# C64.net
KiCad netlist of a schematic drawn in EAGLE
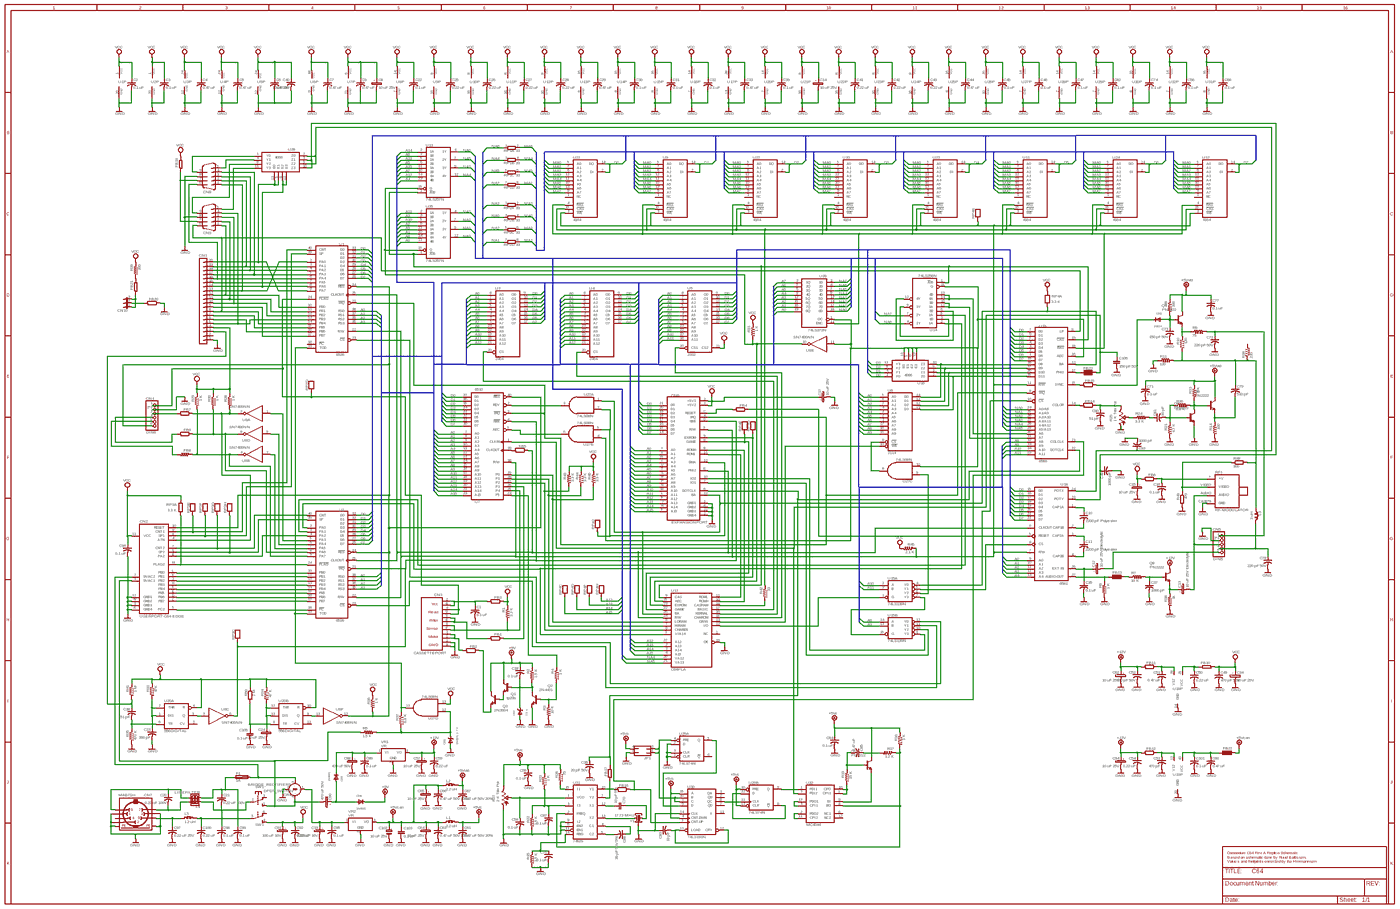
[diagram p0: schematic, sheet 1, overview]
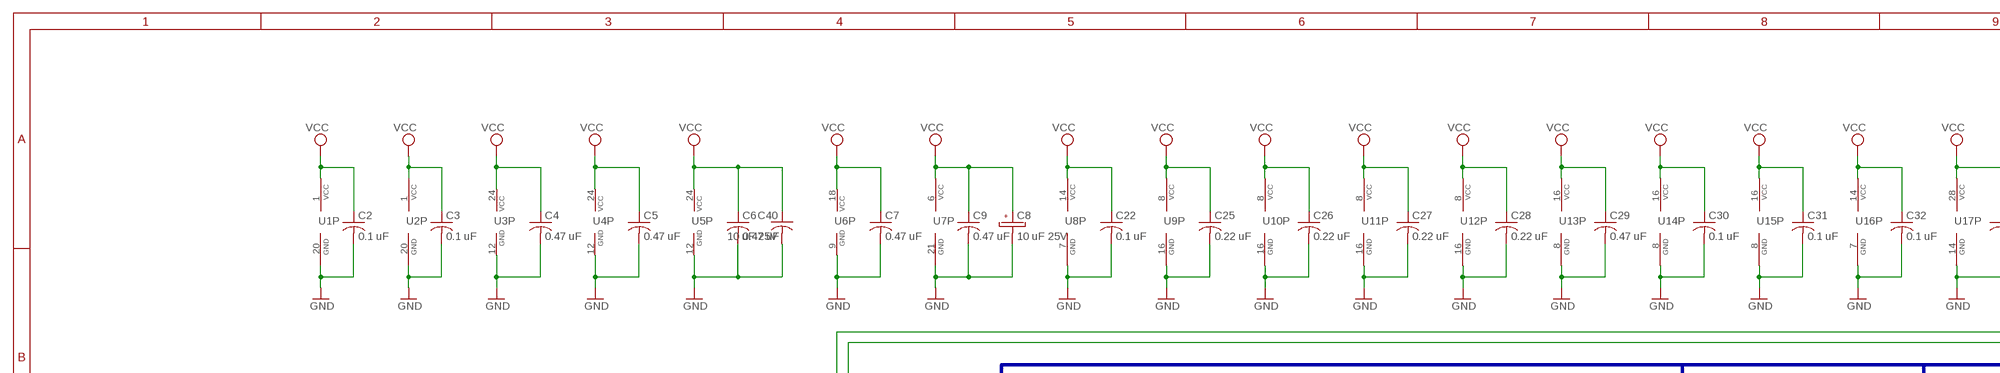
[diagram p1: schematic, sheet 1, part 1 of 4]
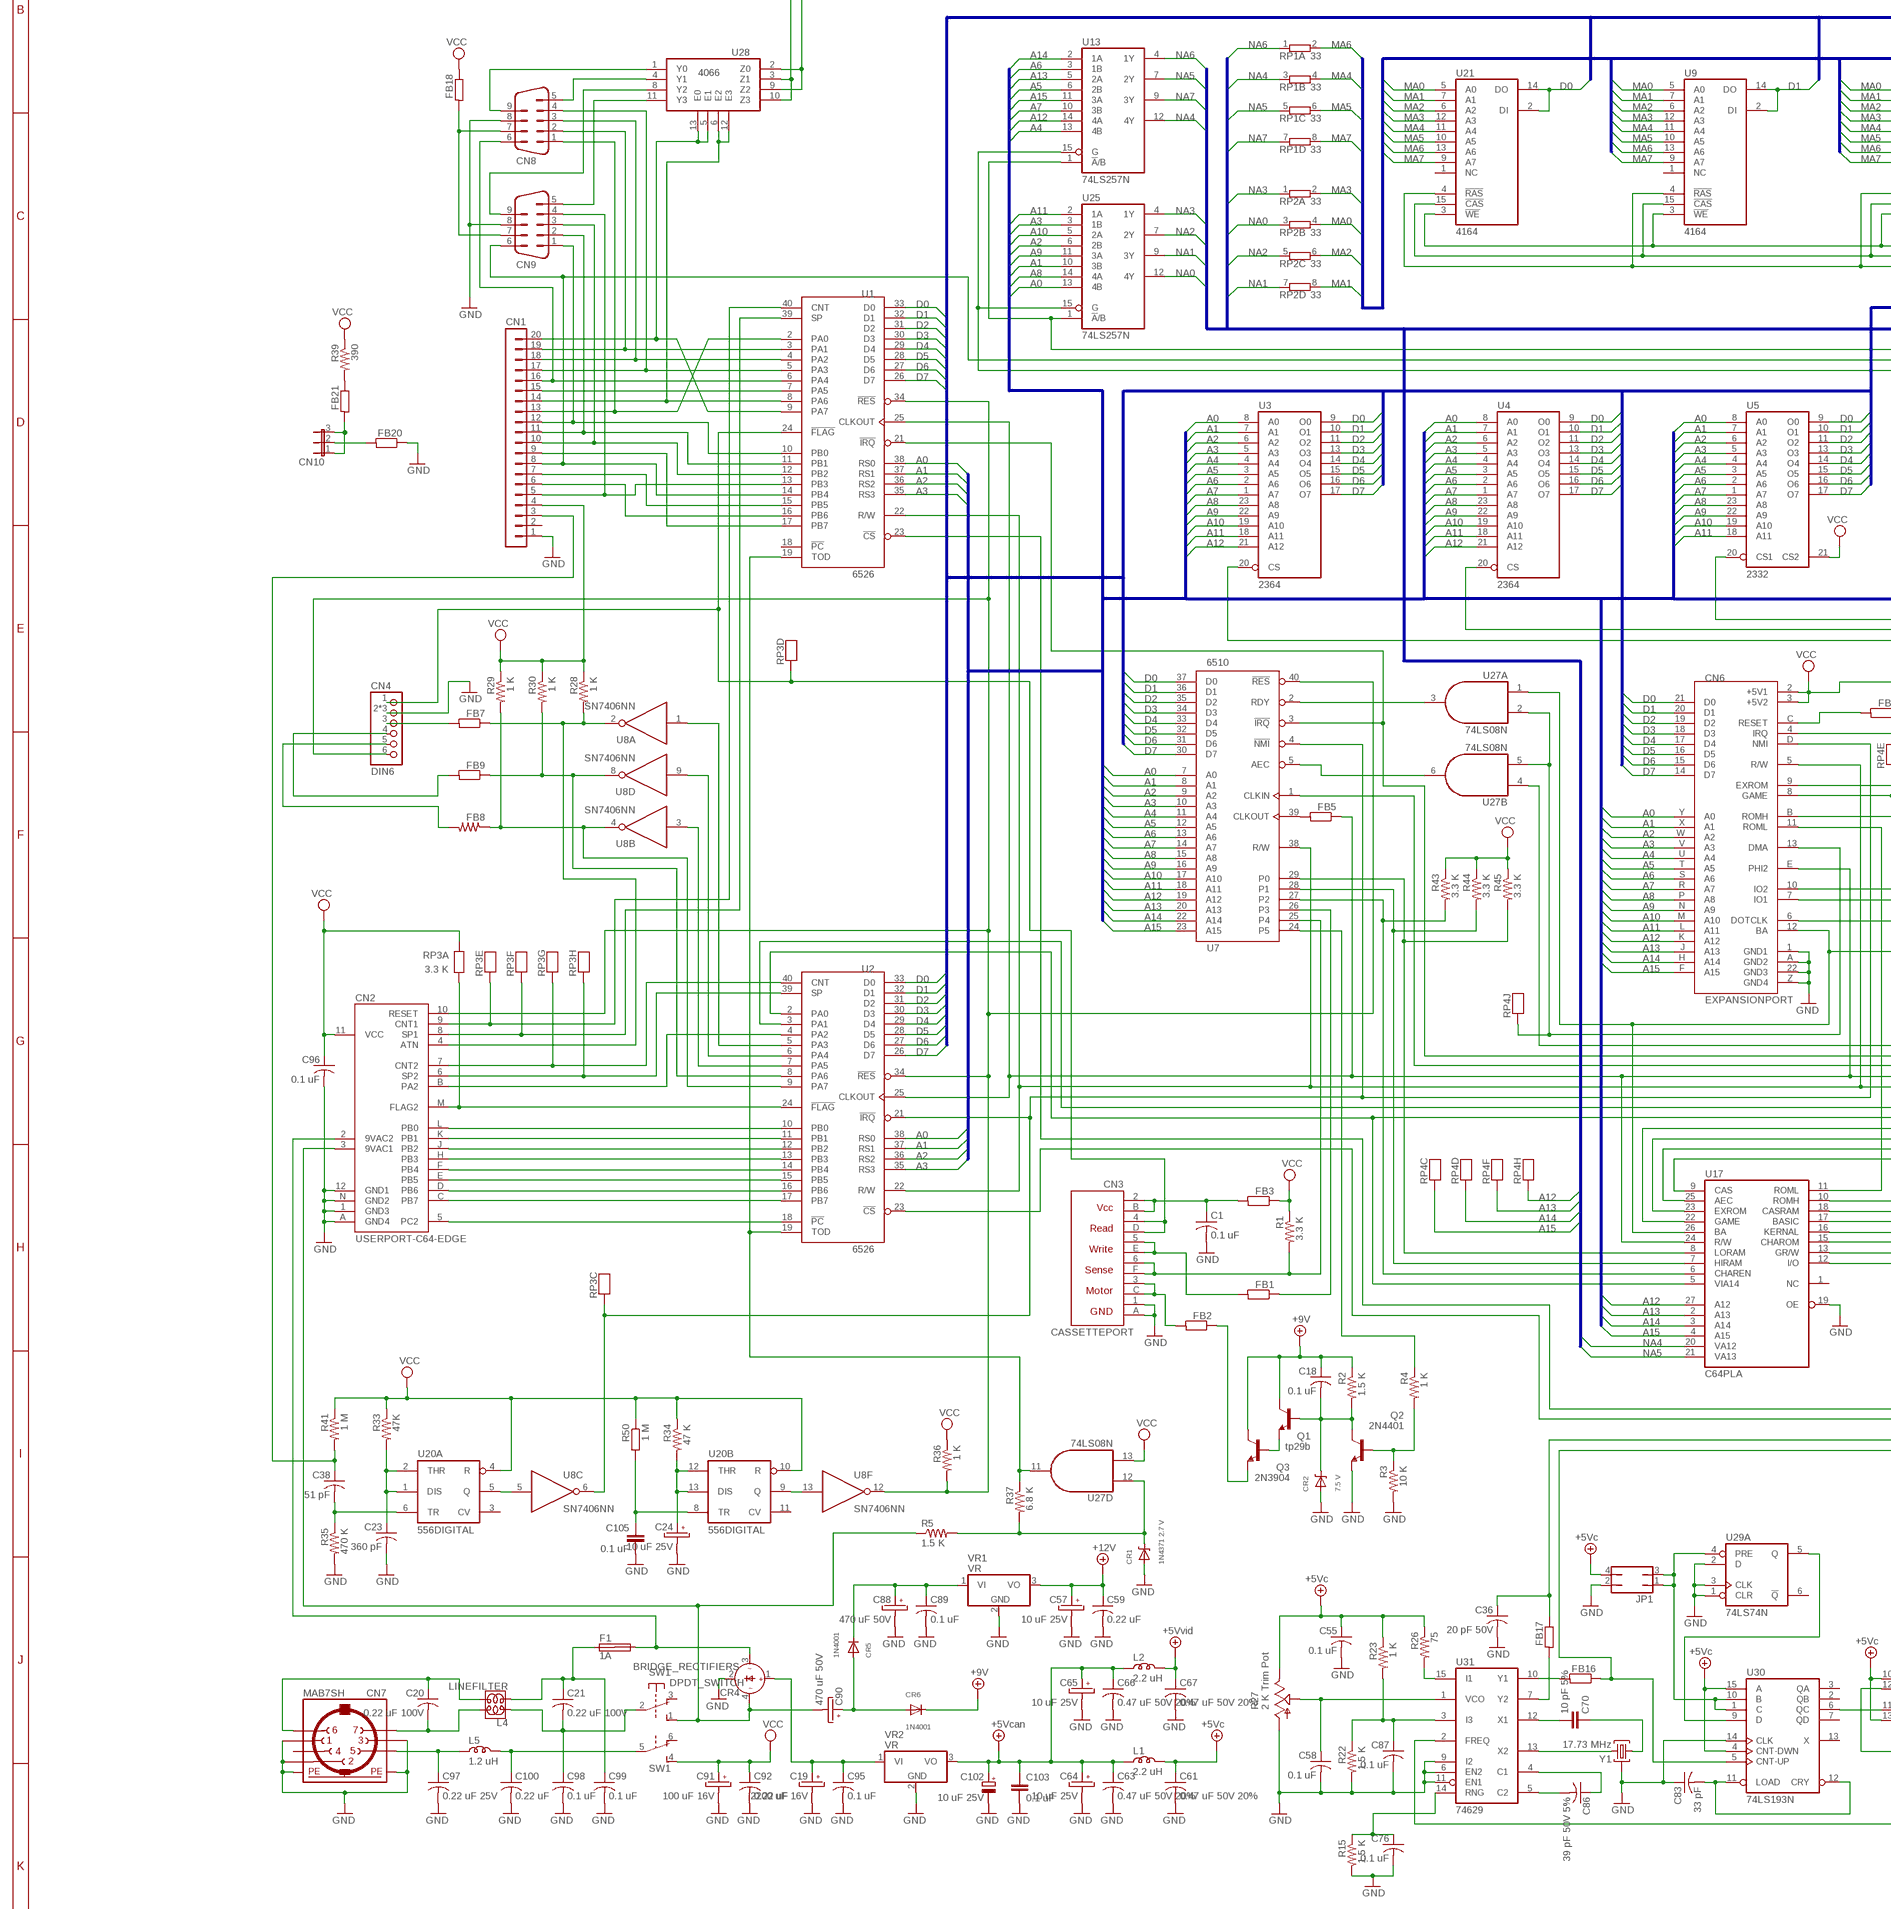
[diagram p2: schematic, sheet 1, part 2 of 4]
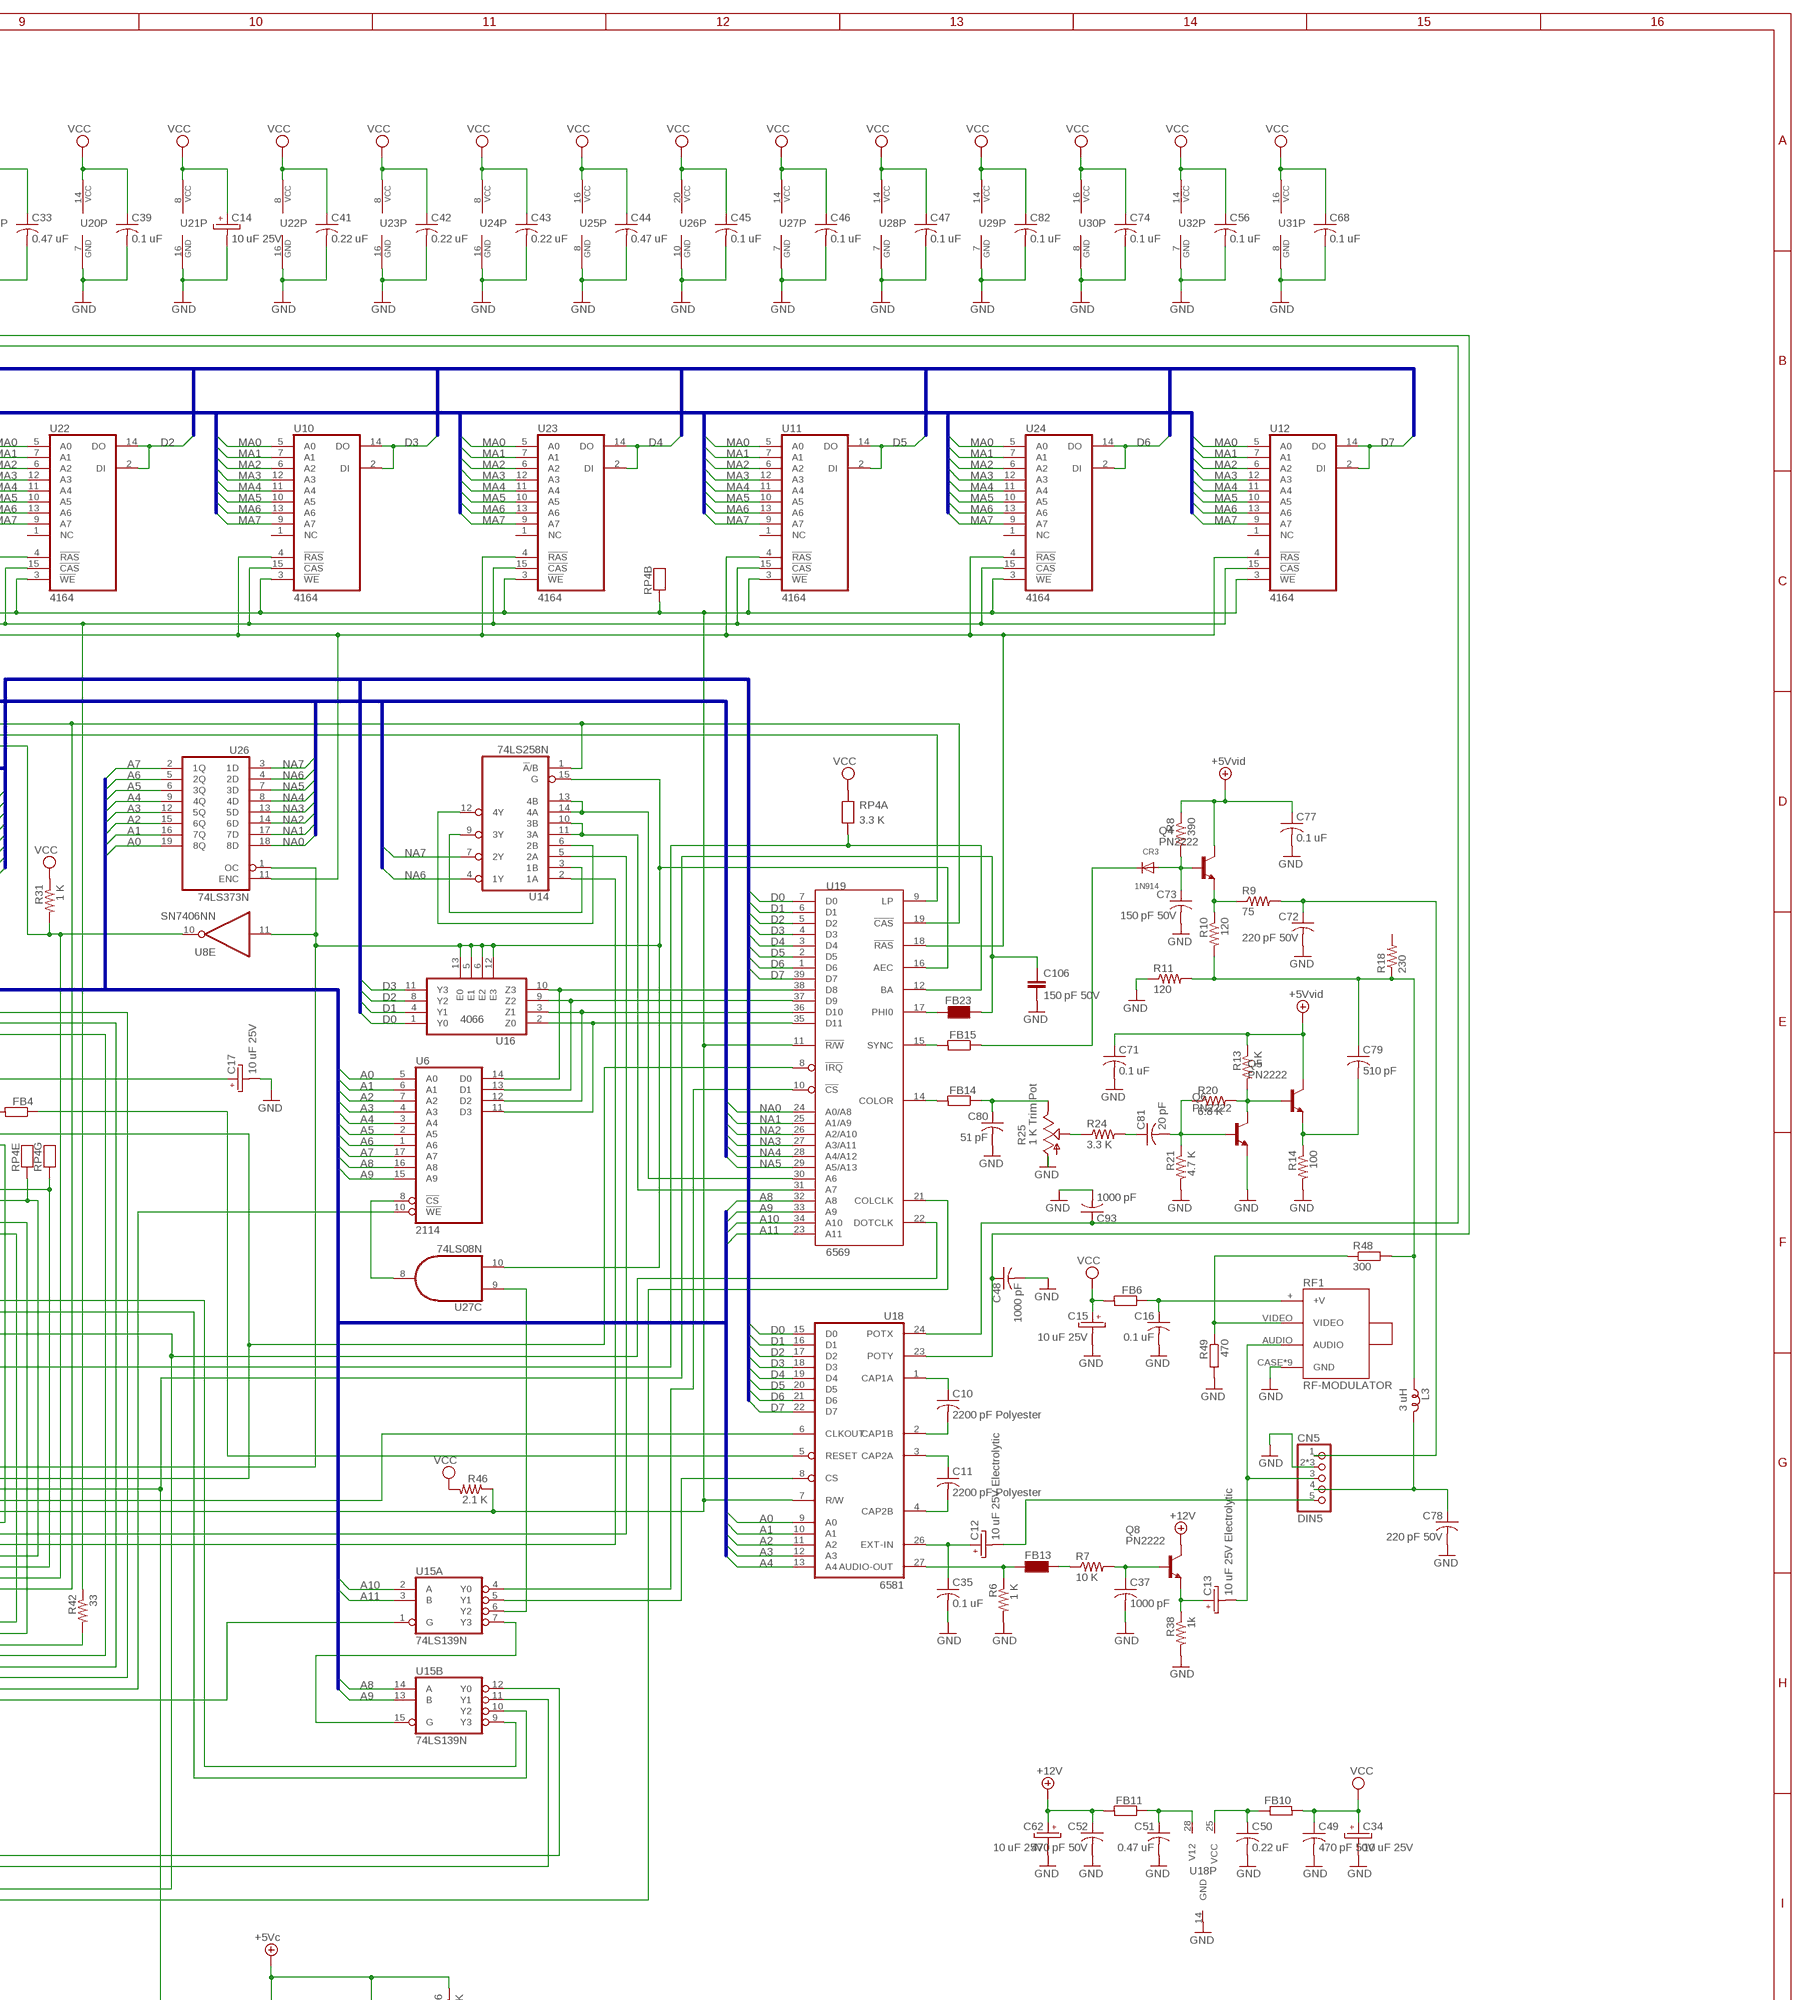
[diagram p3: schematic, sheet 1, part 3 of 4]
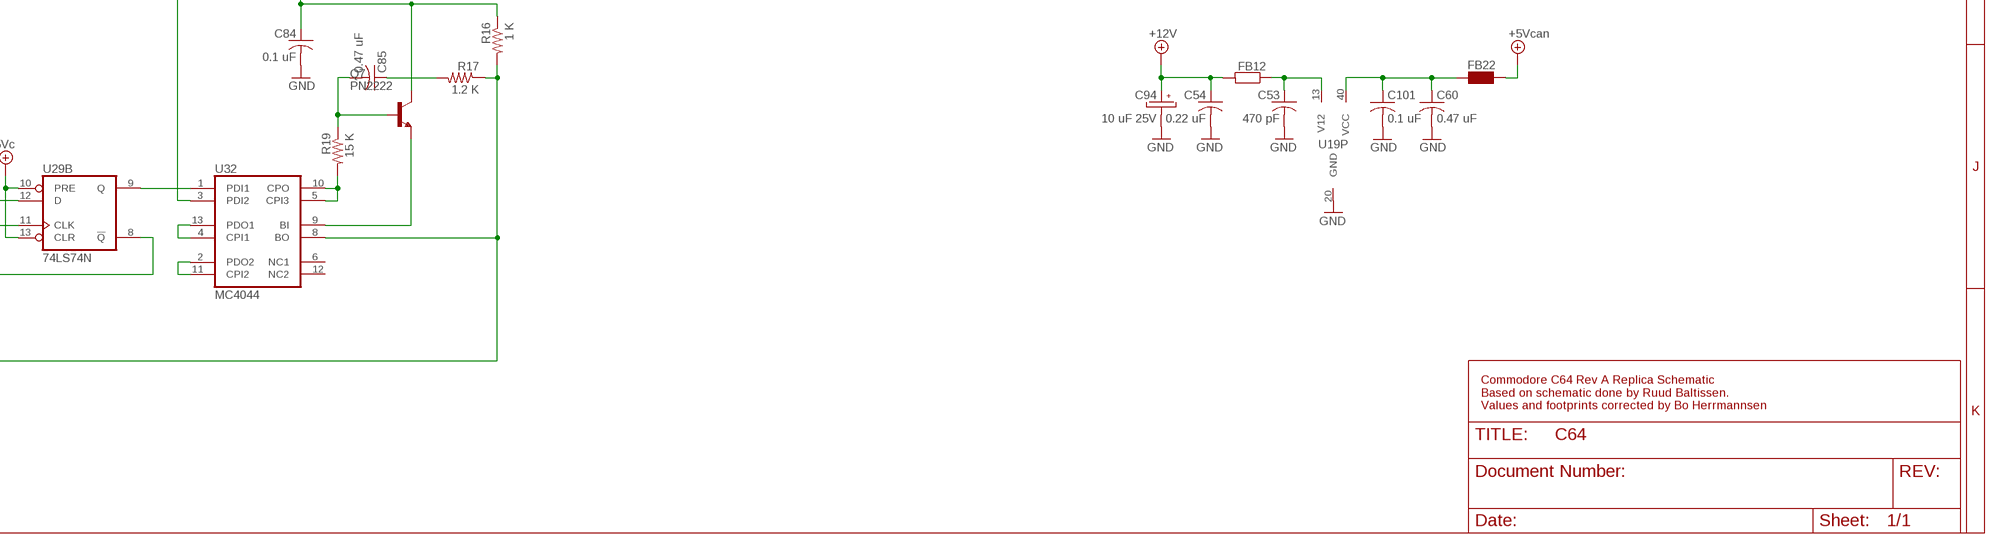
[diagram p4: schematic, sheet 1, part 4 of 4]

(export (version "E")
  (design (tool "Eeschema 10.0.6"))
  (components
    (comp (ref "C1")
      (value "0.1 uF")
      (footprint "eagle-import:0307_12")
      (libsource (lib "eagle-import") (part "C_0307/12C_0309/12"))
    )
    (comp (ref "C2")
      (value "0.1 uF")
      (footprint "eagle-import:0307_12")
      (libsource (lib "eagle-import") (part "C_0307/12C_0309/12"))
    )
    (comp (ref "C3")
      (value "0.1 uF")
      (footprint "eagle-import:0307_12")
      (libsource (lib "eagle-import") (part "C_0307/12C_0309/12"))
    )
    (comp (ref "C4")
      (value "0.47 uF")
      (footprint "eagle-import:0307_12")
      (libsource (lib "eagle-import") (part "C_0307/12C_0309/12"))
    )
    (comp (ref "C5")
      (value "0.47 uF")
      (footprint "eagle-import:0307_12")
      (libsource (lib "eagle-import") (part "C_0307/12C_0309/12"))
    )
    (comp (ref "C6")
      (value "0.47 uF")
      (footprint "eagle-import:0307_12")
      (libsource (lib "eagle-import") (part "C_0307/12C_0309/12"))
    )
    (comp (ref "C7")
      (value "0.47 uF")
      (footprint "eagle-import:0307_12")
      (libsource (lib "eagle-import") (part "C_0307/12C_0309/12"))
    )
    (comp (ref "C8")
      (value "10 uF 25V")
      (footprint "eagle-import:E2,5-6E")
      (libsource (lib "eagle-import") (part "C_E_2,5-6"))
    )
    (comp (ref "C9")
      (value "0.47 uF")
      (footprint "eagle-import:0307_12")
      (libsource (lib "eagle-import") (part "C_0307/12C_0309/12"))
    )
    (comp (ref "C10")
      (value "2200 pF Polyester")
      (footprint "eagle-import:0307_12")
      (libsource (lib "eagle-import") (part "C_0307/12C_0309/12"))
    )
    (comp (ref "C11")
      (value "2200 pF Polyester")
      (footprint "eagle-import:0307_12")
      (libsource (lib "eagle-import") (part "C_0307/12C_0309/12"))
    )
    (comp (ref "C12")
      (value "10 uF 25V Electrolytic")
      (footprint "eagle-import:E2,5-6E")
      (libsource (lib "eagle-import") (part "C_E_2,5-6"))
    )
    (comp (ref "C13")
      (value "10 uF 25V Electrolytic")
      (footprint "eagle-import:E2,5-6E")
      (libsource (lib "eagle-import") (part "C_E_2,5-6"))
    )
    (comp (ref "C14")
      (value "10 uF 25V")
      (footprint "eagle-import:CAPACITOR_ELECTROLYTIC_2.5_6")
      (libsource (lib "eagle-import") (part "CAPACITOR_ELECTROLYTIC_2.5_6"))
    )
    (comp (ref "C15")
      (value "10 uF 25V")
      (footprint "eagle-import:E2,5-6E")
      (libsource (lib "eagle-import") (part "C_E_2,5-6"))
    )
    (comp (ref "C16")
      (value "0.1 uF")
      (footprint "eagle-import:0307_12")
      (libsource (lib "eagle-import") (part "C_0307/12C_0309/12"))
    )
    (comp (ref "C17")
      (value "10 uF 25V")
      (footprint "eagle-import:E2,5-6E")
      (libsource (lib "eagle-import") (part "C_E_2,5-6"))
    )
    (comp (ref "C18")
      (value "0.1 uF")
      (footprint "eagle-import:0307_12")
      (libsource (lib "eagle-import") (part "C_0307/12C_0309/12"))
    )
    (comp (ref "C19")
      (value "2200 uF 16V")
      (footprint "eagle-import:E37-31.5-17.5-E")
      (libsource (lib "eagle-import") (part "E37-31.5-17.5-E"))
    )
    (comp (ref "C20")
      (value "0.22 uF 100V")
      (footprint "eagle-import:0203")
      (libsource (lib "eagle-import") (part "C_0203"))
    )
    (comp (ref "C21")
      (value "0.22 uF 100V")
      (footprint "eagle-import:0203")
      (libsource (lib "eagle-import") (part "C_0203"))
    )
    (comp (ref "C22")
      (value "0.1 uF")
      (footprint "eagle-import:12_3_7")
      (libsource (lib "eagle-import") (part "CAPACITOR_12_3_7C_0309/12"))
    )
    (comp (ref "C23")
      (value "360 pF")
      (footprint "eagle-import:12_3_7")
      (libsource (lib "eagle-import") (part "CAPACITOR_12_3_7C_0309/12"))
    )
    (comp (ref "C24")
      (value "10 uF 25V")
      (footprint "eagle-import:CAPACITOR_ELECTROLYTIC_2.5_6")
      (libsource (lib "eagle-import") (part "CAPACITOR_ELECTROLYTIC_2.5_6"))
    )
    (comp (ref "C25")
      (value "0.22 uF")
      (footprint "eagle-import:12_3_7")
      (libsource (lib "eagle-import") (part "CAPACITOR_12_3_7C_0309/12"))
    )
    (comp (ref "C26")
      (value "0.22 uF")
      (footprint "eagle-import:12_3_7")
      (libsource (lib "eagle-import") (part "CAPACITOR_12_3_7C_0309/12"))
    )
    (comp (ref "C27")
      (value "0.22 uF")
      (footprint "eagle-import:12_3_7")
      (libsource (lib "eagle-import") (part "CAPACITOR_12_3_7C_0309/12"))
    )
    (comp (ref "C28")
      (value "0.22 uF")
      (footprint "eagle-import:12_3_7")
      (libsource (lib "eagle-import") (part "CAPACITOR_12_3_7C_0309/12"))
    )
    (comp (ref "C29")
      (value "0.47 uF")
      (footprint "eagle-import:0307_12")
      (libsource (lib "eagle-import") (part "C_0307/12C_0309/12"))
    )
    (comp (ref "C30")
      (value "0.1 uF")
      (footprint "eagle-import:0307_12")
      (libsource (lib "eagle-import") (part "C_0307/12C_0309/12"))
    )
    (comp (ref "C31")
      (value "0.1 uF")
      (footprint "eagle-import:0307_12")
      (libsource (lib "eagle-import") (part "C_0307/12C_0309/12"))
    )
    (comp (ref "C32")
      (value "0.1 uF")
      (footprint "eagle-import:0307_12")
      (libsource (lib "eagle-import") (part "C_0307/12C_0309/12"))
    )
    (comp (ref "C33")
      (value "0.47 uF")
      (footprint "eagle-import:0307_12")
      (libsource (lib "eagle-import") (part "C_0307/12C_0309/12"))
    )
    (comp (ref "C34")
      (value "10 uF 25V")
      (footprint "eagle-import:E2,5-6E")
      (libsource (lib "eagle-import") (part "C_E_2,5-6"))
    )
    (comp (ref "C35")
      (value "0.1 uF")
      (footprint "eagle-import:0307_12")
      (libsource (lib "eagle-import") (part "C_0307/12C_0309/12"))
    )
    (comp (ref "C36")
      (value "20 pF 50V")
      (footprint "eagle-import:12_03_07")
      (libsource (lib "eagle-import") (part "CAPACITOR_12_03_07C_0309/12"))
    )
    (comp (ref "C37")
      (value "1000 pF")
      (footprint "eagle-import:0307_12")
      (libsource (lib "eagle-import") (part "C_0307/12C_0309/12"))
    )
    (comp (ref "C38")
      (value "51 pF")
      (footprint "eagle-import:12_3_7")
      (libsource (lib "eagle-import") (part "CAPACITOR_12_3_7C_0309/12"))
    )
    (comp (ref "C39")
      (value "0.1 uF")
      (footprint "eagle-import:12_3_7")
      (libsource (lib "eagle-import") (part "CAPACITOR_12_3_7C_0309/12"))
    )
    (comp (ref "C40")
      (value "10 uF 25V")
      (footprint "eagle-import:12_3_7")
      (libsource (lib "eagle-import") (part "CAPACITOR_12_3_7C_0309/12"))
    )
    (comp (ref "C41")
      (value "0.22 uF")
      (footprint "eagle-import:12_3_7")
      (libsource (lib "eagle-import") (part "CAPACITOR_12_3_7C_0309/12"))
    )
    (comp (ref "C42")
      (value "0.22 uF")
      (footprint "eagle-import:12_3_7")
      (libsource (lib "eagle-import") (part "CAPACITOR_12_3_7C_0309/12"))
    )
    (comp (ref "C43")
      (value "0.22 uF")
      (footprint "eagle-import:12_3_7")
      (libsource (lib "eagle-import") (part "CAPACITOR_12_3_7C_0309/12"))
    )
    (comp (ref "C44")
      (value "0.47 uF")
      (footprint "eagle-import:0307_12")
      (libsource (lib "eagle-import") (part "C_0307/12C_0309/12"))
    )
    (comp (ref "C45")
      (value "0.1 uF")
      (footprint "eagle-import:0307_12")
      (libsource (lib "eagle-import") (part "C_0307/12C_0309/12"))
    )
    (comp (ref "C46")
      (value "0.1 uF")
      (footprint "eagle-import:0307_12")
      (libsource (lib "eagle-import") (part "C_0307/12C_0309/12"))
    )
    (comp (ref "C47")
      (value "0.1 uF")
      (footprint "eagle-import:0307_12")
      (libsource (lib "eagle-import") (part "C_0307/12C_0309/12"))
    )
    (comp (ref "C48")
      (value "1000 pF")
      (footprint "eagle-import:0307_12")
      (libsource (lib "eagle-import") (part "C_0307/12C_0309/12"))
    )
    (comp (ref "C49")
      (value "470 pF 50V")
      (footprint "eagle-import:0307_12")
      (libsource (lib "eagle-import") (part "C_0307/12C_0309/12"))
    )
    (comp (ref "C50")
      (value "0.22 uF")
      (footprint "eagle-import:0307_12")
      (libsource (lib "eagle-import") (part "C_0307/12C_0309/12"))
    )
    (comp (ref "C51")
      (value "0.47 uF")
      (footprint "eagle-import:0307_12")
      (libsource (lib "eagle-import") (part "C_0307/12C_0309/12"))
    )
    (comp (ref "C52")
      (value "470 pF 50V")
      (footprint "eagle-import:0307_12")
      (libsource (lib "eagle-import") (part "C_0307/12C_0309/12"))
    )
    (comp (ref "C53")
      (value "470 pF")
      (footprint "eagle-import:0307_12")
      (libsource (lib "eagle-import") (part "C_0307/12C_0309/12"))
    )
    (comp (ref "C54")
      (value "0.22 uF")
      (footprint "eagle-import:0307_12")
      (libsource (lib "eagle-import") (part "C_0307/12C_0309/12"))
    )
    (comp (ref "C55")
      (value "0.1 uF")
      (footprint "eagle-import:12_03_07")
      (libsource (lib "eagle-import") (part "CAPACITOR_12_03_07C_0309/12"))
    )
    (comp (ref "C56")
      (value "0.1 uF")
      (footprint "eagle-import:12_03_07")
      (libsource (lib "eagle-import") (part "CAPACITOR_12_03_07C_0309/12"))
    )
    (comp (ref "C57")
      (value "10 uF 25V")
      (footprint "eagle-import:E2,5-6E")
      (libsource (lib "eagle-import") (part "C_E_2,5-6"))
    )
    (comp (ref "C58")
      (value "0.1 uF")
      (footprint "eagle-import:12_03_07")
      (libsource (lib "eagle-import") (part "CAPACITOR_12_03_07C_0309/12"))
    )
    (comp (ref "C59")
      (value "0.22 uF")
      (footprint "eagle-import:0307_12")
      (libsource (lib "eagle-import") (part "C_0307/12C_0309/12"))
    )
    (comp (ref "C60")
      (value "0.47 uF")
      (footprint "eagle-import:12_03_07")
      (libsource (lib "eagle-import") (part "CAPACITOR_12_03_07C_0309/12"))
    )
    (comp (ref "C61")
      (value "0.47 uF 50V 20%")
      (footprint "eagle-import:15_4_10")
      (libsource (lib "eagle-import") (part "CAPACITOR_15_04_10"))
    )
    (comp (ref "C62")
      (value "10 uF 25V")
      (footprint "eagle-import:E2,5-6E")
      (libsource (lib "eagle-import") (part "C_E_2,5-6"))
    )
    (comp (ref "C63")
      (value "0.47 uF 50V 20%")
      (footprint "eagle-import:15_4_10")
      (libsource (lib "eagle-import") (part "CAPACITOR_15_04_10"))
    )
    (comp (ref "C64")
      (value "10 uF 25V")
      (footprint "eagle-import:CAPACITOR_ELECTROLYTIC_2.5_6")
      (libsource (lib "eagle-import") (part "CAPACITOR_ELECTROLYTIC_2.5_6"))
    )
    (comp (ref "C65")
      (value "10 uF 25V")
      (footprint "eagle-import:CAPACITOR_ELECTROLYTIC_2.5_6")
      (libsource (lib "eagle-import") (part "CAPACITOR_ELECTROLYTIC_2.5_6"))
    )
    (comp (ref "C66")
      (value "0.47 uF 50V 20%")
      (footprint "eagle-import:15_4_10")
      (libsource (lib "eagle-import") (part "CAPACITOR_15_04_10"))
    )
    (comp (ref "C67")
      (value "0.47 uF 50V 20%")
      (footprint "eagle-import:15_4_10")
      (libsource (lib "eagle-import") (part "CAPACITOR_15_04_10"))
    )
    (comp (ref "C68")
      (value "0.1 uF")
      (footprint "eagle-import:12_03_07")
      (libsource (lib "eagle-import") (part "CAPACITOR_12_03_07C_0309/12"))
    )
    (comp (ref "C70")
      (value "10 pF 5%")
      (footprint "eagle-import:C075-032X103")
      (libsource (lib "eagle-import") (part "C-EU075-032X103"))
    )
    (comp (ref "C71")
      (value "0.1 uF")
      (footprint "eagle-import:12_03_07")
      (libsource (lib "eagle-import") (part "CAPACITOR_12_03_07C_0309/12"))
    )
    (comp (ref "C72")
      (value "220 pF 50V")
      (footprint "eagle-import:12_03_07")
      (libsource (lib "eagle-import") (part "CAPACITOR_12_03_07C_0309/12"))
    )
    (comp (ref "C73")
      (value "150 pF 50V")
      (footprint "eagle-import:12_03_07")
      (libsource (lib "eagle-import") (part "CAPACITOR_12_03_07C_0309/12"))
    )
    (comp (ref "C74")
      (value "0.1 uF")
      (footprint "eagle-import:12_03_07")
      (libsource (lib "eagle-import") (part "CAPACITOR_12_03_07C_0309/12"))
    )
    (comp (ref "C76")
      (value "0.1 uF")
      (footprint "eagle-import:12_03_07")
      (libsource (lib "eagle-import") (part "CAPACITOR_12_03_07C_0309/12"))
    )
    (comp (ref "C77")
      (value "0.1 uF")
      (footprint "eagle-import:12_03_07")
      (libsource (lib "eagle-import") (part "CAPACITOR_12_03_07C_0309/12"))
    )
    (comp (ref "C78")
      (value "220 pF 50V")
      (footprint "eagle-import:12_03_07")
      (libsource (lib "eagle-import") (part "CAPACITOR_12_03_07C_0309/12"))
    )
    (comp (ref "C79")
      (value "510 pF")
      (footprint "eagle-import:12_03_07")
      (libsource (lib "eagle-import") (part "CAPACITOR_12_03_07C_0309/12"))
    )
    (comp (ref "C80")
      (value "51 pF")
      (footprint "eagle-import:12_03_07")
      (libsource (lib "eagle-import") (part "CAPACITOR_12_03_07C_0309/12"))
    )
    (comp (ref "C81")
      (value "20 pF")
      (footprint "eagle-import:12_03_07")
      (libsource (lib "eagle-import") (part "CAPACITOR_12_03_07C_0309/12"))
    )
    (comp (ref "C82")
      (value "0.1 uF")
      (footprint "eagle-import:12_03_07")
      (libsource (lib "eagle-import") (part "CAPACITOR_12_03_07C_0309/12"))
    )
    (comp (ref "C83")
      (value "33 pF")
      (footprint "eagle-import:12_03_07")
      (libsource (lib "eagle-import") (part "CAPACITOR_12_03_07C_0309/12"))
    )
    (comp (ref "C84")
      (value "0.1 uF")
      (footprint "eagle-import:12_03_07")
      (libsource (lib "eagle-import") (part "CAPACITOR_12_03_07C_0309/12"))
    )
    (comp (ref "C85")
      (value "0.47 uF")
      (footprint "eagle-import:12_03_07")
      (libsource (lib "eagle-import") (part "CAPACITOR_12_03_07C_0309/12"))
    )
    (comp (ref "C86")
      (value "39 pF 50V 5%")
      (footprint "eagle-import:12_03_07")
      (libsource (lib "eagle-import") (part "CAPACITOR_12_03_07C_0309/12"))
    )
    (comp (ref "C87")
      (value "0.1 uF")
      (footprint "eagle-import:12_03_07")
      (libsource (lib "eagle-import") (part "CAPACITOR_12_03_07C_0309/12"))
    )
    (comp (ref "C88")
      (value "470 uF 50V")
      (footprint "eagle-import:E37-31.5-17.5-E")
      (libsource (lib "eagle-import") (part "E37-31.5-17.5-E"))
    )
    (comp (ref "C89")
      (value "0.1 uF")
      (footprint "eagle-import:0307_12")
      (libsource (lib "eagle-import") (part "C_0307/12C_0309/12"))
    )
    (comp (ref "C90")
      (value "470 uF 50V")
      (footprint "eagle-import:E37-31.5-17.5-E")
      (libsource (lib "eagle-import") (part "E37-31.5-17.5-E"))
    )
    (comp (ref "C91")
      (value "100 uF 16V")
      (footprint "eagle-import:C_E_5-9")
      (libsource (lib "eagle-import") (part "C_E_5-9"))
    )
    (comp (ref "C92")
      (value "0.22 uF")
      (footprint "eagle-import:0307_12")
      (libsource (lib "eagle-import") (part "C_0307/12C_0309/12"))
    )
    (comp (ref "C93")
      (value "1000 pF")
      (footprint "eagle-import:0307_12")
      (libsource (lib "eagle-import") (part "C_0307/12C_0309/12"))
    )
    (comp (ref "C94")
      (value "10 uF 25V")
      (footprint "eagle-import:E2,5-6E")
      (libsource (lib "eagle-import") (part "C_E_2,5-6"))
    )
    (comp (ref "C95")
      (value "0.1 uF")
      (footprint "eagle-import:0307_12")
      (libsource (lib "eagle-import") (part "C_0307/12C_0309/12"))
    )
    (comp (ref "C96")
      (value "0.1 uF")
      (footprint "eagle-import:0307_12")
      (libsource (lib "eagle-import") (part "C_0307/12C_0309/12"))
    )
    (comp (ref "C97")
      (value "0.22 uF 25V")
      (footprint "eagle-import:0203")
      (libsource (lib "eagle-import") (part "C_0203"))
    )
    (comp (ref "C98")
      (value "0.1 uF")
      (footprint "eagle-import:0203")
      (libsource (lib "eagle-import") (part "C_0203"))
    )
    (comp (ref "C99")
      (value "0.1 uF")
      (footprint "eagle-import:0203")
      (libsource (lib "eagle-import") (part "C_0203"))
    )
    (comp (ref "C100")
      (value "0.22 uF")
      (footprint "eagle-import:0203")
      (libsource (lib "eagle-import") (part "C_0203"))
    )
    (comp (ref "C101")
      (value "0.1 uF")
      (footprint "eagle-import:6_03_8.5")
      (libsource (lib "eagle-import") (part "CAPACITOR_6_03_8.5"))
    )
    (comp (ref "C102")
      (value "10 uF 25V")
      (footprint "eagle-import:E3,5-10")
      (libsource (lib "eagle-import") (part "CPOL-EUE3.5-10"))
    )
    (comp (ref "C103")
      (value "0.1 uF")
      (footprint "eagle-import:C075-032X103")
      (libsource (lib "eagle-import") (part "C-EU075-032X103"))
    )
    (comp (ref "C105")
      (value "0.1 uF")
      (footprint "eagle-import:C075-032X103")
      (libsource (lib "eagle-import") (part "C-EU075-032X103"))
    )
    (comp (ref "C106")
      (value "150 pF 50V")
      (footprint "eagle-import:C075-032X103")
      (libsource (lib "eagle-import") (part "C-EU075-032X103"))
    )
    (comp (ref "CN1")
      (value "MA20-1")
      (footprint "eagle-import:MA20-1")
      (libsource (lib "eagle-import") (part "MA20-1"))
    )
    (comp (ref "CN2")
      (value "USERPORT-C64-EDGE")
      (footprint "eagle-import:UPS24EDGE")
      (libsource (lib "eagle-import") (part "USERPORT-C64-EDGE"))
    )
    (comp (ref "CN3")
      (value "CASSETTEPORT")
      (footprint "eagle-import:CASSETTEPORT")
      (libsource (lib "eagle-import") (part "CASSETTEPORT"))
    )
    (comp (ref "CN4")
      (value "DIN6")
      (footprint "eagle-import:DIN6")
      (libsource (lib "eagle-import") (part "DIN6"))
    )
    (comp (ref "CN5")
      (value "DIN5")
      (footprint "eagle-import:DIN5")
      (libsource (lib "eagle-import") (part "DIN5"))
    )
    (comp (ref "CN6")
      (value "EXPANSIONPORT")
      (footprint "eagle-import:EXPANSIONPORT")
      (libsource (lib "eagle-import") (part "EXPANSIONPORT-C64"))
    )
    (comp (ref "CN7")
      (value "MAB7SH")
      (footprint "eagle-import:MAB7SH")
      (libsource (lib "eagle-import") (part "MAB7SH"))
    )
    (comp (ref "CN8")
      (value "CONTROL_PORT")
      (footprint "eagle-import:CONTROL_PORT")
      (libsource (lib "eagle-import") (part "CONTROL_PORT"))
    )
    (comp (ref "CN9")
      (value "CONTROL_PORT")
      (footprint "eagle-import:CONTROL_PORT")
      (libsource (lib "eagle-import") (part "CONTROL_PORT"))
    )
    (comp (ref "CN10")
      (value "JP2E")
      (footprint "eagle-import:JP2")
      (libsource (lib "eagle-import") (part "JP2E"))
    )
    (comp (ref "CR1")
      (value "1N4371 2.7 V")
      (footprint "eagle-import:D_0307_12")
      (libsource (lib "eagle-import") (part "ZD_0307/12"))
    )
    (comp (ref "CR2")
      (value "7.5 V")
      (footprint "eagle-import:D_0307_12")
      (libsource (lib "eagle-import") (part "ZD_0307/12"))
    )
    (comp (ref "CR3")
      (value "1N914")
      (footprint "eagle-import:D_0307_12")
      (libsource (lib "eagle-import") (part "D_0307/12"))
    )
    (comp (ref "CR4")
      (value "BRIDGE_RECTIFIERS")
      (footprint "eagle-import:DIL4")
      (libsource (lib "eagle-import") (part "BRIDGE_RECTIFIERS"))
    )
    (comp (ref "CR5")
      (value "1N4001")
      (footprint "eagle-import:D_0307_12")
      (libsource (lib "eagle-import") (part "D_0307/12"))
    )
    (comp (ref "CR6")
      (value "1N4001")
      (footprint "eagle-import:D_0307_12")
      (libsource (lib "eagle-import") (part "D_0307/12"))
    )
    (comp (ref "F1")
      (value "1A")
      (footprint "eagle-import:SH32")
      (fields (field (name "MPN") "10207101009"))
      (libsource (lib "eagle-import") (part "SH32"))
    )
    (comp (ref "FB1")
      (value "FB_0307/12R_0307/12")
      (footprint "eagle-import:12_03_07")
      (libsource (lib "eagle-import") (part "FB_0307/12R_0307/12"))
    )
    (comp (ref "FB2")
      (value "FB_0307/12R_0307/12")
      (footprint "eagle-import:12_03_07")
      (libsource (lib "eagle-import") (part "FB_0307/12R_0307/12"))
    )
    (comp (ref "FB3")
      (value "FB_0307/12R_0307/12")
      (footprint "eagle-import:12_03_07")
      (libsource (lib "eagle-import") (part "FB_0307/12R_0307/12"))
    )
    (comp (ref "FB4")
      (value "FB_0307/12R_0307/12")
      (footprint "eagle-import:12_03_07")
      (libsource (lib "eagle-import") (part "FB_0307/12R_0307/12"))
    )
    (comp (ref "FB5")
      (value "FB_0307/12R_0307/12")
      (footprint "eagle-import:12_03_07")
      (libsource (lib "eagle-import") (part "FB_0307/12R_0307/12"))
    )
    (comp (ref "FB6")
      (value "FB_0307/12R_0307/12")
      (footprint "eagle-import:12_03_07")
      (libsource (lib "eagle-import") (part "FB_0307/12R_0307/12"))
    )
    (comp (ref "FB7")
      (value "FERRITE_BEAD_12_3_7R_0307/12")
      (footprint "eagle-import:12_3_7")
      (libsource (lib "eagle-import") (part "FERRITE_BEAD_12_3_7R_0307/12"))
    )
    (comp (ref "FB8")
      (value "RESISTOR_12_3_7R_0307/12")
      (footprint "eagle-import:12_3_7")
      (libsource (lib "eagle-import") (part "RESISTOR_12_3_7R_0307/12"))
    )
    (comp (ref "FB9")
      (value "FERRITE_BEAD_12_3_7R_0307/12")
      (footprint "eagle-import:12_3_7")
      (libsource (lib "eagle-import") (part "FERRITE_BEAD_12_3_7R_0307/12"))
    )
    (comp (ref "FB10")
      (value "FB_0307/12R_0307/12")
      (footprint "eagle-import:12_03_07")
      (libsource (lib "eagle-import") (part "FB_0307/12R_0307/12"))
    )
    (comp (ref "FB11")
      (value "FB_0307/12R_0307/12")
      (footprint "eagle-import:12_03_07")
      (libsource (lib "eagle-import") (part "FB_0307/12R_0307/12"))
    )
    (comp (ref "FB12")
      (value "FB_0307/12R_0307/12")
      (footprint "eagle-import:12_03_07")
      (libsource (lib "eagle-import") (part "FB_0307/12R_0307/12"))
    )
    (comp (ref "FB13")
      (value "FERRIT")
      (footprint "eagle-import:R5")
      (libsource (lib "eagle-import") (part "FERRIT"))
    )
    (comp (ref "FB14")
      (value "FB_0307/12R_0307/12")
      (footprint "eagle-import:12_03_07")
      (libsource (lib "eagle-import") (part "FB_0307/12R_0307/12"))
    )
    (comp (ref "FB15")
      (value "FB_0307/12R_0307/12")
      (footprint "eagle-import:12_03_07")
      (libsource (lib "eagle-import") (part "FB_0307/12R_0307/12"))
    )
    (comp (ref "FB16")
      (value "FB_0307/12R_0307/12")
      (footprint "eagle-import:12_03_07")
      (libsource (lib "eagle-import") (part "FB_0307/12R_0307/12"))
    )
    (comp (ref "FB17")
      (value "FB_0307/12R_0307/12")
      (footprint "eagle-import:12_03_07")
      (libsource (lib "eagle-import") (part "FB_0307/12R_0307/12"))
    )
    (comp (ref "FB18")
      (value "FB_0307/12R_0307/12")
      (footprint "eagle-import:12_03_07")
      (libsource (lib "eagle-import") (part "FB_0307/12R_0307/12"))
    )
    (comp (ref "FB20")
      (value "FB_0307/12R_0307/12")
      (footprint "eagle-import:12_03_07")
      (libsource (lib "eagle-import") (part "FB_0307/12R_0307/12"))
    )
    (comp (ref "FB21")
      (value "FB_0307/12R_0307/12")
      (footprint "eagle-import:12_03_07")
      (libsource (lib "eagle-import") (part "FB_0307/12R_0307/12"))
    )
    (comp (ref "FB22")
      (value "FERRIT")
      (footprint "eagle-import:R5")
      (libsource (lib "eagle-import") (part "FERRIT"))
    )
    (comp (ref "FB23")
      (value "FERRIT")
      (footprint "eagle-import:R5")
      (libsource (lib "eagle-import") (part "FERRIT"))
    )
    (comp (ref "JP1")
      (value "JP2Q")
      (footprint "eagle-import:JP2Q")
      (libsource (lib "eagle-import") (part "JP2Q"))
    )
    (comp (ref "L1")
      (value "2.2 uH")
      (footprint "eagle-import:12_3_7")
      (libsource (lib "eagle-import") (part "INDUCTOR_12_3_7"))
    )
    (comp (ref "L2")
      (value "2.2 uH")
      (footprint "eagle-import:12_3_7")
      (libsource (lib "eagle-import") (part "INDUCTOR_12_3_7"))
    )
    (comp (ref "L3")
      (value "3 uH")
      (footprint "eagle-import:12_3_7")
      (libsource (lib "eagle-import") (part "INDUCTOR_12_3_7"))
    )
    (comp (ref "L4")
      (value "LINEFILTER")
      (footprint "eagle-import:LINEFILTER")
      (libsource (lib "eagle-import") (part "LINEFILTER"))
    )
    (comp (ref "L5")
      (value "1.2 uH")
      (footprint "eagle-import:R5")
      (libsource (lib "eagle-import") (part "COIL"))
    )
    (comp (ref "Q1")
      (value "tp29b")
      (footprint "eagle-import:TO220V")
      (libsource (lib "eagle-import") (part "TIP29B"))
    )
    (comp (ref "Q2")
      (value "2N4401")
      (footprint "eagle-import:TO92")
      (libsource (lib "eagle-import") (part "2N4401"))
    )
    (comp (ref "Q3")
      (value "2N3904")
      (footprint "eagle-import:TO92")
      (libsource (lib "eagle-import") (part "2N3904"))
    )
    (comp (ref "Q4")
      (value "PN2222")
      (footprint "eagle-import:TO92")
      (libsource (lib "eagle-import") (part "PN2222"))
    )
    (comp (ref "Q5")
      (value "PN2222")
      (footprint "eagle-import:TO92")
      (libsource (lib "eagle-import") (part "PN2222"))
    )
    (comp (ref "Q6")
      (value "PN2222")
      (footprint "eagle-import:TO92")
      (libsource (lib "eagle-import") (part "PN2222"))
    )
    (comp (ref "Q7")
      (value "PN2222")
      (footprint "eagle-import:TO92")
      (libsource (lib "eagle-import") (part "PN2222"))
    )
    (comp (ref "Q8")
      (value "PN2222")
      (footprint "eagle-import:TO92")
      (libsource (lib "eagle-import") (part "PN2222"))
    )
    (comp (ref "R1")
      (value "3.3 K")
      (footprint "eagle-import:0307_12")
      (libsource (lib "eagle-import") (part "R_0307/12R_0307/12"))
    )
    (comp (ref "R2")
      (value "1.5 K")
      (footprint "eagle-import:0307_12")
      (libsource (lib "eagle-import") (part "R_0307/12R_0307/12"))
    )
    (comp (ref "R3")
      (value "10 K")
      (footprint "eagle-import:0307_12")
      (libsource (lib "eagle-import") (part "R_0307/12R_0307/12"))
    )
    (comp (ref "R4")
      (value "1 K")
      (footprint "eagle-import:0307_12")
      (libsource (lib "eagle-import") (part "R_0307/12R_0307/12"))
    )
    (comp (ref "R5")
      (value "1.5 K")
      (footprint "eagle-import:0307_12")
      (libsource (lib "eagle-import") (part "R_0307/12R_0307/12"))
    )
    (comp (ref "R6")
      (value "1 K")
      (footprint "eagle-import:0307_12")
      (libsource (lib "eagle-import") (part "R_0307/12R_0307/12"))
    )
    (comp (ref "R7")
      (value "10 K")
      (footprint "eagle-import:0307_12")
      (libsource (lib "eagle-import") (part "R_0307/12R_0307/12"))
    )
    (comp (ref "R8")
      (value "390")
      (footprint "eagle-import:12_03_07")
      (libsource (lib "eagle-import") (part "RESISTOR_12_03_07R_0307/12"))
    )
    (comp (ref "R9")
      (value "75")
      (footprint "eagle-import:12_03_07")
      (libsource (lib "eagle-import") (part "RESISTOR_12_03_07R_0307/12"))
    )
    (comp (ref "R10")
      (value "120")
      (footprint "eagle-import:12_03_07")
      (libsource (lib "eagle-import") (part "RESISTOR_12_03_07R_0307/12"))
    )
    (comp (ref "R11")
      (value "120")
      (footprint "eagle-import:12_03_07")
      (libsource (lib "eagle-import") (part "RESISTOR_12_03_07R_0307/12"))
    )
    (comp (ref "R13")
      (value "1 K")
      (footprint "eagle-import:12_03_07")
      (libsource (lib "eagle-import") (part "RESISTOR_12_03_07R_0307/12"))
    )
    (comp (ref "R14")
      (value "100")
      (footprint "eagle-import:12_03_07")
      (libsource (lib "eagle-import") (part "RESISTOR_12_03_07R_0307/12"))
    )
    (comp (ref "R15")
      (value "1.5 K")
      (footprint "eagle-import:12_03_07")
      (libsource (lib "eagle-import") (part "RESISTOR_12_03_07R_0307/12"))
    )
    (comp (ref "R16")
      (value "1 K")
      (footprint "eagle-import:12_03_07")
      (libsource (lib "eagle-import") (part "RESISTOR_12_03_07R_0307/12"))
    )
    (comp (ref "R17")
      (value "1.2 K")
      (footprint "eagle-import:12_03_07")
      (libsource (lib "eagle-import") (part "RESISTOR_12_03_07R_0307/12"))
    )
    (comp (ref "R18")
      (value "230")
      (footprint "eagle-import:12_03_07")
      (libsource (lib "eagle-import") (part "RESISTOR_12_03_07R_0307/12"))
    )
    (comp (ref "R19")
      (value "15 K")
      (footprint "eagle-import:12_03_07")
      (libsource (lib "eagle-import") (part "RESISTOR_12_03_07R_0307/12"))
    )
    (comp (ref "R20")
      (value "6.8 K")
      (footprint "eagle-import:12_03_07")
      (libsource (lib "eagle-import") (part "RESISTOR_12_03_07R_0307/12"))
    )
    (comp (ref "R21")
      (value "4.7 K")
      (footprint "eagle-import:12_03_07")
      (libsource (lib "eagle-import") (part "RESISTOR_12_03_07R_0307/12"))
    )
    (comp (ref "R22")
      (value "1.5 K")
      (footprint "eagle-import:12_03_07")
      (libsource (lib "eagle-import") (part "RESISTOR_12_03_07R_0307/12"))
    )
    (comp (ref "R23")
      (value "1 K")
      (footprint "eagle-import:12_03_07")
      (libsource (lib "eagle-import") (part "RESISTOR_12_03_07R_0307/12"))
    )
    (comp (ref "R24")
      (value "3.3 K")
      (footprint "eagle-import:12_03_07")
      (libsource (lib "eagle-import") (part "RESISTOR_12_03_07R_0307/12"))
    )
    (comp (ref "R25")
      (value "1 K Trim Pot")
      (footprint "eagle-import:POT_METER")
      (libsource (lib "eagle-import") (part "POT_METER"))
    )
    (comp (ref "R26")
      (value "75")
      (footprint "eagle-import:12_03_07")
      (libsource (lib "eagle-import") (part "RESISTOR_12_03_07R_0307/12"))
    )
    (comp (ref "R27")
      (value "2 K Trim Pot")
      (footprint "eagle-import:POT_METER")
      (libsource (lib "eagle-import") (part "POT_METER"))
    )
    (comp (ref "R28")
      (value "1 K")
      (footprint "eagle-import:12_3_7")
      (libsource (lib "eagle-import") (part "RESISTOR_12_3_7R_0307/12"))
    )
    (comp (ref "R29")
      (value "1 K")
      (footprint "eagle-import:12_3_7")
      (libsource (lib "eagle-import") (part "RESISTOR_12_3_7R_0307/12"))
    )
    (comp (ref "R30")
      (value "1 K")
      (footprint "eagle-import:12_3_7")
      (libsource (lib "eagle-import") (part "RESISTOR_12_3_7R_0307/12"))
    )
    (comp (ref "R31")
      (value "1 K")
      (footprint "eagle-import:12_3_7")
      (libsource (lib "eagle-import") (part "RESISTOR_12_3_7R_0307/12"))
    )
    (comp (ref "R33")
      (value "47K")
      (footprint "eagle-import:12_3_7")
      (libsource (lib "eagle-import") (part "RESISTOR_12_3_7R_0307/12"))
    )
    (comp (ref "R34")
      (value "47 K")
      (footprint "eagle-import:12_3_7")
      (libsource (lib "eagle-import") (part "RESISTOR_12_3_7R_0307/12"))
    )
    (comp (ref "R35")
      (value "470 K")
      (footprint "eagle-import:12_3_7")
      (libsource (lib "eagle-import") (part "RESISTOR_12_3_7R_0307/12"))
    )
    (comp (ref "R36")
      (value "1 K")
      (footprint "eagle-import:12_3_7")
      (libsource (lib "eagle-import") (part "RESISTOR_12_3_7R_0307/12"))
    )
    (comp (ref "R37")
      (value "6.8 K")
      (footprint "eagle-import:0307_12")
      (libsource (lib "eagle-import") (part "R_0307/12R_0307/12"))
    )
    (comp (ref "R38")
      (value "1k")
      (footprint "eagle-import:12_3_7")
      (libsource (lib "eagle-import") (part "RESISTOR_12_3_7R_0307/12"))
    )
    (comp (ref "R39")
      (value "390")
      (footprint "eagle-import:0307_12")
      (libsource (lib "eagle-import") (part "R_0307/12R_0307/12"))
    )
    (comp (ref "R41")
      (value "1 M")
      (footprint "eagle-import:0307_12")
      (libsource (lib "eagle-import") (part "R_0307/12R_0307/12"))
    )
    (comp (ref "R42")
      (value "33")
      (footprint "eagle-import:12_3_7")
      (libsource (lib "eagle-import") (part "RESISTOR_12_3_7R_0307/12"))
    )
    (comp (ref "R43")
      (value "3.3 K")
      (footprint "eagle-import:0307_12")
      (libsource (lib "eagle-import") (part "R_0307/12R_0307/12"))
    )
    (comp (ref "R44")
      (value "3.3 K")
      (footprint "eagle-import:0307_12")
      (libsource (lib "eagle-import") (part "R_0307/12R_0307/12"))
    )
    (comp (ref "R45")
      (value "3.3 K")
      (footprint "eagle-import:0307_12")
      (libsource (lib "eagle-import") (part "R_0307/12R_0307/12"))
    )
    (comp (ref "R46")
      (value "2.1 K")
      (footprint "eagle-import:0307_12")
      (libsource (lib "eagle-import") (part "R_0307/12R_0307/12"))
    )
    (comp (ref "R48")
      (value "300")
      (footprint "eagle-import:0204V")
      (libsource (lib "eagle-import") (part "R-EU_0204/2V"))
    )
    (comp (ref "R49")
      (value "470")
      (footprint "eagle-import:0204V")
      (libsource (lib "eagle-import") (part "R-EU_0204/2V"))
    )
    (comp (ref "R50")
      (value "1 M")
      (footprint "eagle-import:0204V")
      (libsource (lib "eagle-import") (part "R-EU_0204/2V"))
    )
    (comp (ref "RF1")
      (value "RF-MODULATOR")
      (footprint "eagle-import:RF-MODULATOR")
      (libsource (lib "eagle-import") (part "RF-MODULATOR"))
    )
    (comp (ref "RP1")
      (value "33")
      (footprint "eagle-import:RESISTOR_PACK_4")
      (libsource (lib "eagle-import") (part "RESISTOR_PACK_4"))
    )
    (comp (ref "RP2")
      (value "33")
      (footprint "eagle-import:RESISTOR_PACK_4")
      (libsource (lib "eagle-import") (part "RESISTOR_PACK_4"))
    )
    (comp (ref "RP3")
      (value "3.3 K")
      (footprint "eagle-import:RP8")
      (libsource (lib "eagle-import") (part "RP8"))
    )
    (comp (ref "RP4")
      (value "3.3 K")
      (footprint "eagle-import:RP9")
      (libsource (lib "eagle-import") (part "RP9"))
    )
    (comp (ref "SW1")
      (value "DPDT_SWITCH")
      (footprint "eagle-import:DPDT_SWITCH")
      (libsource (lib "eagle-import") (part "DPDT_SWITCH"))
    )
    (comp (ref "U1")
      (value "6526")
      (footprint "eagle-import:DIP40")
      (libsource (lib "eagle-import") (part "6526"))
    )
    (comp (ref "U2")
      (value "6526")
      (footprint "eagle-import:DIP40")
      (libsource (lib "eagle-import") (part "6526"))
    )
    (comp (ref "U3")
      (value "2364")
      (footprint "eagle-import:DIL24")
      (libsource (lib "eagle-import") (part "2364"))
    )
    (comp (ref "U4")
      (value "2364")
      (footprint "eagle-import:DIL24")
      (libsource (lib "eagle-import") (part "2364"))
    )
    (comp (ref "U5")
      (value "2332")
      (footprint "eagle-import:DIL24")
      (libsource (lib "eagle-import") (part "2332"))
    )
    (comp (ref "U6")
      (value "2114")
      (footprint "eagle-import:DIL18")
      (libsource (lib "eagle-import") (part "2114"))
    )
    (comp (ref "U7")
      (value "6510")
      (footprint "eagle-import:DIP40")
      (libsource (lib "eagle-import") (part "6510"))
    )
    (comp (ref "U8")
      (value "SN7406NN")
      (footprint "eagle-import:DIL14")
      (libsource (lib "eagle-import") (part "SN7406NN"))
    )
    (comp (ref "U9")
      (value "4164")
      (footprint "eagle-import:DIL16")
      (libsource (lib "eagle-import") (part "4164"))
    )
    (comp (ref "U10")
      (value "4164")
      (footprint "eagle-import:DIL16")
      (libsource (lib "eagle-import") (part "4164"))
    )
    (comp (ref "U11")
      (value "4164")
      (footprint "eagle-import:DIL16")
      (libsource (lib "eagle-import") (part "4164"))
    )
    (comp (ref "U12")
      (value "4164")
      (footprint "eagle-import:DIL16")
      (libsource (lib "eagle-import") (part "4164"))
    )
    (comp (ref "U13")
      (value "74LS257N")
      (footprint "eagle-import:DIL16@1")
      (libsource (lib "eagle-import") (part "74257NLS"))
    )
    (comp (ref "U14")
      (value "74LS258N")
      (footprint "eagle-import:DIL16@1")
      (libsource (lib "eagle-import") (part "74258NLS"))
    )
    (comp (ref "U15")
      (value "74LS139N")
      (footprint "eagle-import:DIL16@1")
      (libsource (lib "eagle-import") (part "74139NLS"))
    )
    (comp (ref "U16")
      (value "4066")
      (footprint "eagle-import:DIL14@1")
      (libsource (lib "eagle-import") (part "4066"))
    )
    (comp (ref "U17")
      (value "C64PLA")
      (footprint "eagle-import:DIL28")
      (libsource (lib "eagle-import") (part "C64PLA"))
    )
    (comp (ref "U18")
      (value "6581")
      (footprint "eagle-import:DIL28")
      (libsource (lib "eagle-import") (part "6581"))
    )
    (comp (ref "U19")
      (value "6569")
      (footprint "eagle-import:DIP40")
      (libsource (lib "eagle-import") (part "6569"))
    )
    (comp (ref "U20")
      (value "556DIGITAL")
      (footprint "eagle-import:DIL14")
      (libsource (lib "eagle-import") (part "556DIGITAL"))
    )
    (comp (ref "U21")
      (value "4164")
      (footprint "eagle-import:DIL16")
      (libsource (lib "eagle-import") (part "4164"))
    )
    (comp (ref "U22")
      (value "4164")
      (footprint "eagle-import:DIL16")
      (libsource (lib "eagle-import") (part "4164"))
    )
    (comp (ref "U23")
      (value "4164")
      (footprint "eagle-import:DIL16")
      (libsource (lib "eagle-import") (part "4164"))
    )
    (comp (ref "U24")
      (value "4164")
      (footprint "eagle-import:DIL16")
      (libsource (lib "eagle-import") (part "4164"))
    )
    (comp (ref "U25")
      (value "74LS257N")
      (footprint "eagle-import:DIL16@1")
      (libsource (lib "eagle-import") (part "74257NLS"))
    )
    (comp (ref "U26")
      (value "74LS373N")
      (footprint "eagle-import:DIL20")
      (libsource (lib "eagle-import") (part "74373NLS"))
    )
    (comp (ref "U27")
      (value "74LS08N")
      (footprint "eagle-import:DIL14@1")
      (libsource (lib "eagle-import") (part "7408NLS"))
    )
    (comp (ref "U28")
      (value "4066")
      (footprint "eagle-import:DIL14@1")
      (libsource (lib "eagle-import") (part "4066"))
    )
    (comp (ref "U29")
      (value "74LS74N")
      (footprint "eagle-import:DIL14@1")
      (libsource (lib "eagle-import") (part "7474NLS"))
    )
    (comp (ref "U30")
      (value "74LS193N")
      (footprint "eagle-import:DIL16@1")
      (libsource (lib "eagle-import") (part "74193NLS"))
    )
    (comp (ref "U31")
      (value "74629")
      (footprint "eagle-import:DIL16@1")
      (libsource (lib "eagle-import") (part "74629"))
    )
    (comp (ref "U32")
      (value "MC4044")
      (footprint "eagle-import:DIL14@1")
      (libsource (lib "eagle-import") (part "MC4044"))
    )
    (comp (ref "VR1")
      (value "VR")
      (footprint "eagle-import:TO220V")
      (libsource (lib "eagle-import") (part "VR"))
    )
    (comp (ref "VR2")
      (value "VR")
      (footprint "eagle-import:TO220V")
      (libsource (lib "eagle-import") (part "VR"))
    )
    (comp (ref "Y1")
      (value "17.73 MHz")
      (footprint "eagle-import:HC49TL-H")
      (libsource (lib "eagle-import") (part "HC49TL-H"))
    )
  )
  (nets
    (net (code "1") (name "+5Vc") (class "Default")
      (node (ref "C55") (pin "1") (pinfunction "1_1") (pintype "passive"))
      (node (ref "C61") (pin "1") (pinfunction "1_1") (pintype "passive"))
      (node (ref "C84") (pin "1") (pinfunction "1_1") (pintype "passive"))
      (node (ref "JP1") (pin "4") (pinfunction "4_4") (pintype "passive"))
      (node (ref "L1") (pin "2") (pinfunction "2_2") (pintype "passive"))
      (node (ref "Q7") (pin "1") (pinfunction "C_1") (pintype "passive"))
      (node (ref "R16") (pin "1") (pinfunction "1_1") (pintype "passive"))
      (node (ref "R23") (pin "1") (pinfunction "1_1") (pintype "passive"))
      (node (ref "R26") (pin "1") (pinfunction "1_1") (pintype "passive"))
      (node (ref "R27") (pin "E") (pinfunction "E_E") (pintype "passive"))
      (node (ref "U29") (pin "10") (pinfunction "PRE_10") (pintype "input"))
      (node (ref "U29") (pin "13") (pinfunction "CLR_13") (pintype "input"))
      (node (ref "U30") (pin "15") (pinfunction "A_15") (pintype "input"))
      (node (ref "U30") (pin "4") (pinfunction "CNT-DWN_4") (pintype "input"))
    )
    (net (code "2") (name "+5Vcan") (class "Default")
      (node (ref "C102") (pin "+") (pinfunction "+_+") (pintype "passive"))
      (node (ref "C103") (pin "1") (pinfunction "1_1") (pintype "passive"))
      (node (ref "C63") (pin "1") (pinfunction "1_1") (pintype "passive"))
      (node (ref "C64") (pin "+") (pinfunction "1_+") (pintype "passive"))
      (node (ref "C65") (pin "+") (pinfunction "1_+") (pintype "passive"))
      (node (ref "C66") (pin "1") (pinfunction "1_1") (pintype "passive"))
      (node (ref "FB22") (pin "2") (pinfunction "2_2") (pintype "passive"))
      (node (ref "L1") (pin "1") (pinfunction "1_1") (pintype "passive"))
      (node (ref "L2") (pin "1") (pinfunction "1_1") (pintype "passive"))
      (node (ref "VR2") (pin "3") (pinfunction "VO_3") (pintype "passive"))
    )
    (net (code "3") (name "+5Vvid") (class "Default")
      (node (ref "C67") (pin "1") (pinfunction "1_1") (pintype "passive"))
      (node (ref "C71") (pin "1") (pinfunction "1_1") (pintype "passive"))
      (node (ref "C77") (pin "1") (pinfunction "1_1") (pintype "passive"))
      (node (ref "L2") (pin "2") (pinfunction "2_2") (pintype "passive"))
      (node (ref "Q4") (pin "1") (pinfunction "C_1") (pintype "passive"))
      (node (ref "Q5") (pin "1") (pinfunction "C_1") (pintype "passive"))
      (node (ref "R13") (pin "1") (pinfunction "1_1") (pintype "passive"))
      (node (ref "R8") (pin "1") (pinfunction "1_1") (pintype "passive"))
    )
    (net (code "4") (name "+9V") (class "Default")
      (node (ref "C18") (pin "1") (pinfunction "1_1") (pintype "passive"))
      (node (ref "CR6") (pin "2") (pinfunction "C_2") (pintype "passive"))
      (node (ref "Q1") (pin "2") (pinfunction "C_2") (pintype "passive"))
      (node (ref "Q3") (pin "3") (pinfunction "C_3") (pintype "passive"))
      (node (ref "R2") (pin "1") (pinfunction "1_1") (pintype "passive"))
    )
    (net (code "5") (name "+12V") (class "Default")
      (node (ref "C52") (pin "1") (pinfunction "1_1") (pintype "passive"))
      (node (ref "C54") (pin "1") (pinfunction "1_1") (pintype "passive"))
      (node (ref "C57") (pin "+") (pinfunction "1_+") (pintype "passive"))
      (node (ref "C59") (pin "1") (pinfunction "1_1") (pintype "passive"))
      (node (ref "C62") (pin "+") (pinfunction "1_+") (pintype "passive"))
      (node (ref "C94") (pin "+") (pinfunction "1_+") (pintype "passive"))
      (node (ref "FB11") (pin "2") (pinfunction "2_2") (pintype "passive"))
      (node (ref "FB12") (pin "2") (pinfunction "2_2") (pintype "passive"))
      (node (ref "Q8") (pin "1") (pinfunction "C_1") (pintype "passive"))
      (node (ref "VR1") (pin "3") (pinfunction "VO_3") (pintype "passive"))
    )
    (net (code "6") (name "/A0") (class "Default")
      (node (ref "CN6") (pin "Y") (pinfunction "A0_Y") (pintype "output"))
      (node (ref "U1") (pin "38") (pinfunction "RS0_38") (pintype "input"))
      (node (ref "U18") (pin "9") (pinfunction "A0_9") (pintype "input"))
      (node (ref "U2") (pin "38") (pinfunction "RS0_38") (pintype "input"))
      (node (ref "U25") (pin "13") (pinfunction "4B_13") (pintype "input"))
      (node (ref "U26") (pin "19") (pinfunction "8Q_19") (pintype "tri_state"))
      (node (ref "U3") (pin "8") (pinfunction "A0_8") (pintype "input"))
      (node (ref "U4") (pin "8") (pinfunction "A0_8") (pintype "input"))
      (node (ref "U5") (pin "8") (pinfunction "A0_8") (pintype "input"))
      (node (ref "U6") (pin "5") (pinfunction "A0_5") (pintype "input"))
      (node (ref "U7") (pin "7") (pinfunction "A0_7") (pintype "tri_state"))
    )
    (net (code "7") (name "/A1") (class "Default")
      (node (ref "CN6") (pin "X") (pinfunction "A1_X") (pintype "output"))
      (node (ref "U1") (pin "37") (pinfunction "RS1_37") (pintype "input"))
      (node (ref "U18") (pin "10") (pinfunction "A1_10") (pintype "input"))
      (node (ref "U2") (pin "37") (pinfunction "RS1_37") (pintype "input"))
      (node (ref "U25") (pin "10") (pinfunction "3B_10") (pintype "input"))
      (node (ref "U26") (pin "16") (pinfunction "7Q_16") (pintype "tri_state"))
      (node (ref "U3") (pin "7") (pinfunction "A1_7") (pintype "input"))
      (node (ref "U4") (pin "7") (pinfunction "A1_7") (pintype "input"))
      (node (ref "U5") (pin "7") (pinfunction "A1_7") (pintype "input"))
      (node (ref "U6") (pin "6") (pinfunction "A1_6") (pintype "input"))
      (node (ref "U7") (pin "8") (pinfunction "A1_8") (pintype "tri_state"))
    )
    (net (code "8") (name "/A2") (class "Default")
      (node (ref "CN6") (pin "W") (pinfunction "A2_W") (pintype "output"))
      (node (ref "U1") (pin "36") (pinfunction "RS2_36") (pintype "input"))
      (node (ref "U18") (pin "11") (pinfunction "A2_11") (pintype "input"))
      (node (ref "U2") (pin "36") (pinfunction "RS2_36") (pintype "input"))
      (node (ref "U25") (pin "6") (pinfunction "2B_6") (pintype "input"))
      (node (ref "U26") (pin "15") (pinfunction "6Q_15") (pintype "tri_state"))
      (node (ref "U3") (pin "6") (pinfunction "A2_6") (pintype "input"))
      (node (ref "U4") (pin "6") (pinfunction "A2_6") (pintype "input"))
      (node (ref "U5") (pin "6") (pinfunction "A2_6") (pintype "input"))
      (node (ref "U6") (pin "7") (pinfunction "A2_7") (pintype "input"))
      (node (ref "U7") (pin "9") (pinfunction "A2_9") (pintype "tri_state"))
    )
    (net (code "9") (name "/A3") (class "Default")
      (node (ref "CN6") (pin "V") (pinfunction "A3_V") (pintype "output"))
      (node (ref "U1") (pin "35") (pinfunction "RS3_35") (pintype "input"))
      (node (ref "U18") (pin "12") (pinfunction "A3_12") (pintype "input"))
      (node (ref "U2") (pin "35") (pinfunction "RS3_35") (pintype "input"))
      (node (ref "U25") (pin "3") (pinfunction "1B_3") (pintype "input"))
      (node (ref "U26") (pin "12") (pinfunction "5Q_12") (pintype "tri_state"))
      (node (ref "U3") (pin "5") (pinfunction "A3_5") (pintype "input"))
      (node (ref "U4") (pin "5") (pinfunction "A3_5") (pintype "input"))
      (node (ref "U5") (pin "5") (pinfunction "A3_5") (pintype "input"))
      (node (ref "U6") (pin "4") (pinfunction "A3_4") (pintype "input"))
      (node (ref "U7") (pin "10") (pinfunction "A3_10") (pintype "tri_state"))
    )
    (net (code "10") (name "/A4") (class "Default")
      (node (ref "CN6") (pin "U") (pinfunction "A4_U") (pintype "output"))
      (node (ref "U13") (pin "13") (pinfunction "4B_13") (pintype "input"))
      (node (ref "U18") (pin "13") (pinfunction "A4_13") (pintype "input"))
      (node (ref "U26") (pin "9") (pinfunction "4Q_9") (pintype "tri_state"))
      (node (ref "U3") (pin "4") (pinfunction "A4_4") (pintype "input"))
      (node (ref "U4") (pin "4") (pinfunction "A4_4") (pintype "input"))
      (node (ref "U5") (pin "4") (pinfunction "A4_4") (pintype "input"))
      (node (ref "U6") (pin "3") (pinfunction "A4_3") (pintype "input"))
      (node (ref "U7") (pin "11") (pinfunction "A4_11") (pintype "tri_state"))
    )
    (net (code "11") (name "/A5") (class "Default")
      (node (ref "CN6") (pin "T") (pinfunction "A5_T") (pintype "output"))
      (node (ref "U13") (pin "6") (pinfunction "2B_6") (pintype "input"))
      (node (ref "U26") (pin "6") (pinfunction "3Q_6") (pintype "tri_state"))
      (node (ref "U3") (pin "3") (pinfunction "A5_3") (pintype "input"))
      (node (ref "U4") (pin "3") (pinfunction "A5_3") (pintype "input"))
      (node (ref "U5") (pin "3") (pinfunction "A5_3") (pintype "input"))
      (node (ref "U6") (pin "2") (pinfunction "A5_2") (pintype "input"))
      (node (ref "U7") (pin "12") (pinfunction "A5_12") (pintype "tri_state"))
    )
    (net (code "12") (name "/A6") (class "Default")
      (node (ref "CN6") (pin "S") (pinfunction "A6_S") (pintype "output"))
      (node (ref "U13") (pin "3") (pinfunction "1B_3") (pintype "input"))
      (node (ref "U26") (pin "5") (pinfunction "2Q_5") (pintype "tri_state"))
      (node (ref "U3") (pin "2") (pinfunction "A6_2") (pintype "input"))
      (node (ref "U4") (pin "2") (pinfunction "A6_2") (pintype "input"))
      (node (ref "U5") (pin "2") (pinfunction "A6_2") (pintype "input"))
      (node (ref "U6") (pin "1") (pinfunction "A6_1") (pintype "input"))
      (node (ref "U7") (pin "13") (pinfunction "A6_13") (pintype "tri_state"))
    )
    (net (code "13") (name "/A7") (class "Default")
      (node (ref "CN6") (pin "R") (pinfunction "A7_R") (pintype "output"))
      (node (ref "U13") (pin "10") (pinfunction "3B_10") (pintype "input"))
      (node (ref "U26") (pin "2") (pinfunction "1Q_2") (pintype "tri_state"))
      (node (ref "U3") (pin "1") (pinfunction "A7_1") (pintype "input"))
      (node (ref "U4") (pin "1") (pinfunction "A7_1") (pintype "input"))
      (node (ref "U5") (pin "1") (pinfunction "A7_1") (pintype "input"))
      (node (ref "U6") (pin "17") (pinfunction "A7_17") (pintype "input"))
      (node (ref "U7") (pin "14") (pinfunction "A7_14") (pintype "tri_state"))
    )
    (net (code "14") (name "/A8") (class "Default")
      (node (ref "CN6") (pin "P") (pinfunction "A8_P") (pintype "output"))
      (node (ref "U15") (pin "14") (pinfunction "A_14") (pintype "input"))
      (node (ref "U19") (pin "32") (pinfunction "A8_32") (pintype "input"))
      (node (ref "U25") (pin "14") (pinfunction "4A_14") (pintype "input"))
      (node (ref "U3") (pin "23") (pinfunction "A8_23") (pintype "input"))
      (node (ref "U4") (pin "23") (pinfunction "A8_23") (pintype "input"))
      (node (ref "U5") (pin "23") (pinfunction "A8_23") (pintype "input"))
      (node (ref "U6") (pin "16") (pinfunction "A8_16") (pintype "input"))
      (node (ref "U7") (pin "15") (pinfunction "A8_15") (pintype "tri_state"))
    )
    (net (code "15") (name "/A9") (class "Default")
      (node (ref "CN6") (pin "N") (pinfunction "A9_N") (pintype "output"))
      (node (ref "U15") (pin "13") (pinfunction "B_13") (pintype "input"))
      (node (ref "U19") (pin "33") (pinfunction "A9_33") (pintype "input"))
      (node (ref "U25") (pin "11") (pinfunction "3A_11") (pintype "input"))
      (node (ref "U3") (pin "22") (pinfunction "A9_22") (pintype "input"))
      (node (ref "U4") (pin "22") (pinfunction "A9_22") (pintype "input"))
      (node (ref "U5") (pin "22") (pinfunction "A9_22") (pintype "input"))
      (node (ref "U6") (pin "15") (pinfunction "A9_15") (pintype "input"))
      (node (ref "U7") (pin "16") (pinfunction "A9_16") (pintype "tri_state"))
    )
    (net (code "16") (name "/A10") (class "Default")
      (node (ref "CN6") (pin "M") (pinfunction "A10_M") (pintype "output"))
      (node (ref "U15") (pin "2") (pinfunction "A_2") (pintype "input"))
      (node (ref "U19") (pin "34") (pinfunction "A10_34") (pintype "input"))
      (node (ref "U25") (pin "5") (pinfunction "2A_5") (pintype "input"))
      (node (ref "U3") (pin "19") (pinfunction "A10_19") (pintype "input"))
      (node (ref "U4") (pin "19") (pinfunction "A10_19") (pintype "input"))
      (node (ref "U5") (pin "19") (pinfunction "A10_19") (pintype "input"))
      (node (ref "U7") (pin "17") (pinfunction "A10_17") (pintype "tri_state"))
    )
    (net (code "17") (name "/A11") (class "Default")
      (node (ref "CN6") (pin "L") (pinfunction "A11_L") (pintype "output"))
      (node (ref "U15") (pin "3") (pinfunction "B_3") (pintype "input"))
      (node (ref "U19") (pin "23") (pinfunction "A11_23") (pintype "input"))
      (node (ref "U25") (pin "2") (pinfunction "1A_2") (pintype "input"))
      (node (ref "U3") (pin "18") (pinfunction "A11_18") (pintype "input"))
      (node (ref "U4") (pin "18") (pinfunction "A11_18") (pintype "input"))
      (node (ref "U5") (pin "18") (pinfunction "A11_18") (pintype "input"))
      (node (ref "U7") (pin "18") (pinfunction "A11_18") (pintype "tri_state"))
    )
    (net (code "18") (name "/A12") (class "Default")
      (node (ref "CN6") (pin "K") (pinfunction "A12_K") (pintype "output"))
      (node (ref "RP4") (pin "9") (pinfunction "X_9") (pintype "passive"))
      (node (ref "U13") (pin "14") (pinfunction "4A_14") (pintype "input"))
      (node (ref "U17") (pin "27") (pinfunction "A12_27") (pintype "input"))
      (node (ref "U3") (pin "21") (pinfunction "A12_21") (pintype "input"))
      (node (ref "U4") (pin "21") (pinfunction "A12_21") (pintype "input"))
      (node (ref "U7") (pin "19") (pinfunction "A12_19") (pintype "tri_state"))
    )
    (net (code "19") (name "/A13") (class "Default")
      (node (ref "CN6") (pin "J") (pinfunction "A13_J") (pintype "output"))
      (node (ref "RP4") (pin "7") (pinfunction "X_7") (pintype "passive"))
      (node (ref "U13") (pin "5") (pinfunction "2A_5") (pintype "input"))
      (node (ref "U17") (pin "2") (pinfunction "A13_2") (pintype "input"))
      (node (ref "U7") (pin "20") (pinfunction "A13_20") (pintype "tri_state"))
    )
    (net (code "20") (name "/A14") (class "Default")
      (node (ref "CN6") (pin "H") (pinfunction "A14_H") (pintype "output"))
      (node (ref "RP4") (pin "5") (pinfunction "X_5") (pintype "passive"))
      (node (ref "U13") (pin "2") (pinfunction "1A_2") (pintype "input"))
      (node (ref "U17") (pin "3") (pinfunction "A14_3") (pintype "input"))
      (node (ref "U7") (pin "22") (pinfunction "A14_22") (pintype "tri_state"))
    )
    (net (code "21") (name "/A15") (class "Default")
      (node (ref "CN6") (pin "F") (pinfunction "A15_F") (pintype "output"))
      (node (ref "RP4") (pin "4") (pinfunction "X_4") (pintype "passive"))
      (node (ref "U13") (pin "11") (pinfunction "3A_11") (pintype "input"))
      (node (ref "U17") (pin "4") (pinfunction "A15_4") (pintype "input"))
      (node (ref "U7") (pin "23") (pinfunction "A15_23") (pintype "tri_state"))
    )
    (net (code "22") (name "/D0") (class "Default")
      (node (ref "CN6") (pin "21") (pinfunction "D0_21") (pintype "bidirectional"))
      (node (ref "U1") (pin "33") (pinfunction "D0_33") (pintype "bidirectional"))
      (node (ref "U16") (pin "1") (pinfunction "Y0_1") (pintype "passive"))
      (node (ref "U18") (pin "15") (pinfunction "D0_15") (pintype "tri_state"))
      (node (ref "U19") (pin "7") (pinfunction "D0_7") (pintype "tri_state"))
      (node (ref "U2") (pin "33") (pinfunction "D0_33") (pintype "bidirectional"))
      (node (ref "U21") (pin "14") (pinfunction "DO_14") (pintype "tri_state"))
      (node (ref "U21") (pin "2") (pinfunction "DI_2") (pintype "input"))
      (node (ref "U3") (pin "9") (pinfunction "O0_9") (pintype "tri_state"))
      (node (ref "U4") (pin "9") (pinfunction "O0_9") (pintype "tri_state"))
      (node (ref "U5") (pin "9") (pinfunction "O0_9") (pintype "tri_state"))
      (node (ref "U7") (pin "37") (pinfunction "D0_37") (pintype "bidirectional"))
    )
    (net (code "23") (name "/D1") (class "Default")
      (node (ref "CN6") (pin "20") (pinfunction "D1_20") (pintype "bidirectional"))
      (node (ref "U1") (pin "32") (pinfunction "D1_32") (pintype "bidirectional"))
      (node (ref "U16") (pin "4") (pinfunction "Y1_4") (pintype "passive"))
      (node (ref "U18") (pin "16") (pinfunction "D1_16") (pintype "tri_state"))
      (node (ref "U19") (pin "6") (pinfunction "D1_6") (pintype "tri_state"))
      (node (ref "U2") (pin "32") (pinfunction "D1_32") (pintype "bidirectional"))
      (node (ref "U3") (pin "10") (pinfunction "O1_10") (pintype "tri_state"))
      (node (ref "U4") (pin "10") (pinfunction "O1_10") (pintype "tri_state"))
      (node (ref "U5") (pin "10") (pinfunction "O1_10") (pintype "tri_state"))
      (node (ref "U7") (pin "36") (pinfunction "D1_36") (pintype "bidirectional"))
      (node (ref "U9") (pin "14") (pinfunction "DO_14") (pintype "tri_state"))
      (node (ref "U9") (pin "2") (pinfunction "DI_2") (pintype "input"))
    )
    (net (code "24") (name "/D2") (class "Default")
      (node (ref "CN6") (pin "19") (pinfunction "D2_19") (pintype "bidirectional"))
      (node (ref "U1") (pin "31") (pinfunction "D2_31") (pintype "bidirectional"))
      (node (ref "U16") (pin "8") (pinfunction "Y2_8") (pintype "passive"))
      (node (ref "U18") (pin "17") (pinfunction "D2_17") (pintype "tri_state"))
      (node (ref "U19") (pin "5") (pinfunction "D2_5") (pintype "tri_state"))
      (node (ref "U2") (pin "31") (pinfunction "D2_31") (pintype "bidirectional"))
      (node (ref "U22") (pin "14") (pinfunction "DO_14") (pintype "tri_state"))
      (node (ref "U22") (pin "2") (pinfunction "DI_2") (pintype "input"))
      (node (ref "U3") (pin "11") (pinfunction "O2_11") (pintype "tri_state"))
      (node (ref "U4") (pin "11") (pinfunction "O2_11") (pintype "tri_state"))
      (node (ref "U5") (pin "11") (pinfunction "O2_11") (pintype "tri_state"))
      (node (ref "U7") (pin "35") (pinfunction "D2_35") (pintype "bidirectional"))
    )
    (net (code "25") (name "/D3") (class "Default")
      (node (ref "CN6") (pin "18") (pinfunction "D3_18") (pintype "bidirectional"))
      (node (ref "U1") (pin "30") (pinfunction "D3_30") (pintype "bidirectional"))
      (node (ref "U10") (pin "14") (pinfunction "DO_14") (pintype "tri_state"))
      (node (ref "U10") (pin "2") (pinfunction "DI_2") (pintype "input"))
      (node (ref "U16") (pin "11") (pinfunction "Y3_11") (pintype "passive"))
      (node (ref "U18") (pin "18") (pinfunction "D3_18") (pintype "tri_state"))
      (node (ref "U19") (pin "4") (pinfunction "D3_4") (pintype "tri_state"))
      (node (ref "U2") (pin "30") (pinfunction "D3_30") (pintype "bidirectional"))
      (node (ref "U3") (pin "13") (pinfunction "O3_13") (pintype "tri_state"))
      (node (ref "U4") (pin "13") (pinfunction "O3_13") (pintype "tri_state"))
      (node (ref "U5") (pin "13") (pinfunction "O3_13") (pintype "tri_state"))
      (node (ref "U7") (pin "34") (pinfunction "D3_34") (pintype "bidirectional"))
    )
    (net (code "26") (name "/D4") (class "Default")
      (node (ref "CN6") (pin "17") (pinfunction "D4_17") (pintype "bidirectional"))
      (node (ref "U1") (pin "29") (pinfunction "D4_29") (pintype "bidirectional"))
      (node (ref "U18") (pin "19") (pinfunction "D4_19") (pintype "tri_state"))
      (node (ref "U19") (pin "3") (pinfunction "D4_3") (pintype "tri_state"))
      (node (ref "U2") (pin "29") (pinfunction "D4_29") (pintype "bidirectional"))
      (node (ref "U23") (pin "14") (pinfunction "DO_14") (pintype "tri_state"))
      (node (ref "U23") (pin "2") (pinfunction "DI_2") (pintype "input"))
      (node (ref "U3") (pin "14") (pinfunction "O4_14") (pintype "tri_state"))
      (node (ref "U4") (pin "14") (pinfunction "O4_14") (pintype "tri_state"))
      (node (ref "U5") (pin "14") (pinfunction "O4_14") (pintype "tri_state"))
      (node (ref "U7") (pin "33") (pinfunction "D4_33") (pintype "bidirectional"))
    )
    (net (code "27") (name "/D5") (class "Default")
      (node (ref "CN6") (pin "16") (pinfunction "D5_16") (pintype "bidirectional"))
      (node (ref "U1") (pin "28") (pinfunction "D5_28") (pintype "bidirectional"))
      (node (ref "U11") (pin "14") (pinfunction "DO_14") (pintype "tri_state"))
      (node (ref "U11") (pin "2") (pinfunction "DI_2") (pintype "input"))
      (node (ref "U18") (pin "20") (pinfunction "D5_20") (pintype "tri_state"))
      (node (ref "U19") (pin "2") (pinfunction "D5_2") (pintype "tri_state"))
      (node (ref "U2") (pin "28") (pinfunction "D5_28") (pintype "bidirectional"))
      (node (ref "U3") (pin "15") (pinfunction "O5_15") (pintype "tri_state"))
      (node (ref "U4") (pin "15") (pinfunction "O5_15") (pintype "tri_state"))
      (node (ref "U5") (pin "15") (pinfunction "O5_15") (pintype "tri_state"))
      (node (ref "U7") (pin "32") (pinfunction "D5_32") (pintype "bidirectional"))
    )
    (net (code "28") (name "/D6") (class "Default")
      (node (ref "CN6") (pin "15") (pinfunction "D6_15") (pintype "bidirectional"))
      (node (ref "U1") (pin "27") (pinfunction "D6_27") (pintype "bidirectional"))
      (node (ref "U18") (pin "21") (pinfunction "D6_21") (pintype "tri_state"))
      (node (ref "U19") (pin "1") (pinfunction "D6_1") (pintype "tri_state"))
      (node (ref "U2") (pin "27") (pinfunction "D6_27") (pintype "bidirectional"))
      (node (ref "U24") (pin "14") (pinfunction "DO_14") (pintype "tri_state"))
      (node (ref "U24") (pin "2") (pinfunction "DI_2") (pintype "input"))
      (node (ref "U3") (pin "16") (pinfunction "O6_16") (pintype "tri_state"))
      (node (ref "U4") (pin "16") (pinfunction "O6_16") (pintype "tri_state"))
      (node (ref "U5") (pin "16") (pinfunction "O6_16") (pintype "tri_state"))
      (node (ref "U7") (pin "31") (pinfunction "D6_31") (pintype "bidirectional"))
    )
    (net (code "29") (name "/D7") (class "Default")
      (node (ref "CN6") (pin "14") (pinfunction "D7_14") (pintype "bidirectional"))
      (node (ref "U1") (pin "26") (pinfunction "D7_26") (pintype "bidirectional"))
      (node (ref "U12") (pin "14") (pinfunction "DO_14") (pintype "tri_state"))
      (node (ref "U12") (pin "2") (pinfunction "DI_2") (pintype "input"))
      (node (ref "U18") (pin "22") (pinfunction "D7_22") (pintype "tri_state"))
      (node (ref "U19") (pin "39") (pinfunction "D7_39") (pintype "tri_state"))
      (node (ref "U2") (pin "26") (pinfunction "D7_26") (pintype "bidirectional"))
      (node (ref "U3") (pin "17") (pinfunction "O7_17") (pintype "tri_state"))
      (node (ref "U4") (pin "17") (pinfunction "O7_17") (pintype "tri_state"))
      (node (ref "U5") (pin "17") (pinfunction "O7_17") (pintype "tri_state"))
      (node (ref "U7") (pin "30") (pinfunction "D7_30") (pintype "bidirectional"))
    )
    (net (code "30") (name "/MA0") (class "Default")
      (node (ref "RP2") (pin "4") (pinfunction "2_4") (pintype "passive"))
      (node (ref "U10") (pin "5") (pinfunction "A0_5") (pintype "input"))
      (node (ref "U11") (pin "5") (pinfunction "A0_5") (pintype "input"))
      (node (ref "U12") (pin "5") (pinfunction "A0_5") (pintype "input"))
      (node (ref "U21") (pin "5") (pinfunction "A0_5") (pintype "input"))
      (node (ref "U22") (pin "5") (pinfunction "A0_5") (pintype "input"))
      (node (ref "U23") (pin "5") (pinfunction "A0_5") (pintype "input"))
      (node (ref "U24") (pin "5") (pinfunction "A0_5") (pintype "input"))
      (node (ref "U9") (pin "5") (pinfunction "A0_5") (pintype "input"))
    )
    (net (code "31") (name "/MA1") (class "Default")
      (node (ref "RP2") (pin "8") (pinfunction "2_8") (pintype "passive"))
      (node (ref "U10") (pin "7") (pinfunction "A1_7") (pintype "input"))
      (node (ref "U11") (pin "7") (pinfunction "A1_7") (pintype "input"))
      (node (ref "U12") (pin "7") (pinfunction "A1_7") (pintype "input"))
      (node (ref "U21") (pin "7") (pinfunction "A1_7") (pintype "input"))
      (node (ref "U22") (pin "7") (pinfunction "A1_7") (pintype "input"))
      (node (ref "U23") (pin "7") (pinfunction "A1_7") (pintype "input"))
      (node (ref "U24") (pin "7") (pinfunction "A1_7") (pintype "input"))
      (node (ref "U9") (pin "7") (pinfunction "A1_7") (pintype "input"))
    )
    (net (code "32") (name "/MA2") (class "Default")
      (node (ref "RP2") (pin "6") (pinfunction "2_6") (pintype "passive"))
      (node (ref "U10") (pin "6") (pinfunction "A2_6") (pintype "input"))
      (node (ref "U11") (pin "6") (pinfunction "A2_6") (pintype "input"))
      (node (ref "U12") (pin "6") (pinfunction "A2_6") (pintype "input"))
      (node (ref "U21") (pin "6") (pinfunction "A2_6") (pintype "input"))
      (node (ref "U22") (pin "6") (pinfunction "A2_6") (pintype "input"))
      (node (ref "U23") (pin "6") (pinfunction "A2_6") (pintype "input"))
      (node (ref "U24") (pin "6") (pinfunction "A2_6") (pintype "input"))
      (node (ref "U9") (pin "6") (pinfunction "A2_6") (pintype "input"))
    )
    (net (code "33") (name "/MA3") (class "Default")
      (node (ref "RP2") (pin "2") (pinfunction "2_2") (pintype "passive"))
      (node (ref "U10") (pin "12") (pinfunction "A3_12") (pintype "input"))
      (node (ref "U11") (pin "12") (pinfunction "A3_12") (pintype "input"))
      (node (ref "U12") (pin "12") (pinfunction "A3_12") (pintype "input"))
      (node (ref "U21") (pin "12") (pinfunction "A3_12") (pintype "input"))
      (node (ref "U22") (pin "12") (pinfunction "A3_12") (pintype "input"))
      (node (ref "U23") (pin "12") (pinfunction "A3_12") (pintype "input"))
      (node (ref "U24") (pin "12") (pinfunction "A3_12") (pintype "input"))
      (node (ref "U9") (pin "12") (pinfunction "A3_12") (pintype "input"))
    )
    (net (code "34") (name "/MA4") (class "Default")
      (node (ref "RP1") (pin "4") (pinfunction "2_4") (pintype "passive"))
      (node (ref "U10") (pin "11") (pinfunction "A4_11") (pintype "input"))
      (node (ref "U11") (pin "11") (pinfunction "A4_11") (pintype "input"))
      (node (ref "U12") (pin "11") (pinfunction "A4_11") (pintype "input"))
      (node (ref "U21") (pin "11") (pinfunction "A4_11") (pintype "input"))
      (node (ref "U22") (pin "11") (pinfunction "A4_11") (pintype "input"))
      (node (ref "U23") (pin "11") (pinfunction "A4_11") (pintype "input"))
      (node (ref "U24") (pin "11") (pinfunction "A4_11") (pintype "input"))
      (node (ref "U9") (pin "11") (pinfunction "A4_11") (pintype "input"))
    )
    (net (code "35") (name "/MA5") (class "Default")
      (node (ref "RP1") (pin "6") (pinfunction "2_6") (pintype "passive"))
      (node (ref "U10") (pin "10") (pinfunction "A5_10") (pintype "input"))
      (node (ref "U11") (pin "10") (pinfunction "A5_10") (pintype "input"))
      (node (ref "U12") (pin "10") (pinfunction "A5_10") (pintype "input"))
      (node (ref "U21") (pin "10") (pinfunction "A5_10") (pintype "input"))
      (node (ref "U22") (pin "10") (pinfunction "A5_10") (pintype "input"))
      (node (ref "U23") (pin "10") (pinfunction "A5_10") (pintype "input"))
      (node (ref "U24") (pin "10") (pinfunction "A5_10") (pintype "input"))
      (node (ref "U9") (pin "10") (pinfunction "A5_10") (pintype "input"))
    )
    (net (code "36") (name "/MA6") (class "Default")
      (node (ref "RP1") (pin "2") (pinfunction "2_2") (pintype "passive"))
      (node (ref "U10") (pin "13") (pinfunction "A6_13") (pintype "input"))
      (node (ref "U11") (pin "13") (pinfunction "A6_13") (pintype "input"))
      (node (ref "U12") (pin "13") (pinfunction "A6_13") (pintype "input"))
      (node (ref "U21") (pin "13") (pinfunction "A6_13") (pintype "input"))
      (node (ref "U22") (pin "13") (pinfunction "A6_13") (pintype "input"))
      (node (ref "U23") (pin "13") (pinfunction "A6_13") (pintype "input"))
      (node (ref "U24") (pin "13") (pinfunction "A6_13") (pintype "input"))
      (node (ref "U9") (pin "13") (pinfunction "A6_13") (pintype "input"))
    )
    (net (code "37") (name "/MA7") (class "Default")
      (node (ref "RP1") (pin "8") (pinfunction "2_8") (pintype "passive"))
      (node (ref "U10") (pin "9") (pinfunction "A7_9") (pintype "input"))
      (node (ref "U11") (pin "9") (pinfunction "A7_9") (pintype "input"))
      (node (ref "U12") (pin "9") (pinfunction "A7_9") (pintype "input"))
      (node (ref "U21") (pin "9") (pinfunction "A7_9") (pintype "input"))
      (node (ref "U22") (pin "9") (pinfunction "A7_9") (pintype "input"))
      (node (ref "U23") (pin "9") (pinfunction "A7_9") (pintype "input"))
      (node (ref "U24") (pin "9") (pinfunction "A7_9") (pintype "input"))
      (node (ref "U9") (pin "9") (pinfunction "A7_9") (pintype "input"))
    )
    (net (code "38") (name "/NA0") (class "Default")
      (node (ref "RP2") (pin "3") (pinfunction "1_3") (pintype "passive"))
      (node (ref "U19") (pin "24") (pinfunction "A0/A8_24") (pintype "bidirectional"))
      (node (ref "U25") (pin "12") (pinfunction "4Y_12") (pintype "tri_state"))
      (node (ref "U26") (pin "18") (pinfunction "8D_18") (pintype "input"))
    )
    (net (code "39") (name "/NA1") (class "Default")
      (node (ref "RP2") (pin "7") (pinfunction "1_7") (pintype "passive"))
      (node (ref "U19") (pin "25") (pinfunction "A1/A9_25") (pintype "bidirectional"))
      (node (ref "U25") (pin "9") (pinfunction "3Y_9") (pintype "tri_state"))
      (node (ref "U26") (pin "17") (pinfunction "7D_17") (pintype "input"))
    )
    (net (code "40") (name "/NA2") (class "Default")
      (node (ref "RP2") (pin "5") (pinfunction "1_5") (pintype "passive"))
      (node (ref "U19") (pin "26") (pinfunction "A2/A10_26") (pintype "bidirectional"))
      (node (ref "U25") (pin "7") (pinfunction "2Y_7") (pintype "tri_state"))
      (node (ref "U26") (pin "14") (pinfunction "6D_14") (pintype "input"))
    )
    (net (code "41") (name "/NA3") (class "Default")
      (node (ref "RP2") (pin "1") (pinfunction "1_1") (pintype "passive"))
      (node (ref "U19") (pin "27") (pinfunction "A3/A11_27") (pintype "bidirectional"))
      (node (ref "U25") (pin "4") (pinfunction "1Y_4") (pintype "tri_state"))
      (node (ref "U26") (pin "13") (pinfunction "5D_13") (pintype "input"))
    )
    (net (code "42") (name "/NA4") (class "Default")
      (node (ref "RP1") (pin "3") (pinfunction "1_3") (pintype "passive"))
      (node (ref "U13") (pin "12") (pinfunction "4Y_12") (pintype "tri_state"))
      (node (ref "U17") (pin "20") (pinfunction "VA12_20") (pintype "input"))
      (node (ref "U19") (pin "28") (pinfunction "A4/A12_28") (pintype "bidirectional"))
      (node (ref "U26") (pin "8") (pinfunction "4D_8") (pintype "input"))
    )
    (net (code "43") (name "/NA5") (class "Default")
      (node (ref "RP1") (pin "5") (pinfunction "1_5") (pintype "passive"))
      (node (ref "U13") (pin "7") (pinfunction "2Y_7") (pintype "tri_state"))
      (node (ref "U17") (pin "21") (pinfunction "VA13_21") (pintype "input"))
      (node (ref "U19") (pin "29") (pinfunction "A5/A13_29") (pintype "bidirectional"))
      (node (ref "U26") (pin "7") (pinfunction "3D_7") (pintype "input"))
    )
    (net (code "44") (name "/NA6") (class "Default")
      (node (ref "RP1") (pin "1") (pinfunction "1_1") (pintype "passive"))
      (node (ref "U13") (pin "4") (pinfunction "1Y_4") (pintype "tri_state"))
      (node (ref "U14") (pin "4") (pinfunction "1Y_4") (pintype "tri_state"))
      (node (ref "U26") (pin "4") (pinfunction "2D_4") (pintype "input"))
    )
    (net (code "45") (name "/NA7") (class "Default")
      (node (ref "RP1") (pin "7") (pinfunction "1_7") (pintype "passive"))
      (node (ref "U13") (pin "9") (pinfunction "3Y_9") (pintype "tri_state"))
      (node (ref "U14") (pin "7") (pinfunction "2Y_7") (pintype "tri_state"))
      (node (ref "U26") (pin "3") (pinfunction "1D_3") (pintype "input"))
    )
    (net (code "46") (name "GND") (class "Default")
      (node (ref "C1") (pin "2") (pinfunction "2_2") (pintype "passive"))
      (node (ref "C100") (pin "2") (pinfunction "2_2") (pintype "passive"))
      (node (ref "C101") (pin "2") (pinfunction "2_2") (pintype "passive"))
      (node (ref "C102") (pin "-") (pinfunction "-_-") (pintype "passive"))
      (node (ref "C103") (pin "2") (pinfunction "2_2") (pintype "passive"))
      (node (ref "C105") (pin "2") (pinfunction "2_2") (pintype "passive"))
      (node (ref "C106") (pin "2") (pinfunction "2_2") (pintype "passive"))
      (node (ref "C14") (pin "-") (pinfunction "2_-") (pintype "passive"))
      (node (ref "C15") (pin "-") (pinfunction "2_-") (pintype "passive"))
      (node (ref "C16") (pin "2") (pinfunction "2_2") (pintype "passive"))
      (node (ref "C17") (pin "-") (pinfunction "2_-") (pintype "passive"))
      (node (ref "C19") (pin "-") (pinfunction "2_-") (pintype "passive"))
      (node (ref "C2") (pin "2") (pinfunction "2_2") (pintype "passive"))
      (node (ref "C22") (pin "2") (pinfunction "2_2") (pintype "passive"))
      (node (ref "C23") (pin "2") (pinfunction "2_2") (pintype "passive"))
      (node (ref "C24") (pin "-") (pinfunction "2_-") (pintype "passive"))
      (node (ref "C25") (pin "2") (pinfunction "2_2") (pintype "passive"))
      (node (ref "C26") (pin "2") (pinfunction "2_2") (pintype "passive"))
      (node (ref "C27") (pin "2") (pinfunction "2_2") (pintype "passive"))
      (node (ref "C28") (pin "2") (pinfunction "2_2") (pintype "passive"))
      (node (ref "C29") (pin "2") (pinfunction "2_2") (pintype "passive"))
      (node (ref "C3") (pin "2") (pinfunction "2_2") (pintype "passive"))
      (node (ref "C30") (pin "2") (pinfunction "2_2") (pintype "passive"))
      (node (ref "C31") (pin "2") (pinfunction "2_2") (pintype "passive"))
      (node (ref "C32") (pin "2") (pinfunction "2_2") (pintype "passive"))
      (node (ref "C33") (pin "2") (pinfunction "2_2") (pintype "passive"))
      (node (ref "C34") (pin "-") (pinfunction "2_-") (pintype "passive"))
      (node (ref "C35") (pin "2") (pinfunction "2_2") (pintype "passive"))
      (node (ref "C36") (pin "2") (pinfunction "2_2") (pintype "passive"))
      (node (ref "C37") (pin "2") (pinfunction "2_2") (pintype "passive"))
      (node (ref "C39") (pin "2") (pinfunction "2_2") (pintype "passive"))
      (node (ref "C4") (pin "2") (pinfunction "2_2") (pintype "passive"))
      (node (ref "C40") (pin "2") (pinfunction "2_2") (pintype "passive"))
      (node (ref "C41") (pin "2") (pinfunction "2_2") (pintype "passive"))
      (node (ref "C42") (pin "2") (pinfunction "2_2") (pintype "passive"))
      (node (ref "C43") (pin "2") (pinfunction "2_2") (pintype "passive"))
      (node (ref "C44") (pin "2") (pinfunction "2_2") (pintype "passive"))
      (node (ref "C45") (pin "2") (pinfunction "2_2") (pintype "passive"))
      (node (ref "C46") (pin "2") (pinfunction "2_2") (pintype "passive"))
      (node (ref "C47") (pin "2") (pinfunction "2_2") (pintype "passive"))
      (node (ref "C48") (pin "2") (pinfunction "2_2") (pintype "passive"))
      (node (ref "C49") (pin "2") (pinfunction "2_2") (pintype "passive"))
      (node (ref "C5") (pin "2") (pinfunction "2_2") (pintype "passive"))
      (node (ref "C50") (pin "2") (pinfunction "2_2") (pintype "passive"))
      (node (ref "C51") (pin "2") (pinfunction "2_2") (pintype "passive"))
      (node (ref "C52") (pin "2") (pinfunction "2_2") (pintype "passive"))
      (node (ref "C53") (pin "2") (pinfunction "2_2") (pintype "passive"))
      (node (ref "C54") (pin "2") (pinfunction "2_2") (pintype "passive"))
      (node (ref "C55") (pin "2") (pinfunction "2_2") (pintype "passive"))
      (node (ref "C56") (pin "2") (pinfunction "2_2") (pintype "passive"))
      (node (ref "C57") (pin "-") (pinfunction "2_-") (pintype "passive"))
      (node (ref "C58") (pin "2") (pinfunction "2_2") (pintype "passive"))
      (node (ref "C59") (pin "2") (pinfunction "2_2") (pintype "passive"))
      (node (ref "C6") (pin "2") (pinfunction "2_2") (pintype "passive"))
      (node (ref "C60") (pin "2") (pinfunction "2_2") (pintype "passive"))
      (node (ref "C61") (pin "2") (pinfunction "2_2") (pintype "passive"))
      (node (ref "C62") (pin "-") (pinfunction "2_-") (pintype "passive"))
      (node (ref "C63") (pin "2") (pinfunction "2_2") (pintype "passive"))
      (node (ref "C64") (pin "-") (pinfunction "2_-") (pintype "passive"))
      (node (ref "C65") (pin "-") (pinfunction "2_-") (pintype "passive"))
      (node (ref "C66") (pin "2") (pinfunction "2_2") (pintype "passive"))
      (node (ref "C67") (pin "2") (pinfunction "2_2") (pintype "passive"))
      (node (ref "C68") (pin "2") (pinfunction "2_2") (pintype "passive"))
      (node (ref "C7") (pin "2") (pinfunction "2_2") (pintype "passive"))
      (node (ref "C71") (pin "2") (pinfunction "2_2") (pintype "passive"))
      (node (ref "C72") (pin "2") (pinfunction "2_2") (pintype "passive"))
      (node (ref "C73") (pin "2") (pinfunction "2_2") (pintype "passive"))
      (node (ref "C74") (pin "2") (pinfunction "2_2") (pintype "passive"))
      (node (ref "C76") (pin "2") (pinfunction "2_2") (pintype "passive"))
      (node (ref "C77") (pin "2") (pinfunction "2_2") (pintype "passive"))
      (node (ref "C78") (pin "2") (pinfunction "2_2") (pintype "passive"))
      (node (ref "C8") (pin "-") (pinfunction "2_-") (pintype "passive"))
      (node (ref "C80") (pin "2") (pinfunction "2_2") (pintype "passive"))
      (node (ref "C82") (pin "2") (pinfunction "2_2") (pintype "passive"))
      (node (ref "C83") (pin "1") (pinfunction "1_1") (pintype "passive"))
      (node (ref "C84") (pin "2") (pinfunction "2_2") (pintype "passive"))
      (node (ref "C87") (pin "2") (pinfunction "2_2") (pintype "passive"))
      (node (ref "C88") (pin "-") (pinfunction "2_-") (pintype "passive"))
      (node (ref "C89") (pin "2") (pinfunction "2_2") (pintype "passive"))
      (node (ref "C9") (pin "2") (pinfunction "2_2") (pintype "passive"))
      (node (ref "C91") (pin "-") (pinfunction "2_-") (pintype "passive"))
      (node (ref "C92") (pin "2") (pinfunction "2_2") (pintype "passive"))
      (node (ref "C93") (pin "2") (pinfunction "2_2") (pintype "passive"))
      (node (ref "C94") (pin "-") (pinfunction "2_-") (pintype "passive"))
      (node (ref "C95") (pin "2") (pinfunction "2_2") (pintype "passive"))
      (node (ref "C96") (pin "2") (pinfunction "2_2") (pintype "passive"))
      (node (ref "C97") (pin "2") (pinfunction "2_2") (pintype "passive"))
      (node (ref "C98") (pin "2") (pinfunction "2_2") (pintype "passive"))
      (node (ref "C99") (pin "2") (pinfunction "2_2") (pintype "passive"))
      (node (ref "CN1") (pin "1") (pinfunction "1_1") (pintype "passive"))
      (node (ref "CN2") (pin "1") (pinfunction "GND3_1") (pintype "passive"))
      (node (ref "CN2") (pin "12") (pinfunction "GND1_12") (pintype "passive"))
      (node (ref "CN2") (pin "A") (pinfunction "GND4_A") (pintype "passive"))
      (node (ref "CN2") (pin "N") (pinfunction "GND2_N") (pintype "passive"))
      (node (ref "CN3") (pin "1") (pinfunction "GND1_1") (pintype "passive"))
      (node (ref "CN3") (pin "A") (pinfunction "GND2_A") (pintype "passive"))
      (node (ref "CN4") (pin "2") (pinfunction "2_2") (pintype "passive"))
      (node (ref "CN4") (pin "PE") (pinfunction "2_PE") (pintype "passive"))
      (node (ref "CN4") (pin "PE@") (pinfunction "2_PE@") (pintype "passive"))
      (node (ref "CN5") (pin "2") (pinfunction "2_2") (pintype "passive"))
      (node (ref "CN5") (pin "PE") (pinfunction "2_PE") (pintype "passive"))
      (node (ref "CN5") (pin "PE@") (pinfunction "2_PE@") (pintype "passive"))
      (node (ref "CN6") (pin "1") (pinfunction "GND1_1") (pintype "passive"))
      (node (ref "CN6") (pin "22") (pinfunction "GND3_22") (pintype "passive"))
      (node (ref "CN6") (pin "A") (pinfunction "GND2_A") (pintype "passive"))
      (node (ref "CN6") (pin "Z") (pinfunction "GND4_Z") (pintype "passive"))
      (node (ref "CN7") (pin "1") (pinfunction "1_1") (pintype "passive"))
      (node (ref "CN7") (pin "2") (pinfunction "2_2") (pintype "passive"))
      (node (ref "CN7") (pin "3") (pinfunction "3_3") (pintype "passive"))
      (node (ref "CN7") (pin "PE") (pinfunction "PE_PE") (pintype "power_in"))
      (node (ref "CN7") (pin "PE@") (pinfunction "PE_PE@") (pintype "power_in"))
      (node (ref "CN8") (pin "8") (pinfunction "8_8") (pintype "passive"))
      (node (ref "CN9") (pin "8") (pinfunction "8_8") (pintype "passive"))
      (node (ref "CR1") (pin "1") (pinfunction "A_1") (pintype "passive"))
      (node (ref "CR2") (pin "1") (pinfunction "A_1") (pintype "passive"))
      (node (ref "CR4") (pin "2") (pinfunction "-_2") (pintype "passive"))
      (node (ref "FB20") (pin "1") (pinfunction "1_1") (pintype "passive"))
      (node (ref "JP1") (pin "2") (pinfunction "2_2") (pintype "passive"))
      (node (ref "Q2") (pin "1") (pinfunction "E_1") (pintype "passive"))
      (node (ref "Q6") (pin "3") (pinfunction "E_3") (pintype "passive"))
      (node (ref "R11") (pin "1") (pinfunction "1_1") (pintype "passive"))
      (node (ref "R14") (pin "2") (pinfunction "2_2") (pintype "passive"))
      (node (ref "R15") (pin "2") (pinfunction "2_2") (pintype "passive"))
      (node (ref "R21") (pin "2") (pinfunction "2_2") (pintype "passive"))
      (node (ref "R22") (pin "2") (pinfunction "2_2") (pintype "passive"))
      (node (ref "R25") (pin "A") (pinfunction "A_A") (pintype "passive"))
      (node (ref "R27") (pin "A") (pinfunction "A_A") (pintype "passive"))
      (node (ref "R3") (pin "2") (pinfunction "2_2") (pintype "passive"))
      (node (ref "R35") (pin "2") (pinfunction "2_2") (pintype "passive"))
      (node (ref "R38") (pin "2") (pinfunction "2_2") (pintype "passive"))
      (node (ref "R49") (pin "2") (pinfunction "2_2") (pintype "passive"))
      (node (ref "R6") (pin "2") (pinfunction "2_2") (pintype "passive"))
      (node (ref "RF1") (pin "CASE") (pinfunction "GND_CASE") (pintype "power_in"))
      (node (ref "RF1") (pin "P$1") (pinfunction "GND_P$1") (pintype "power_in"))
      (node (ref "RF1") (pin "P$2") (pinfunction "GND_P$2") (pintype "power_in"))
      (node (ref "RF1") (pin "P$3") (pinfunction "GND_P$3") (pintype "power_in"))
      (node (ref "RF1") (pin "P$4") (pinfunction "GND_P$4") (pintype "power_in"))
      (node (ref "RF1") (pin "P$5") (pinfunction "GND_P$5") (pintype "power_in"))
      (node (ref "RF1") (pin "P$6") (pinfunction "GND_P$6") (pintype "power_in"))
      (node (ref "RF1") (pin "P$7") (pinfunction "GND_P$7") (pintype "power_in"))
      (node (ref "RF1") (pin "P$8") (pinfunction "GND_P$8") (pintype "power_in"))
      (node (ref "U1") (pin "20") (pinfunction "GND_20") (pintype "power_in"))
      (node (ref "U10") (pin "16") (pinfunction "GND_16") (pintype "power_in"))
      (node (ref "U11") (pin "16") (pinfunction "GND_16") (pintype "power_in"))
      (node (ref "U12") (pin "16") (pinfunction "GND_16") (pintype "power_in"))
      (node (ref "U13") (pin "8") (pinfunction "GND_8") (pintype "power_in"))
      (node (ref "U14") (pin "8") (pinfunction "GND_8") (pintype "power_in"))
      (node (ref "U15") (pin "8") (pinfunction "GND_8") (pintype "power_in"))
      (node (ref "U16") (pin "7") (pinfunction "GND_7") (pintype "power_in"))
      (node (ref "U17") (pin "14") (pinfunction "GND_14") (pintype "power_in"))
      (node (ref "U17") (pin "19") (pinfunction "OE_19") (pintype "input"))
      (node (ref "U18") (pin "14") (pinfunction "GND_14") (pintype "power_in"))
      (node (ref "U19") (pin "20") (pinfunction "GND_20") (pintype "power_in"))
      (node (ref "U2") (pin "20") (pinfunction "GND_20") (pintype "power_in"))
      (node (ref "U20") (pin "7") (pinfunction "GND_7") (pintype "power_in"))
      (node (ref "U21") (pin "16") (pinfunction "GND_16") (pintype "power_in"))
      (node (ref "U22") (pin "16") (pinfunction "GND_16") (pintype "power_in"))
      (node (ref "U23") (pin "16") (pinfunction "GND_16") (pintype "power_in"))
      (node (ref "U24") (pin "16") (pinfunction "GND_16") (pintype "power_in"))
      (node (ref "U25") (pin "8") (pinfunction "GND_8") (pintype "power_in"))
      (node (ref "U26") (pin "10") (pinfunction "GND_10") (pintype "power_in"))
      (node (ref "U27") (pin "7") (pinfunction "GND_7") (pintype "power_in"))
      (node (ref "U28") (pin "7") (pinfunction "GND_7") (pintype "power_in"))
      (node (ref "U29") (pin "1") (pinfunction "CLR_1") (pintype "input"))
      (node (ref "U29") (pin "2") (pinfunction "D_2") (pintype "input"))
      (node (ref "U29") (pin "3") (pinfunction "CLK_3") (pintype "input"))
      (node (ref "U29") (pin "7") (pinfunction "GND_7") (pintype "power_in"))
      (node (ref "U3") (pin "12") (pinfunction "GND_12") (pintype "power_in"))
      (node (ref "U30") (pin "14") (pinfunction "CLK_14") (pintype "input"))
      (node (ref "U30") (pin "8") (pinfunction "GND_8") (pintype "power_in"))
      (node (ref "U31") (pin "11") (pinfunction "EN1_11") (pintype "input"))
      (node (ref "U31") (pin "6") (pinfunction "EN2_6") (pintype "input"))
      (node (ref "U31") (pin "8") (pinfunction "GND_8") (pintype "power_in"))
      (node (ref "U31") (pin "9") (pinfunction "I2_9") (pintype "input"))
      (node (ref "U32") (pin "7") (pinfunction "GND_7") (pintype "power_in"))
      (node (ref "U4") (pin "12") (pinfunction "GND_12") (pintype "power_in"))
      (node (ref "U5") (pin "12") (pinfunction "GND_12") (pintype "power_in"))
      (node (ref "U6") (pin "9") (pinfunction "GND_9") (pintype "power_in"))
      (node (ref "U7") (pin "21") (pinfunction "GND_21") (pintype "power_in"))
      (node (ref "U8") (pin "7") (pinfunction "GND_7") (pintype "power_in"))
      (node (ref "U9") (pin "16") (pinfunction "GND_16") (pintype "power_in"))
      (node (ref "VR1") (pin "2") (pinfunction "GND_2") (pintype "passive"))
      (node (ref "VR2") (pin "2") (pinfunction "GND_2") (pintype "passive"))
      (node (ref "Y1") (pin "3") (pinfunction "3_3") (pintype "passive"))
    )
    (net (code "47") (name "Net-(C12-1)") (class "Default")
      (node (ref "C12") (pin "+") (pinfunction "1_+") (pintype "passive"))
      (node (ref "C35") (pin "1") (pinfunction "1_1") (pintype "passive"))
      (node (ref "U18") (pin "26") (pinfunction "EXT-IN_26") (pintype "input"))
    )
    (net (code "48") (name "Net-(C12-2)") (class "Default")
      (node (ref "C12") (pin "-") (pinfunction "2_-") (pintype "passive"))
      (node (ref "CN5") (pin "5") (pinfunction "5_5") (pintype "passive"))
    )
    (net (code "49") (name "Net-(C13-1)") (class "Default")
      (node (ref "C13") (pin "+") (pinfunction "1_+") (pintype "passive"))
      (node (ref "Q8") (pin "3") (pinfunction "E_3") (pintype "passive"))
      (node (ref "R38") (pin "1") (pinfunction "1_1") (pintype "passive"))
    )
    (net (code "50") (name "Net-(C13-2)") (class "Default")
      (node (ref "C13") (pin "-") (pinfunction "2_-") (pintype "passive"))
      (node (ref "CN5") (pin "3") (pinfunction "3_3") (pintype "passive"))
      (node (ref "RF1") (pin "AUDIO") (pinfunction "AUDIO_AUDIO") (pintype "input"))
    )
    (net (code "51") (name "Net-(C19-1)") (class "Default")
      (node (ref "C19") (pin "+") (pinfunction "1_+") (pintype "passive"))
      (node (ref "C95") (pin "1") (pinfunction "1_1") (pintype "passive"))
      (node (ref "CR4") (pin "1") (pinfunction "+_1") (pintype "passive"))
      (node (ref "VR2") (pin "1") (pinfunction "VI_1") (pintype "input"))
    )
    (net (code "52") (name "Net-(C20-Pad1)") (class "Default")
      (node (ref "C20") (pin "1") (pinfunction "1_1") (pintype "passive"))
      (node (ref "CN7") (pin "6") (pinfunction "6_6") (pintype "passive"))
      (node (ref "L4") (pin "3") (pinfunction "3_3") (pintype "passive"))
    )
    (net (code "53") (name "Net-(C20-Pad2)") (class "Default")
      (node (ref "C20") (pin "2") (pinfunction "2_2") (pintype "passive"))
      (node (ref "CN7") (pin "7") (pinfunction "7_7") (pintype "passive"))
      (node (ref "L4") (pin "4") (pinfunction "4_4") (pintype "passive"))
    )
    (net (code "54") (name "Net-(C21-Pad1)") (class "Default")
      (node (ref "C21") (pin "1") (pinfunction "1_1") (pintype "passive"))
      (node (ref "C99") (pin "1") (pinfunction "1_1") (pintype "passive"))
      (node (ref "F1") (pin "1A") (pinfunction "1A_1A") (pintype "passive"))
      (node (ref "L4") (pin "2") (pinfunction "2_2") (pintype "passive"))
    )
    (net (code "55") (name "Net-(C24-1)") (class "Default")
      (node (ref "C24") (pin "+") (pinfunction "1_+") (pintype "passive"))
      (node (ref "R34") (pin "2") (pinfunction "2_2") (pintype "passive"))
      (node (ref "U20") (pin "12") (pinfunction "THR_12") (pintype "input"))
      (node (ref "U20") (pin "13") (pinfunction "DIS_13") (pintype "input"))
    )
    (net (code "56") (name "Net-(C38-Pad1)") (class "Default")
      (node (ref "C38") (pin "1") (pinfunction "1_1") (pintype "passive"))
      (node (ref "CN1") (pin "3") (pinfunction "3_3") (pintype "passive"))
      (node (ref "R41") (pin "2") (pinfunction "2_2") (pintype "passive"))
    )
    (net (code "57") (name "Net-(C70-Pad1)") (class "Default")
      (node (ref "C70") (pin "1") (pinfunction "1_1") (pintype "passive"))
      (node (ref "Y1") (pin "1") (pinfunction "1_1") (pintype "passive"))
    )
    (net (code "58") (name "Net-(C72-Pad1)") (class "Default")
      (node (ref "C72") (pin "1") (pinfunction "1_1") (pintype "passive"))
      (node (ref "CN5") (pin "1") (pinfunction "1_1") (pintype "passive"))
      (node (ref "R9") (pin "2") (pinfunction "2_2") (pintype "passive"))
    )
    (net (code "59") (name "Net-(C78-Pad1)") (class "Default")
      (node (ref "C78") (pin "1") (pinfunction "1_1") (pintype "passive"))
      (node (ref "CN5") (pin "4") (pinfunction "4_4") (pintype "passive"))
      (node (ref "L3") (pin "2") (pinfunction "2_2") (pintype "passive"))
    )
    (net (code "60") (name "Net-(C79-Pad1)") (class "Default")
      (node (ref "C79") (pin "1") (pinfunction "1_1") (pintype "passive"))
      (node (ref "L3") (pin "1") (pinfunction "1_1") (pintype "passive"))
      (node (ref "R10") (pin "2") (pinfunction "2_2") (pintype "passive"))
      (node (ref "R11") (pin "2") (pinfunction "2_2") (pintype "passive"))
      (node (ref "R18") (pin "1") (pinfunction "1_1") (pintype "passive"))
      (node (ref "R48") (pin "2") (pinfunction "2_2") (pintype "passive"))
    )
    (net (code "61") (name "Net-(C80-Pad1)") (class "Default")
      (node (ref "C80") (pin "1") (pinfunction "1_1") (pintype "passive"))
      (node (ref "FB14") (pin "1") (pinfunction "1_1") (pintype "passive"))
      (node (ref "R25") (pin "E") (pinfunction "E_E") (pintype "passive"))
    )
    (net (code "62") (name "Net-(C81-Pad1)") (class "Default")
      (node (ref "C81") (pin "1") (pinfunction "1_1") (pintype "passive"))
      (node (ref "R24") (pin "2") (pinfunction "2_2") (pintype "passive"))
    )
    (net (code "63") (name "Net-(C85-Pad1)") (class "Default")
      (node (ref "C85") (pin "1") (pinfunction "1_1") (pintype "passive"))
      (node (ref "R17") (pin "2") (pinfunction "2_2") (pintype "passive"))
    )
    (net (code "64") (name "Net-(C88-1)") (class "Default")
      (node (ref "C88") (pin "+") (pinfunction "1_+") (pintype "passive"))
      (node (ref "C89") (pin "1") (pinfunction "1_1") (pintype "passive"))
      (node (ref "CR5") (pin "2") (pinfunction "C_2") (pintype "passive"))
      (node (ref "VR1") (pin "1") (pinfunction "VI_1") (pintype "input"))
    )
    (net (code "65") (name "Net-(C90-1)") (class "Default")
      (node (ref "C90") (pin "+") (pinfunction "1_+") (pintype "passive"))
      (node (ref "CR5") (pin "1") (pinfunction "A_1") (pintype "passive"))
      (node (ref "CR6") (pin "1") (pinfunction "A_1") (pintype "passive"))
    )
    (net (code "66") (name "Net-(C90-2)") (class "Default")
      (node (ref "C90") (pin "-") (pinfunction "2_-") (pintype "passive"))
      (node (ref "CN2") (pin "3") (pinfunction "9VAC1_3") (pintype "input"))
      (node (ref "CR4") (pin "4") (pinfunction "AC2_4") (pintype "passive"))
      (node (ref "R5") (pin "1") (pinfunction "1_1") (pintype "passive"))
      (node (ref "SW1") (pin "1") (pinfunction "S_1") (pintype "passive"))
    )
    (net (code "67") (name "Net-(C97-Pad1)") (class "Default")
      (node (ref "C97") (pin "1") (pinfunction "1_1") (pintype "passive"))
      (node (ref "CN7") (pin "5") (pinfunction "5_5") (pintype "passive"))
      (node (ref "L5") (pin "1") (pinfunction "1_1") (pintype "passive"))
    )
    (net (code "68") (name "Net-(CN2-9VAC2)") (class "Default")
      (node (ref "CN2") (pin "2") (pinfunction "9VAC2_2") (pintype "input"))
      (node (ref "CR4") (pin "3") (pinfunction "AC1_3") (pintype "passive"))
      (node (ref "F1") (pin "2A") (pinfunction "2A_2A") (pintype "passive"))
    )
    (net (code "69") (name "Net-(CN2-ATN)") (class "Default")
      (node (ref "CN2") (pin "4") (pinfunction "ATN_4") (pintype "bidirectional"))
      (node (ref "FB7") (pin "1") (pinfunction "1_1") (pintype "passive"))
      (node (ref "R28") (pin "2") (pinfunction "2_2") (pintype "passive"))
      (node (ref "U8") (pin "2") (pinfunction "O_2") (pintype "open_collector"))
    )
    (net (code "70") (name "Net-(CN2-CNT1)") (class "Default")
      (node (ref "CN2") (pin "9") (pinfunction "CNT1_9") (pintype "bidirectional"))
      (node (ref "RP3") (pin "5") (pinfunction "X_5") (pintype "passive"))
      (node (ref "U1") (pin "40") (pinfunction "CNT_40") (pintype "input"))
    )
    (net (code "71") (name "Net-(CN2-CNT2)") (class "Default")
      (node (ref "CN2") (pin "7") (pinfunction "CNT2_7") (pintype "bidirectional"))
      (node (ref "RP3") (pin "7") (pinfunction "X_7") (pintype "passive"))
      (node (ref "U2") (pin "40") (pinfunction "CNT_40") (pintype "input"))
    )
    (net (code "72") (name "Net-(CN2-FLAG2)") (class "Default")
      (node (ref "CN2") (pin "M") (pinfunction "FLAG2_M") (pintype "input"))
      (node (ref "RP3") (pin "2") (pinfunction "2_2") (pintype "passive"))
      (node (ref "U2") (pin "24") (pinfunction "~{FLAG}_24") (pintype "input"))
    )
    (net (code "73") (name "Net-(CN2-PA2)") (class "Default")
      (node (ref "CN2") (pin "B") (pinfunction "PA2_B") (pintype "bidirectional"))
      (node (ref "U2") (pin "4") (pinfunction "PA2_4") (pintype "bidirectional"))
    )
    (net (code "74") (name "Net-(CN2-PB0)") (class "Default")
      (node (ref "CN2") (pin "L") (pinfunction "PB0_L") (pintype "bidirectional"))
      (node (ref "U2") (pin "10") (pinfunction "PB0_10") (pintype "bidirectional"))
    )
    (net (code "75") (name "Net-(CN2-PB1)") (class "Default")
      (node (ref "CN2") (pin "K") (pinfunction "PB1_K") (pintype "bidirectional"))
      (node (ref "U2") (pin "11") (pinfunction "PB1_11") (pintype "bidirectional"))
    )
    (net (code "76") (name "Net-(CN2-PB2)") (class "Default")
      (node (ref "CN2") (pin "J") (pinfunction "PB2_J") (pintype "bidirectional"))
      (node (ref "U2") (pin "12") (pinfunction "PB2_12") (pintype "bidirectional"))
    )
    (net (code "77") (name "Net-(CN2-PB3)") (class "Default")
      (node (ref "CN2") (pin "H") (pinfunction "PB3_H") (pintype "bidirectional"))
      (node (ref "U2") (pin "13") (pinfunction "PB3_13") (pintype "bidirectional"))
    )
    (net (code "78") (name "Net-(CN2-PB4)") (class "Default")
      (node (ref "CN2") (pin "F") (pinfunction "PB4_F") (pintype "bidirectional"))
      (node (ref "U2") (pin "14") (pinfunction "PB4_14") (pintype "bidirectional"))
    )
    (net (code "79") (name "Net-(CN2-PB5)") (class "Default")
      (node (ref "CN2") (pin "E") (pinfunction "PB5_E") (pintype "bidirectional"))
      (node (ref "U2") (pin "15") (pinfunction "PB5_15") (pintype "bidirectional"))
    )
    (net (code "80") (name "Net-(CN2-PB6)") (class "Default")
      (node (ref "CN2") (pin "D") (pinfunction "PB6_D") (pintype "bidirectional"))
      (node (ref "U2") (pin "16") (pinfunction "PB6_16") (pintype "bidirectional"))
    )
    (net (code "81") (name "Net-(CN2-PB7)") (class "Default")
      (node (ref "CN2") (pin "C") (pinfunction "PB7_C") (pintype "bidirectional"))
      (node (ref "U2") (pin "17") (pinfunction "PB7_17") (pintype "bidirectional"))
    )
    (net (code "82") (name "Net-(CN2-PC2)") (class "Default")
      (node (ref "CN2") (pin "5") (pinfunction "PC2_5") (pintype "bidirectional"))
      (node (ref "U2") (pin "18") (pinfunction "~{PC}_18") (pintype "bidirectional"))
    )
    (net (code "83") (name "Net-(CN2-RESET)") (class "Default")
      (node (ref "CN2") (pin "10") (pinfunction "RESET_10") (pintype "bidirectional"))
      (node (ref "CN4") (pin "6") (pinfunction "6_6") (pintype "passive"))
      (node (ref "R36") (pin "2") (pinfunction "2_2") (pintype "passive"))
      (node (ref "U1") (pin "34") (pinfunction "~{RES}_34") (pintype "input"))
      (node (ref "U2") (pin "34") (pinfunction "~{RES}_34") (pintype "input"))
      (node (ref "U7") (pin "40") (pinfunction "~{RES}_40") (pintype "input"))
      (node (ref "U8") (pin "12") (pinfunction "O_12") (pintype "open_collector"))
    )
    (net (code "84") (name "Net-(CN2-SP1)") (class "Default")
      (node (ref "CN2") (pin "8") (pinfunction "SP1_8") (pintype "bidirectional"))
      (node (ref "RP3") (pin "6") (pinfunction "X_6") (pintype "passive"))
      (node (ref "U1") (pin "39") (pinfunction "SP_39") (pintype "bidirectional"))
    )
    (net (code "85") (name "Net-(CN2-SP2)") (class "Default")
      (node (ref "CN2") (pin "6") (pinfunction "SP2_6") (pintype "bidirectional"))
      (node (ref "RP3") (pin "8") (pinfunction "X_8") (pintype "passive"))
      (node (ref "U2") (pin "39") (pinfunction "SP_39") (pintype "bidirectional"))
    )
    (net (code "86") (name "Net-(CN3-MOTOR1)") (class "Default")
      (node (ref "CN3") (pin "3") (pinfunction "MOTOR1_3") (pintype "input"))
      (node (ref "CN3") (pin "C") (pinfunction "MOTOR2_C") (pintype "input"))
      (node (ref "FB2") (pin "2") (pinfunction "2_2") (pintype "passive"))
    )
    (net (code "87") (name "Net-(CN3-READ1)") (class "Default")
      (node (ref "CN3") (pin "4") (pinfunction "READ1_4") (pintype "output"))
      (node (ref "CN3") (pin "D") (pinfunction "READ2_D") (pintype "passive"))
      (node (ref "CN4") (pin "1") (pinfunction "1_1") (pintype "passive"))
      (node (ref "RP3") (pin "4") (pinfunction "X_4") (pintype "passive"))
      (node (ref "U1") (pin "24") (pinfunction "~{FLAG}_24") (pintype "input"))
    )
    (net (code "88") (name "Net-(CN3-SENSE1)") (class "Default")
      (node (ref "CN3") (pin "6") (pinfunction "SENSE1_6") (pintype "output"))
      (node (ref "CN3") (pin "F") (pinfunction "SENSE2_F") (pintype "passive"))
      (node (ref "R1") (pin "2") (pinfunction "2_2") (pintype "passive"))
      (node (ref "U7") (pin "25") (pinfunction "P4_25") (pintype "bidirectional"))
    )
    (net (code "89") (name "Net-(CN3-VCC1)") (class "Default")
      (node (ref "C1") (pin "1") (pinfunction "1_1") (pintype "passive"))
      (node (ref "CN3") (pin "2") (pinfunction "VCC1_2") (pintype "passive"))
      (node (ref "CN3") (pin "B") (pinfunction "VCC2_B") (pintype "passive"))
      (node (ref "FB3") (pin "2") (pinfunction "2_2") (pintype "passive"))
    )
    (net (code "90") (name "Net-(CN3-WRITE1)") (class "Default")
      (node (ref "CN3") (pin "5") (pinfunction "WRITE1_5") (pintype "input"))
      (node (ref "CN3") (pin "E") (pinfunction "WRITE2_E") (pintype "input"))
      (node (ref "FB1") (pin "2") (pinfunction "2_2") (pintype "passive"))
    )
    (net (code "91") (name "Net-(CN4-Pad3)") (class "Default")
      (node (ref "CN4") (pin "3") (pinfunction "3_3") (pintype "passive"))
      (node (ref "FB7") (pin "2") (pinfunction "2_2") (pintype "passive"))
    )
    (net (code "92") (name "Net-(CN4-Pad4)") (class "Default")
      (node (ref "CN4") (pin "4") (pinfunction "4_4") (pintype "passive"))
      (node (ref "FB9") (pin "2") (pinfunction "2_2") (pintype "passive"))
    )
    (net (code "93") (name "Net-(CN4-Pad5)") (class "Default")
      (node (ref "CN4") (pin "5") (pinfunction "5_5") (pintype "passive"))
      (node (ref "FB8") (pin "2") (pinfunction "2_2") (pintype "passive"))
    )
    (net (code "94") (name "Net-(CN6-BA)") (class "Default")
      (node (ref "CN6") (pin "12") (pinfunction "BA_12") (pintype "input"))
      (node (ref "RP4") (pin "2") (pinfunction "2_2") (pintype "passive"))
      (node (ref "U17") (pin "26") (pinfunction "BA_26") (pintype "input"))
      (node (ref "U19") (pin "12") (pinfunction "BA_12") (pintype "output"))
      (node (ref "U27") (pin "1") (pinfunction "I0_1") (pintype "input"))
    )
    (net (code "95") (name "Net-(CN6-DMA)") (class "Default")
      (node (ref "CN6") (pin "13") (pinfunction "DMA_13") (pintype "output"))
      (node (ref "RP4") (pin "10") (pinfunction "X_10") (pintype "passive"))
      (node (ref "U27") (pin "2") (pinfunction "I1_2") (pintype "input"))
      (node (ref "U27") (pin "5") (pinfunction "I1_5") (pintype "input"))
    )
    (net (code "96") (name "Net-(CN6-DOTCLK)") (class "Default")
      (node (ref "C36") (pin "1") (pinfunction "1_1") (pintype "passive"))
      (node (ref "CN6") (pin "6") (pinfunction "DOTCLK_6") (pintype "input"))
      (node (ref "FB17") (pin "1") (pinfunction "1_1") (pintype "passive"))
      (node (ref "U19") (pin "22") (pinfunction "DOTCLK_22") (pintype "input"))
    )
    (net (code "97") (name "Net-(CN6-EXROM)") (class "Default")
      (node (ref "CN6") (pin "9") (pinfunction "EXROM_9") (pintype "input"))
      (node (ref "RP4") (pin "8") (pinfunction "X_8") (pintype "passive"))
      (node (ref "U17") (pin "23") (pinfunction "EXROM_23") (pintype "input"))
    )
    (net (code "98") (name "Net-(CN6-GAME)") (class "Default")
      (node (ref "CN6") (pin "8") (pinfunction "GAME_8") (pintype "output"))
      (node (ref "RP4") (pin "6") (pinfunction "X_6") (pintype "passive"))
      (node (ref "U17") (pin "22") (pinfunction "GAME_22") (pintype "input"))
    )
    (net (code "99") (name "Net-(CN6-IO1)") (class "Default")
      (node (ref "CN6") (pin "7") (pinfunction "IO1_7") (pintype "passive"))
      (node (ref "U15") (pin "10") (pinfunction "Y2_10") (pintype "output"))
    )
    (net (code "100") (name "Net-(CN6-IO2)") (class "Default")
      (node (ref "CN6") (pin "10") (pinfunction "IO2_10") (pintype "bidirectional"))
      (node (ref "U15") (pin "9") (pinfunction "Y3_9") (pintype "output"))
    )
    (net (code "101") (name "Net-(CN6-IRQ)") (class "Default")
      (node (ref "CN6") (pin "4") (pinfunction "IRQ_4") (pintype "input"))
      (node (ref "U1") (pin "21") (pinfunction "~{IRQ}_21") (pintype "open_collector"))
      (node (ref "U19") (pin "8") (pinfunction "~{IRQ}_8") (pintype "open_collector"))
      (node (ref "U7") (pin "3") (pinfunction "~{IRQ}_3") (pintype "input"))
    )
    (net (code "102") (name "Net-(CN6-NMI)") (class "Default")
      (node (ref "CN6") (pin "D") (pinfunction "NMI_D") (pintype "input"))
      (node (ref "RP3") (pin "3") (pinfunction "X_3") (pintype "passive"))
      (node (ref "U2") (pin "21") (pinfunction "~{IRQ}_21") (pintype "open_collector"))
      (node (ref "U7") (pin "4") (pinfunction "~{NMI}_4") (pintype "input"))
      (node (ref "U8") (pin "6") (pinfunction "O_6") (pintype "open_collector"))
    )
    (net (code "103") (name "Net-(CN6-PHI2)") (class "Default")
      (node (ref "CN6") (pin "E") (pinfunction "PHI2_E") (pintype "output"))
      (node (ref "FB5") (pin "1") (pinfunction "1_1") (pintype "passive"))
      (node (ref "U1") (pin "25") (pinfunction "CLKOUT_25") (pintype "input"))
      (node (ref "U17") (pin "24") (pinfunction "R/W_24") (pintype "input"))
      (node (ref "U18") (pin "6") (pinfunction "CLKOUT_6") (pintype "input"))
      (node (ref "U2") (pin "25") (pinfunction "CLKOUT_25") (pintype "input"))
    )
    (net (code "104") (name "Net-(CN6-RESET)") (class "Default")
      (node (ref "CN6") (pin "C") (pinfunction "RESET_C") (pintype "input"))
      (node (ref "FB4") (pin "2") (pinfunction "2_2") (pintype "passive"))
    )
    (net (code "105") (name "Net-(CN6-ROMH)") (class "Default")
      (node (ref "CN6") (pin "B") (pinfunction "ROMH_B") (pintype "passive"))
      (node (ref "U17") (pin "10") (pinfunction "ROMH_10") (pintype "tri_state"))
    )
    (net (code "106") (name "Net-(CN6-ROML)") (class "Default")
      (node (ref "CN6") (pin "11") (pinfunction "ROML_11") (pintype "passive"))
      (node (ref "U17") (pin "11") (pinfunction "ROML_11") (pintype "tri_state"))
    )
    (net (code "107") (name "Net-(CN6-R{slash}W)") (class "Default")
      (node (ref "CN6") (pin "5") (pinfunction "R/W_5") (pintype "output"))
      (node (ref "R46") (pin "1") (pinfunction "1_1") (pintype "passive"))
      (node (ref "RP4") (pin "3") (pinfunction "X_3") (pintype "passive"))
      (node (ref "U1") (pin "22") (pinfunction "R/W_22") (pintype "input"))
      (node (ref "U10") (pin "3") (pinfunction "~{WE}_3") (pintype "input"))
      (node (ref "U11") (pin "3") (pinfunction "~{WE}_3") (pintype "input"))
      (node (ref "U12") (pin "3") (pinfunction "~{WE}_3") (pintype "input"))
      (node (ref "U18") (pin "7") (pinfunction "R/W_7") (pintype "input"))
      (node (ref "U19") (pin "11") (pinfunction "~{R/W}_11") (pintype "input"))
      (node (ref "U2") (pin "22") (pinfunction "R/W_22") (pintype "input"))
      (node (ref "U21") (pin "3") (pinfunction "~{WE}_3") (pintype "input"))
      (node (ref "U22") (pin "3") (pinfunction "~{WE}_3") (pintype "input"))
      (node (ref "U23") (pin "3") (pinfunction "~{WE}_3") (pintype "input"))
      (node (ref "U24") (pin "3") (pinfunction "~{WE}_3") (pintype "input"))
      (node (ref "U7") (pin "38") (pinfunction "R/W_38") (pintype "tri_state"))
      (node (ref "U9") (pin "3") (pinfunction "~{WE}_3") (pintype "input"))
    )
    (net (code "108") (name "Net-(CN8-Pad7)") (class "Default")
      (node (ref "CN8") (pin "7") (pinfunction "7_7") (pintype "passive"))
      (node (ref "CN9") (pin "7") (pinfunction "7_7") (pintype "passive"))
      (node (ref "FB18") (pin "2") (pinfunction "2_2") (pintype "passive"))
    )
    (net (code "109") (name "Net-(CN10-Pad1)") (class "Default")
      (node (ref "CN10") (pin "1") (pinfunction "1_1") (pintype "passive"))
      (node (ref "CN10") (pin "3") (pinfunction "3_3") (pintype "passive"))
      (node (ref "FB21") (pin "2") (pinfunction "2_2") (pintype "passive"))
    )
    (net (code "110") (name "Net-(CN10-Pad2)") (class "Default")
      (node (ref "CN10") (pin "2") (pinfunction "2_2") (pintype "passive"))
      (node (ref "FB20") (pin "2") (pinfunction "2_2") (pintype "passive"))
    )
    (net (code "111") (name "Net-(CR1-C)") (class "Default")
      (node (ref "CR1") (pin "2") (pinfunction "C_2") (pintype "passive"))
      (node (ref "R37") (pin "2") (pinfunction "2_2") (pintype "passive"))
      (node (ref "R5") (pin "2") (pinfunction "2_2") (pintype "passive"))
      (node (ref "U27") (pin "12") (pinfunction "I0_12") (pintype "input"))
    )
    (net (code "112") (name "Net-(CR2-C)") (class "Default")
      (node (ref "C18") (pin "2") (pinfunction "2_2") (pintype "passive"))
      (node (ref "CR2") (pin "2") (pinfunction "C_2") (pintype "passive"))
      (node (ref "Q1") (pin "1") (pinfunction "B_1") (pintype "passive"))
      (node (ref "Q2") (pin "3") (pinfunction "C_3") (pintype "passive"))
      (node (ref "R2") (pin "2") (pinfunction "2_2") (pintype "passive"))
    )
    (net (code "113") (name "Net-(CR3-A)") (class "Default")
      (node (ref "C73") (pin "1") (pinfunction "1_1") (pintype "passive"))
      (node (ref "CR3") (pin "1") (pinfunction "A_1") (pintype "passive"))
      (node (ref "Q4") (pin "2") (pinfunction "B_2") (pintype "passive"))
      (node (ref "R8") (pin "2") (pinfunction "2_2") (pintype "passive"))
    )
    (net (code "114") (name "Net-(CR3-C)") (class "Default")
      (node (ref "CR3") (pin "2") (pinfunction "C_2") (pintype "passive"))
      (node (ref "FB15") (pin "1") (pinfunction "1_1") (pintype "passive"))
    )
    (net (code "115") (name "Net-(FB13-Pad2)") (class "Default")
      (node (ref "FB13") (pin "2") (pinfunction "2_2") (pintype "passive"))
      (node (ref "R7") (pin "1") (pinfunction "1_1") (pintype "passive"))
    )
    (net (code "116") (name "Net-(FB21-Pad1)") (class "Default")
      (node (ref "FB21") (pin "1") (pinfunction "1_1") (pintype "passive"))
      (node (ref "R39") (pin "2") (pinfunction "2_2") (pintype "passive"))
    )
    (net (code "117") (name "Net-(Q1-E)") (class "Default")
      (node (ref "Q1") (pin "3") (pinfunction "E_3") (pintype "passive"))
      (node (ref "Q3") (pin "2") (pinfunction "B_2") (pintype "passive"))
    )
    (net (code "118") (name "Net-(Q2-B)") (class "Default")
      (node (ref "Q2") (pin "2") (pinfunction "B_2") (pintype "passive"))
      (node (ref "R3") (pin "1") (pinfunction "1_1") (pintype "passive"))
      (node (ref "R4") (pin "2") (pinfunction "2_2") (pintype "passive"))
    )
    (net (code "119") (name "Net-(Q3-E)") (class "Default")
      (node (ref "FB2") (pin "1") (pinfunction "1_1") (pintype "passive"))
      (node (ref "Q3") (pin "1") (pinfunction "E_1") (pintype "passive"))
    )
    (net (code "120") (name "Net-(Q4-E)") (class "Default")
      (node (ref "Q4") (pin "3") (pinfunction "E_3") (pintype "passive"))
      (node (ref "R10") (pin "1") (pinfunction "1_1") (pintype "passive"))
      (node (ref "R9") (pin "1") (pinfunction "1_1") (pintype "passive"))
    )
    (net (code "121") (name "Net-(Q5-B)") (class "Default")
      (node (ref "Q5") (pin "2") (pinfunction "B_2") (pintype "passive"))
      (node (ref "Q6") (pin "1") (pinfunction "C_1") (pintype "passive"))
      (node (ref "R13") (pin "2") (pinfunction "2_2") (pintype "passive"))
      (node (ref "R20") (pin "2") (pinfunction "2_2") (pintype "passive"))
    )
    (net (code "122") (name "Net-(Q5-E)") (class "Default")
      (node (ref "C79") (pin "2") (pinfunction "2_2") (pintype "passive"))
      (node (ref "Q5") (pin "3") (pinfunction "E_3") (pintype "passive"))
      (node (ref "R14") (pin "1") (pinfunction "1_1") (pintype "passive"))
    )
    (net (code "123") (name "Net-(Q6-B)") (class "Default")
      (node (ref "C81") (pin "2") (pinfunction "2_2") (pintype "passive"))
      (node (ref "Q6") (pin "2") (pinfunction "B_2") (pintype "passive"))
      (node (ref "R20") (pin "1") (pinfunction "1_1") (pintype "passive"))
      (node (ref "R21") (pin "1") (pinfunction "1_1") (pintype "passive"))
    )
    (net (code "124") (name "Net-(Q7-B)") (class "Default")
      (node (ref "C85") (pin "2") (pinfunction "2_2") (pintype "passive"))
      (node (ref "Q7") (pin "2") (pinfunction "B_2") (pintype "passive"))
      (node (ref "R19") (pin "1") (pinfunction "1_1") (pintype "passive"))
    )
    (net (code "125") (name "Net-(Q7-E)") (class "Default")
      (node (ref "Q7") (pin "3") (pinfunction "E_3") (pintype "passive"))
      (node (ref "U32") (pin "9") (pinfunction "BI_9") (pintype "input"))
    )
    (net (code "126") (name "Net-(Q8-B)") (class "Default")
      (node (ref "C37") (pin "1") (pinfunction "1_1") (pintype "passive"))
      (node (ref "Q8") (pin "2") (pinfunction "B_2") (pintype "passive"))
      (node (ref "R7") (pin "2") (pinfunction "2_2") (pintype "passive"))
    )
    (net (code "127") (name "Net-(R24-Pad1)") (class "Default")
      (node (ref "R24") (pin "1") (pinfunction "1_1") (pintype "passive"))
      (node (ref "R25") (pin "S") (pinfunction "S_S") (pintype "passive"))
    )
    (net (code "128") (name "Net-(R48-Pad1)") (class "Default")
      (node (ref "R48") (pin "1") (pinfunction "1_1") (pintype "passive"))
      (node (ref "R49") (pin "1") (pinfunction "1_1") (pintype "passive"))
      (node (ref "RF1") (pin "VIDEO") (pinfunction "VIDEO_VIDEO") (pintype "input"))
    )
    (net (code "129") (name "Net-(RF1-+V)") (class "Default")
      (node (ref "C16") (pin "1") (pinfunction "1_1") (pintype "passive"))
      (node (ref "FB6") (pin "1") (pinfunction "1_1") (pintype "passive"))
      (node (ref "RF1") (pin "+") (pinfunction "+V_+") (pintype "power_in"))
    )
    (net (code "130") (name "Net-(SW1A-P)") (class "Default")
      (node (ref "C21") (pin "2") (pinfunction "2_2") (pintype "passive"))
      (node (ref "C98") (pin "1") (pinfunction "1_1") (pintype "passive"))
      (node (ref "L4") (pin "1") (pinfunction "1_1") (pintype "passive"))
      (node (ref "SW1") (pin "2") (pinfunction "P_2") (pintype "passive"))
    )
    (net (code "131") (name "Net-(SW1B-P)") (class "Default")
      (node (ref "C100") (pin "1") (pinfunction "1_1") (pintype "passive"))
      (node (ref "L5") (pin "2") (pinfunction "2_2") (pintype "passive"))
      (node (ref "SW1") (pin "5") (pinfunction "P_5") (pintype "passive"))
    )
    (net (code "132") (name "Net-(U1A-PA0)") (class "Default")
      (node (ref "CN1") (pin "13") (pinfunction "13_13") (pintype "passive"))
      (node (ref "CN8") (pin "1") (pinfunction "1_1") (pintype "passive"))
      (node (ref "U1") (pin "2") (pinfunction "PA0_2") (pintype "bidirectional"))
    )
    (net (code "133") (name "Net-(U1A-PA1)") (class "Default")
      (node (ref "CN1") (pin "19") (pinfunction "19_19") (pintype "passive"))
      (node (ref "CN8") (pin "2") (pinfunction "2_2") (pintype "passive"))
      (node (ref "U1") (pin "3") (pinfunction "PA1_3") (pintype "bidirectional"))
    )
    (net (code "134") (name "Net-(U1A-PA2)") (class "Default")
      (node (ref "CN1") (pin "18") (pinfunction "18_18") (pintype "passive"))
      (node (ref "CN8") (pin "3") (pinfunction "3_3") (pintype "passive"))
      (node (ref "U1") (pin "4") (pinfunction "PA2_4") (pintype "bidirectional"))
    )
    (net (code "135") (name "Net-(U1A-PA3)") (class "Default")
      (node (ref "CN1") (pin "17") (pinfunction "17_17") (pintype "passive"))
      (node (ref "CN8") (pin "4") (pinfunction "4_4") (pintype "passive"))
      (node (ref "U1") (pin "5") (pinfunction "PA3_5") (pintype "bidirectional"))
    )
    (net (code "136") (name "Net-(U1A-PA4)") (class "Default")
      (node (ref "CN1") (pin "16") (pinfunction "16_16") (pintype "passive"))
      (node (ref "CN8") (pin "6") (pinfunction "6_6") (pintype "passive"))
      (node (ref "U1") (pin "6") (pinfunction "PA4_6") (pintype "bidirectional"))
    )
    (net (code "137") (name "Net-(U1A-PA5)") (class "Default")
      (node (ref "CN1") (pin "15") (pinfunction "15_15") (pintype "passive"))
      (node (ref "U1") (pin "7") (pinfunction "PA5_7") (pintype "bidirectional"))
    )
    (net (code "138") (name "Net-(U1A-PA6)") (class "Default")
      (node (ref "CN1") (pin "14") (pinfunction "14_14") (pintype "passive"))
      (node (ref "U1") (pin "8") (pinfunction "PA6_8") (pintype "bidirectional"))
      (node (ref "U28") (pin "12") (pinfunction "E3_12") (pintype "input"))
      (node (ref "U28") (pin "6") (pinfunction "E2_6") (pintype "input"))
    )
    (net (code "139") (name "Net-(U1A-PA7)") (class "Default")
      (node (ref "CN1") (pin "20") (pinfunction "20_20") (pintype "passive"))
      (node (ref "U1") (pin "9") (pinfunction "PA7_9") (pintype "bidirectional"))
      (node (ref "U28") (pin "13") (pinfunction "E0_13") (pintype "input"))
      (node (ref "U28") (pin "5") (pinfunction "E1_5") (pintype "input"))
    )
    (net (code "140") (name "Net-(U1A-PB0)") (class "Default")
      (node (ref "CN1") (pin "12") (pinfunction "12_12") (pintype "passive"))
      (node (ref "CN9") (pin "1") (pinfunction "1_1") (pintype "passive"))
      (node (ref "U1") (pin "10") (pinfunction "PB0_10") (pintype "bidirectional"))
    )
    (net (code "141") (name "Net-(U1A-PB1)") (class "Default")
      (node (ref "CN1") (pin "11") (pinfunction "11_11") (pintype "passive"))
      (node (ref "CN9") (pin "2") (pinfunction "2_2") (pintype "passive"))
      (node (ref "U1") (pin "11") (pinfunction "PB1_11") (pintype "bidirectional"))
    )
    (net (code "142") (name "Net-(U1A-PB2)") (class "Default")
      (node (ref "CN1") (pin "10") (pinfunction "10_10") (pintype "passive"))
      (node (ref "CN9") (pin "3") (pinfunction "3_3") (pintype "passive"))
      (node (ref "U1") (pin "12") (pinfunction "PB2_12") (pintype "bidirectional"))
    )
    (net (code "143") (name "Net-(U1A-PB3)") (class "Default")
      (node (ref "CN1") (pin "5") (pinfunction "5_5") (pintype "passive"))
      (node (ref "CN9") (pin "4") (pinfunction "4_4") (pintype "passive"))
      (node (ref "U1") (pin "13") (pinfunction "PB3_13") (pintype "bidirectional"))
    )
    (net (code "144") (name "Net-(U1A-PB5)") (class "Default")
      (node (ref "CN1") (pin "7") (pinfunction "7_7") (pintype "passive"))
      (node (ref "U1") (pin "15") (pinfunction "PB5_15") (pintype "bidirectional"))
    )
    (net (code "145") (name "Net-(U1A-PB6)") (class "Default")
      (node (ref "CN1") (pin "6") (pinfunction "6_6") (pintype "passive"))
      (node (ref "U1") (pin "16") (pinfunction "PB6_16") (pintype "bidirectional"))
    )
    (net (code "146") (name "Net-(U1A-PB7)") (class "Default")
      (node (ref "CN1") (pin "9") (pinfunction "9_9") (pintype "passive"))
      (node (ref "U1") (pin "17") (pinfunction "PB7_17") (pintype "bidirectional"))
    )
    (net (code "147") (name "Net-(U1A-TOD)") (class "Default")
      (node (ref "R37") (pin "1") (pinfunction "1_1") (pintype "passive"))
      (node (ref "U1") (pin "19") (pinfunction "TOD_19") (pintype "bidirectional"))
      (node (ref "U2") (pin "19") (pinfunction "TOD_19") (pintype "bidirectional"))
      (node (ref "U27") (pin "11") (pinfunction "O_11") (pintype "output"))
    )
    (net (code "148") (name "Net-(U2A-PA3)") (class "Default")
      (node (ref "U2") (pin "5") (pinfunction "PA3_5") (pintype "bidirectional"))
      (node (ref "U8") (pin "1") (pinfunction "I_1") (pintype "input"))
    )
    (net (code "149") (name "Net-(U2A-PA4)") (class "Default")
      (node (ref "U2") (pin "6") (pinfunction "PA4_6") (pintype "bidirectional"))
      (node (ref "U8") (pin "9") (pinfunction "I_9") (pintype "input"))
    )
    (net (code "150") (name "Net-(U2A-PA5)") (class "Default")
      (node (ref "U2") (pin "7") (pinfunction "PA5_7") (pintype "bidirectional"))
      (node (ref "U8") (pin "3") (pinfunction "I_3") (pintype "input"))
    )
    (net (code "151") (name "Net-(U2A-PA6)") (class "Default")
      (node (ref "FB9") (pin "1") (pinfunction "1_1") (pintype "passive"))
      (node (ref "R30") (pin "2") (pinfunction "2_2") (pintype "passive"))
      (node (ref "U2") (pin "8") (pinfunction "PA6_8") (pintype "bidirectional"))
      (node (ref "U8") (pin "8") (pinfunction "O_8") (pintype "open_collector"))
    )
    (net (code "152") (name "Net-(U2A-PA7)") (class "Default")
      (node (ref "FB8") (pin "1") (pinfunction "1_1") (pintype "passive"))
      (node (ref "R29") (pin "2") (pinfunction "2_2") (pintype "passive"))
      (node (ref "U2") (pin "9") (pinfunction "PA7_9") (pintype "bidirectional"))
      (node (ref "U8") (pin "4") (pinfunction "O_4") (pintype "open_collector"))
    )
    (net (code "153") (name "Net-(U7A-CLKOUT)") (class "Default")
      (node (ref "FB5") (pin "2") (pinfunction "2_2") (pintype "passive"))
      (node (ref "U7") (pin "39") (pinfunction "CLKOUT_39") (pintype "output"))
    )
    (net (code "154") (name "Net-(U7A-P3)") (class "Default")
      (node (ref "FB1") (pin "1") (pinfunction "1_1") (pintype "passive"))
      (node (ref "U7") (pin "26") (pinfunction "P3_26") (pintype "bidirectional"))
    )
    (net (code "155") (name "Net-(U7A-P5)") (class "Default")
      (node (ref "R4") (pin "1") (pinfunction "1_1") (pintype "passive"))
      (node (ref "U7") (pin "24") (pinfunction "P5_24") (pintype "bidirectional"))
    )
    (net (code "156") (name "Net-(U10A-~{CAS})") (class "Default")
      (node (ref "R42") (pin "1") (pinfunction "1_1") (pintype "passive"))
      (node (ref "U10") (pin "15") (pinfunction "~{CAS}_15") (pintype "input"))
      (node (ref "U11") (pin "15") (pinfunction "~{CAS}_15") (pintype "input"))
      (node (ref "U12") (pin "15") (pinfunction "~{CAS}_15") (pintype "input"))
      (node (ref "U21") (pin "15") (pinfunction "~{CAS}_15") (pintype "input"))
      (node (ref "U22") (pin "15") (pinfunction "~{CAS}_15") (pintype "input"))
      (node (ref "U23") (pin "15") (pinfunction "~{CAS}_15") (pintype "input"))
      (node (ref "U24") (pin "15") (pinfunction "~{CAS}_15") (pintype "input"))
      (node (ref "U9") (pin "15") (pinfunction "~{CAS}_15") (pintype "input"))
    )
    (net (code "157") (name "Net-(U10A-~{RAS})") (class "Default")
      (node (ref "U10") (pin "4") (pinfunction "~{RAS}_4") (pintype "input"))
      (node (ref "U11") (pin "4") (pinfunction "~{RAS}_4") (pintype "input"))
      (node (ref "U12") (pin "4") (pinfunction "~{RAS}_4") (pintype "input"))
      (node (ref "U19") (pin "18") (pinfunction "~{RAS}_18") (pintype "output"))
      (node (ref "U21") (pin "4") (pinfunction "~{RAS}_4") (pintype "input"))
      (node (ref "U22") (pin "4") (pinfunction "~{RAS}_4") (pintype "input"))
      (node (ref "U23") (pin "4") (pinfunction "~{RAS}_4") (pintype "input"))
      (node (ref "U24") (pin "4") (pinfunction "~{RAS}_4") (pintype "input"))
      (node (ref "U26") (pin "11") (pinfunction "ENC_11") (pintype "input"))
      (node (ref "U9") (pin "4") (pinfunction "~{RAS}_4") (pintype "input"))
    )
    (net (code "158") (name "Net-(U13A-G)") (class "Default")
      (node (ref "R31") (pin "2") (pinfunction "2_2") (pintype "passive"))
      (node (ref "U13") (pin "15") (pinfunction "G_15") (pintype "input"))
      (node (ref "U17") (pin "25") (pinfunction "AEC_25") (pintype "input"))
      (node (ref "U25") (pin "15") (pinfunction "G_15") (pintype "input"))
      (node (ref "U8") (pin "10") (pinfunction "O_10") (pintype "open_collector"))
    )
    (net (code "159") (name "Net-(U13A-~{A}{slash}B)") (class "Default")
      (node (ref "U13") (pin "1") (pinfunction "~{A}/B_1") (pintype "input"))
      (node (ref "U14") (pin "1") (pinfunction "~{A}/B_1") (pintype "input"))
      (node (ref "U17") (pin "9") (pinfunction "CAS_9") (pintype "input"))
      (node (ref "U19") (pin "19") (pinfunction "~{CAS}_19") (pintype "output"))
      (node (ref "U25") (pin "1") (pinfunction "~{A}/B_1") (pintype "input"))
    )
    (net (code "160") (name "Net-(U14A-1A)") (class "Default")
      (node (ref "U14") (pin "2") (pinfunction "1A_2") (pintype "input"))
      (node (ref "U17") (pin "5") (pinfunction "VIA14_5") (pintype "input"))
      (node (ref "U2") (pin "2") (pinfunction "PA0_2") (pintype "bidirectional"))
    )
    (net (code "161") (name "Net-(U14A-1B)") (class "Default")
      (node (ref "U14") (pin "3") (pinfunction "1B_3") (pintype "input"))
      (node (ref "U14") (pin "9") (pinfunction "3Y_9") (pintype "tri_state"))
    )
    (net (code "162") (name "Net-(U14A-2A)") (class "Default")
      (node (ref "U14") (pin "5") (pinfunction "2A_5") (pintype "input"))
      (node (ref "U2") (pin "3") (pinfunction "PA1_3") (pintype "bidirectional"))
    )
    (net (code "163") (name "Net-(U14A-2B)") (class "Default")
      (node (ref "U14") (pin "12") (pinfunction "4Y_12") (pintype "tri_state"))
      (node (ref "U14") (pin "6") (pinfunction "2B_6") (pintype "input"))
    )
    (net (code "164") (name "Net-(U14A-3A)") (class "Default")
      (node (ref "U14") (pin "10") (pinfunction "3B_10") (pintype "input"))
      (node (ref "U14") (pin "11") (pinfunction "3A_11") (pintype "input"))
      (node (ref "U19") (pin "31") (pinfunction "A7_31") (pintype "bidirectional"))
    )
    (net (code "165") (name "Net-(U14A-4A)") (class "Default")
      (node (ref "U14") (pin "13") (pinfunction "4B_13") (pintype "input"))
      (node (ref "U14") (pin "14") (pinfunction "4A_14") (pintype "input"))
      (node (ref "U19") (pin "30") (pinfunction "A6_30") (pintype "bidirectional"))
    )
    (net (code "166") (name "Net-(U14A-G)") (class "Default")
      (node (ref "U14") (pin "15") (pinfunction "G_15") (pintype "input"))
      (node (ref "U16") (pin "12") (pinfunction "E3_12") (pintype "input"))
      (node (ref "U16") (pin "13") (pinfunction "E0_13") (pintype "input"))
      (node (ref "U16") (pin "5") (pinfunction "E1_5") (pintype "input"))
      (node (ref "U16") (pin "6") (pinfunction "E2_6") (pintype "input"))
      (node (ref "U19") (pin "16") (pinfunction "AEC_16") (pintype "output"))
      (node (ref "U26") (pin "1") (pinfunction "OC_1") (pintype "input"))
      (node (ref "U27") (pin "10") (pinfunction "I1_10") (pintype "input"))
      (node (ref "U27") (pin "4") (pinfunction "I0_4") (pintype "input"))
      (node (ref "U8") (pin "11") (pinfunction "I_11") (pintype "input"))
    )
    (net (code "167") (name "Net-(U15A-G)") (class "Default")
      (node (ref "U15") (pin "1") (pinfunction "G_1") (pintype "input"))
      (node (ref "U17") (pin "12") (pinfunction "I/O_12") (pintype "tri_state"))
    )
    (net (code "168") (name "Net-(U15A-Y0)") (class "Default")
      (node (ref "U15") (pin "4") (pinfunction "Y0_4") (pintype "output"))
      (node (ref "U19") (pin "10") (pinfunction "~{CS}_10") (pintype "input"))
    )
    (net (code "169") (name "Net-(U15A-Y1)") (class "Default")
      (node (ref "U15") (pin "5") (pinfunction "Y1_5") (pintype "output"))
      (node (ref "U18") (pin "8") (pinfunction "CS_8") (pintype "input"))
    )
    (net (code "170") (name "Net-(U15A-Y2)") (class "Default")
      (node (ref "U15") (pin "6") (pinfunction "Y2_6") (pintype "output"))
      (node (ref "U27") (pin "9") (pinfunction "I0_9") (pintype "input"))
    )
    (net (code "171") (name "Net-(U15A-Y3)") (class "Default")
      (node (ref "U15") (pin "15") (pinfunction "G_15") (pintype "input"))
      (node (ref "U15") (pin "7") (pinfunction "Y3_7") (pintype "output"))
    )
    (net (code "172") (name "Net-(U15B-Y0)") (class "Default")
      (node (ref "U1") (pin "23") (pinfunction "~{CS}_23") (pintype "input"))
      (node (ref "U15") (pin "12") (pinfunction "Y0_12") (pintype "output"))
    )
    (net (code "173") (name "Net-(U15B-Y1)") (class "Default")
      (node (ref "U15") (pin "11") (pinfunction "Y1_11") (pintype "output"))
      (node (ref "U2") (pin "23") (pinfunction "~{CS}_23") (pintype "input"))
    )
    (net (code "174") (name "Net-(U16A-Z0)") (class "Default")
      (node (ref "U16") (pin "2") (pinfunction "Z0_2") (pintype "passive"))
      (node (ref "U19") (pin "35") (pinfunction "D11_35") (pintype "tri_state"))
      (node (ref "U6") (pin "11") (pinfunction "D3_11") (pintype "bidirectional"))
    )
    (net (code "175") (name "Net-(U16A-Z1)") (class "Default")
      (node (ref "U16") (pin "3") (pinfunction "Z1_3") (pintype "passive"))
      (node (ref "U19") (pin "36") (pinfunction "D10_36") (pintype "tri_state"))
      (node (ref "U6") (pin "12") (pinfunction "D2_12") (pintype "bidirectional"))
    )
    (net (code "176") (name "Net-(U16A-Z2)") (class "Default")
      (node (ref "U16") (pin "9") (pinfunction "Z2_9") (pintype "passive"))
      (node (ref "U19") (pin "37") (pinfunction "D9_37") (pintype "tri_state"))
      (node (ref "U6") (pin "13") (pinfunction "D1_13") (pintype "bidirectional"))
    )
    (net (code "177") (name "Net-(U16A-Z3)") (class "Default")
      (node (ref "U16") (pin "10") (pinfunction "Z3_10") (pintype "passive"))
      (node (ref "U19") (pin "38") (pinfunction "D8_38") (pintype "tri_state"))
      (node (ref "U6") (pin "14") (pinfunction "D0_14") (pintype "bidirectional"))
    )
    (net (code "178") (name "Net-(U17A-BASIC)") (class "Default")
      (node (ref "U17") (pin "17") (pinfunction "BASIC_17") (pintype "tri_state"))
      (node (ref "U3") (pin "20") (pinfunction "CS_20") (pintype "input"))
    )
    (net (code "179") (name "Net-(U17A-CASRAM)") (class "Default")
      (node (ref "R42") (pin "2") (pinfunction "2_2") (pintype "passive"))
      (node (ref "U17") (pin "18") (pinfunction "CASRAM_18") (pintype "tri_state"))
    )
    (net (code "180") (name "Net-(U17A-CHAREN)") (class "Default")
      (node (ref "R43") (pin "2") (pinfunction "2_2") (pintype "passive"))
      (node (ref "U17") (pin "6") (pinfunction "CHAREN_6") (pintype "input"))
      (node (ref "U7") (pin "27") (pinfunction "P2_27") (pintype "bidirectional"))
    )
    (net (code "181") (name "Net-(U17A-CHAROM)") (class "Default")
      (node (ref "U17") (pin "15") (pinfunction "CHAROM_15") (pintype "tri_state"))
      (node (ref "U5") (pin "20") (pinfunction "CS1_20") (pintype "input"))
    )
    (net (code "182") (name "Net-(U17A-GR{slash}W)") (class "Default")
      (node (ref "U17") (pin "13") (pinfunction "GR/W_13") (pintype "tri_state"))
      (node (ref "U6") (pin "10") (pinfunction "~{WE}_10") (pintype "input"))
    )
    (net (code "183") (name "Net-(U17A-HIRAM)") (class "Default")
      (node (ref "R44") (pin "2") (pinfunction "2_2") (pintype "passive"))
      (node (ref "U17") (pin "7") (pinfunction "HIRAM_7") (pintype "input"))
      (node (ref "U7") (pin "28") (pinfunction "P1_28") (pintype "bidirectional"))
    )
    (net (code "184") (name "Net-(U17A-KERNAL)") (class "Default")
      (node (ref "U17") (pin "16") (pinfunction "KERNAL_16") (pintype "tri_state"))
      (node (ref "U4") (pin "20") (pinfunction "CS_20") (pintype "input"))
    )
    (net (code "185") (name "Net-(U17A-LORAM)") (class "Default")
      (node (ref "R45") (pin "2") (pinfunction "2_2") (pintype "passive"))
      (node (ref "U17") (pin "8") (pinfunction "LORAM_8") (pintype "input"))
      (node (ref "U7") (pin "29") (pinfunction "P0_29") (pintype "bidirectional"))
    )
    (net (code "186") (name "Net-(U18A-AUDIO-OUT)") (class "Default")
      (node (ref "FB13") (pin "1") (pinfunction "1_1") (pintype "passive"))
      (node (ref "R6") (pin "1") (pinfunction "1_1") (pintype "passive"))
      (node (ref "U18") (pin "27") (pinfunction "AUDIO-OUT_27") (pintype "output"))
    )
    (net (code "187") (name "Net-(U18A-CAP1A)") (class "Default")
      (node (ref "C10") (pin "1") (pinfunction "1_1") (pintype "passive"))
      (node (ref "U18") (pin "1") (pinfunction "CAP1A_1") (pintype "input"))
    )
    (net (code "188") (name "Net-(U18A-CAP1B)") (class "Default")
      (node (ref "C10") (pin "2") (pinfunction "2_2") (pintype "passive"))
      (node (ref "U18") (pin "2") (pinfunction "CAP1B_2") (pintype "input"))
    )
    (net (code "189") (name "Net-(U18A-CAP2A)") (class "Default")
      (node (ref "C11") (pin "1") (pinfunction "1_1") (pintype "passive"))
      (node (ref "U18") (pin "3") (pinfunction "CAP2A_3") (pintype "input"))
    )
    (net (code "190") (name "Net-(U18A-CAP2B)") (class "Default")
      (node (ref "C11") (pin "2") (pinfunction "2_2") (pintype "passive"))
      (node (ref "U18") (pin "4") (pinfunction "CAP2B_4") (pintype "input"))
    )
    (net (code "191") (name "Net-(U18A-POTX)") (class "Default")
      (node (ref "C93") (pin "1") (pinfunction "1_1") (pintype "passive"))
      (node (ref "U18") (pin "24") (pinfunction "POTX_24") (pintype "input"))
      (node (ref "U28") (pin "2") (pinfunction "Z0_2") (pintype "passive"))
      (node (ref "U28") (pin "9") (pinfunction "Z2_9") (pintype "passive"))
    )
    (net (code "192") (name "Net-(U18A-POTY)") (class "Default")
      (node (ref "C48") (pin "1") (pinfunction "1_1") (pintype "passive"))
      (node (ref "U18") (pin "23") (pinfunction "POTY_23") (pintype "input"))
      (node (ref "U28") (pin "10") (pinfunction "Z3_10") (pintype "passive"))
      (node (ref "U28") (pin "3") (pinfunction "Z1_3") (pintype "passive"))
    )
    (net (code "193") (name "Net-(U18A-RESET)") (class "Default")
      (node (ref "FB4") (pin "1") (pinfunction "1_1") (pintype "passive"))
      (node (ref "U18") (pin "5") (pinfunction "RESET_5") (pintype "input"))
    )
    (net (code "194") (name "Net-(U18B-V12)") (class "Default")
      (node (ref "C51") (pin "1") (pinfunction "1_1") (pintype "passive"))
      (node (ref "FB11") (pin "1") (pinfunction "1_1") (pintype "passive"))
      (node (ref "U18") (pin "28") (pinfunction "V12_28") (pintype "power_in"))
    )
    (net (code "195") (name "Net-(U18B-VCC)") (class "Default")
      (node (ref "C50") (pin "1") (pinfunction "1_1") (pintype "passive"))
      (node (ref "FB10") (pin "1") (pinfunction "1_1") (pintype "passive"))
      (node (ref "U18") (pin "25") (pinfunction "VCC_25") (pintype "power_in"))
    )
    (net (code "196") (name "Net-(U19A-COLCLK)") (class "Default")
      (node (ref "FB16") (pin "1") (pinfunction "1_1") (pintype "passive"))
      (node (ref "U19") (pin "21") (pinfunction "COLCLK_21") (pintype "input"))
      (node (ref "U30") (pin "5") (pinfunction "CNT-UP_5") (pintype "input"))
    )
    (net (code "197") (name "Net-(U19A-COLOR)") (class "Default")
      (node (ref "FB14") (pin "2") (pinfunction "2_2") (pintype "passive"))
      (node (ref "U19") (pin "14") (pinfunction "COLOR_14") (pintype "output"))
    )
    (net (code "198") (name "Net-(U19A-LP)") (class "Default")
      (node (ref "CN1") (pin "8") (pinfunction "8_8") (pintype "passive"))
      (node (ref "CN9") (pin "6") (pinfunction "6_6") (pintype "passive"))
      (node (ref "U1") (pin "14") (pinfunction "PB4_14") (pintype "bidirectional"))
      (node (ref "U19") (pin "9") (pinfunction "LP_9") (pintype "input"))
    )
    (net (code "199") (name "Net-(U19A-PHI0)") (class "Default")
      (node (ref "FB23") (pin "2") (pinfunction "2_2") (pintype "passive"))
      (node (ref "U19") (pin "17") (pinfunction "PHI0_17") (pintype "output"))
    )
    (net (code "200") (name "Net-(U19A-SYNC)") (class "Default")
      (node (ref "FB15") (pin "2") (pinfunction "2_2") (pintype "passive"))
      (node (ref "U19") (pin "15") (pinfunction "SYNC_15") (pintype "output"))
    )
    (net (code "201") (name "Net-(U19B-V12)") (class "Default")
      (node (ref "C53") (pin "1") (pinfunction "1_1") (pintype "passive"))
      (node (ref "FB12") (pin "1") (pinfunction "1_1") (pintype "passive"))
      (node (ref "U19") (pin "13") (pinfunction "V12_13") (pintype "power_in"))
    )
    (net (code "202") (name "Net-(U19B-VCC)") (class "Default")
      (node (ref "C101") (pin "1") (pinfunction "1_1") (pintype "passive"))
      (node (ref "C60") (pin "1") (pinfunction "1_1") (pintype "passive"))
      (node (ref "FB22") (pin "1") (pinfunction "1_1") (pintype "passive"))
      (node (ref "U19") (pin "40") (pinfunction "VCC_40") (pintype "power_in"))
    )
    (net (code "203") (name "Net-(U20A-DIS)") (class "Default")
      (node (ref "C23") (pin "1") (pinfunction "1_1") (pintype "passive"))
      (node (ref "R33") (pin "2") (pinfunction "2_2") (pintype "passive"))
      (node (ref "U20") (pin "1") (pinfunction "DIS_1") (pintype "input"))
      (node (ref "U20") (pin "2") (pinfunction "THR_2") (pintype "input"))
    )
    (net (code "204") (name "Net-(U20A-Q)") (class "Default")
      (node (ref "U20") (pin "5") (pinfunction "Q_5") (pintype "output"))
      (node (ref "U8") (pin "5") (pinfunction "I_5") (pintype "input"))
    )
    (net (code "205") (name "Net-(U20A-TR)") (class "Default")
      (node (ref "C38") (pin "2") (pinfunction "2_2") (pintype "passive"))
      (node (ref "R35") (pin "1") (pinfunction "1_1") (pintype "passive"))
      (node (ref "U20") (pin "6") (pinfunction "TR_6") (pintype "input"))
    )
    (net (code "206") (name "Net-(U20B-Q)") (class "Default")
      (node (ref "U20") (pin "9") (pinfunction "Q_9") (pintype "output"))
      (node (ref "U8") (pin "13") (pinfunction "I_13") (pintype "input"))
    )
    (net (code "207") (name "Net-(U20B-TR)") (class "Default")
      (node (ref "C105") (pin "1") (pinfunction "1_1") (pintype "passive"))
      (node (ref "R50") (pin "2") (pinfunction "2_2") (pintype "passive"))
      (node (ref "U20") (pin "8") (pinfunction "TR_8") (pintype "input"))
    )
    (net (code "208") (name "Net-(U27A-O)") (class "Default")
      (node (ref "U27") (pin "3") (pinfunction "O_3") (pintype "output"))
      (node (ref "U7") (pin "2") (pinfunction "RDY_2") (pintype "input"))
    )
    (net (code "209") (name "Net-(U27B-O)") (class "Default")
      (node (ref "U27") (pin "6") (pinfunction "O_6") (pintype "output"))
      (node (ref "U7") (pin "5") (pinfunction "AEC_5") (pintype "input"))
    )
    (net (code "210") (name "Net-(U27C-O)") (class "Default")
      (node (ref "U27") (pin "8") (pinfunction "O_8") (pintype "output"))
      (node (ref "U6") (pin "8") (pinfunction "~{CS}_8") (pintype "input"))
    )
    (net (code "211") (name "Net-(U28A-Y0)") (class "Default")
      (node (ref "CN8") (pin "9") (pinfunction "9_9") (pintype "passive"))
      (node (ref "U28") (pin "1") (pinfunction "Y0_1") (pintype "passive"))
    )
    (net (code "212") (name "Net-(U28A-Y1)") (class "Default")
      (node (ref "CN8") (pin "5") (pinfunction "5_5") (pintype "passive"))
      (node (ref "U28") (pin "4") (pinfunction "Y1_4") (pintype "passive"))
    )
    (net (code "213") (name "Net-(U28A-Y2)") (class "Default")
      (node (ref "CN9") (pin "9") (pinfunction "9_9") (pintype "passive"))
      (node (ref "U28") (pin "8") (pinfunction "Y2_8") (pintype "passive"))
    )
    (net (code "214") (name "Net-(U28A-Y3)") (class "Default")
      (node (ref "CN9") (pin "5") (pinfunction "5_5") (pintype "passive"))
      (node (ref "U28") (pin "11") (pinfunction "Y3_11") (pintype "passive"))
    )
    (net (code "215") (name "Net-(U29A-PRE)") (class "Default")
      (node (ref "JP1") (pin "1") (pinfunction "1_1") (pintype "passive"))
      (node (ref "JP1") (pin "3") (pinfunction "3_3") (pintype "passive"))
      (node (ref "U29") (pin "4") (pinfunction "PRE_4") (pintype "input"))
      (node (ref "U30") (pin "1") (pinfunction "C_1") (pintype "input"))
      (node (ref "U30") (pin "10") (pinfunction "B_10") (pintype "input"))
    )
    (net (code "216") (name "Net-(U29A-Q)") (class "Default")
      (node (ref "U29") (pin "5") (pinfunction "Q_5") (pintype "output"))
      (node (ref "U30") (pin "9") (pinfunction "D_9") (pintype "input"))
    )
    (net (code "217") (name "Net-(U29B-CLK)") (class "Default")
      (node (ref "U29") (pin "11") (pinfunction "CLK_11") (pintype "input"))
      (node (ref "U30") (pin "6") (pinfunction "QC_6") (pintype "output"))
    )
    (net (code "218") (name "Net-(U29B-D)") (class "Default")
      (node (ref "U29") (pin "12") (pinfunction "D_12") (pintype "input"))
      (node (ref "U29") (pin "8") (pinfunction "~{Q}_8") (pintype "output"))
    )
    (net (code "219") (name "Net-(U29B-Q)") (class "Default")
      (node (ref "U29") (pin "9") (pinfunction "Q_9") (pintype "output"))
      (node (ref "U32") (pin "1") (pinfunction "PDI1_1") (pintype "input"))
    )
    (net (code "220") (name "Net-(U30A-CRY)") (class "Default")
      (node (ref "C83") (pin "2") (pinfunction "2_2") (pintype "passive"))
      (node (ref "U30") (pin "11") (pinfunction "LOAD_11") (pintype "input"))
      (node (ref "U30") (pin "12") (pinfunction "CRY_12") (pintype "output"))
    )
    (net (code "221") (name "Net-(U31A-C1)") (class "Default")
      (node (ref "C86") (pin "1") (pinfunction "1_1") (pintype "passive"))
      (node (ref "U31") (pin "4") (pinfunction "C1_4") (pintype "passive"))
    )
    (net (code "222") (name "Net-(U31A-C2)") (class "Default")
      (node (ref "C86") (pin "2") (pinfunction "2_2") (pintype "passive"))
      (node (ref "U31") (pin "5") (pinfunction "C2_5") (pintype "passive"))
    )
    (net (code "223") (name "Net-(U31A-FREQ)") (class "Default")
      (node (ref "R16") (pin "2") (pinfunction "2_2") (pintype "passive"))
      (node (ref "R17") (pin "1") (pinfunction "1_1") (pintype "passive"))
      (node (ref "U31") (pin "2") (pinfunction "FREQ_2") (pintype "passive"))
      (node (ref "U32") (pin "8") (pinfunction "BO_8") (pintype "output"))
    )
    (net (code "224") (name "Net-(U31A-I1)") (class "Default")
      (node (ref "R26") (pin "2") (pinfunction "2_2") (pintype "passive"))
      (node (ref "U31") (pin "15") (pinfunction "I1_15") (pintype "input"))
    )
    (net (code "225") (name "Net-(U31A-I3)") (class "Default")
      (node (ref "C87") (pin "1") (pinfunction "1_1") (pintype "passive"))
      (node (ref "R22") (pin "1") (pinfunction "1_1") (pintype "passive"))
      (node (ref "R23") (pin "2") (pinfunction "2_2") (pintype "passive"))
      (node (ref "U31") (pin "3") (pinfunction "I3_3") (pintype "input"))
    )
    (net (code "226") (name "Net-(U31A-RNG)") (class "Default")
      (node (ref "C76") (pin "1") (pinfunction "1_1") (pintype "passive"))
      (node (ref "R15") (pin "1") (pinfunction "1_1") (pintype "passive"))
      (node (ref "U31") (pin "14") (pinfunction "RNG_14") (pintype "input"))
    )
    (net (code "227") (name "Net-(U31A-VCO)") (class "Default")
      (node (ref "C58") (pin "1") (pinfunction "1_1") (pintype "passive"))
      (node (ref "R27") (pin "S") (pinfunction "S_S") (pintype "passive"))
      (node (ref "U31") (pin "1") (pinfunction "VCO_1") (pintype "passive"))
    )
    (net (code "228") (name "Net-(U31A-X1)") (class "Default")
      (node (ref "C70") (pin "2") (pinfunction "2_2") (pintype "passive"))
      (node (ref "U31") (pin "12") (pinfunction "X1_12") (pintype "passive"))
    )
    (net (code "229") (name "Net-(U31A-X2)") (class "Default")
      (node (ref "U31") (pin "13") (pinfunction "X2_13") (pintype "passive"))
      (node (ref "Y1") (pin "2") (pinfunction "2_2") (pintype "passive"))
    )
    (net (code "230") (name "Net-(U31A-Y1)") (class "Default")
      (node (ref "FB16") (pin "2") (pinfunction "2_2") (pintype "passive"))
      (node (ref "U31") (pin "10") (pinfunction "Y1_10") (pintype "output"))
    )
    (net (code "231") (name "Net-(U31A-Y2)") (class "Default")
      (node (ref "FB17") (pin "2") (pinfunction "2_2") (pintype "passive"))
      (node (ref "U31") (pin "7") (pinfunction "Y2_7") (pintype "output"))
    )
    (net (code "232") (name "Net-(U32A-CPI1)") (class "Default")
      (node (ref "U32") (pin "13") (pinfunction "PDO1_13") (pintype "output"))
      (node (ref "U32") (pin "4") (pinfunction "CPI1_4") (pintype "input"))
    )
    (net (code "233") (name "Net-(U32A-CPI2)") (class "Default")
      (node (ref "U32") (pin "11") (pinfunction "CPI2_11") (pintype "input"))
      (node (ref "U32") (pin "2") (pinfunction "PDO2_2") (pintype "output"))
    )
    (net (code "234") (name "Net-(U32A-CPI3)") (class "Default")
      (node (ref "R19") (pin "2") (pinfunction "2_2") (pintype "passive"))
      (node (ref "U32") (pin "10") (pinfunction "CPO_10") (pintype "output"))
      (node (ref "U32") (pin "5") (pinfunction "CPI3_5") (pintype "input"))
    )
    (net (code "235") (name "Net-(U32A-PDI2)") (class "Default")
      (node (ref "C106") (pin "1") (pinfunction "1_1") (pintype "passive"))
      (node (ref "FB23") (pin "1") (pinfunction "1_1") (pintype "passive"))
      (node (ref "U32") (pin "3") (pinfunction "PDI2_3") (pintype "input"))
      (node (ref "U7") (pin "1") (pinfunction "CLKIN_1") (pintype "input"))
    )
    (net (code "236") (name "VCC") (class "Default")
      (node (ref "C14") (pin "+") (pinfunction "1_+") (pintype "passive"))
      (node (ref "C15") (pin "+") (pinfunction "1_+") (pintype "passive"))
      (node (ref "C17") (pin "+") (pinfunction "1_+") (pintype "passive"))
      (node (ref "C2") (pin "1") (pinfunction "1_1") (pintype "passive"))
      (node (ref "C22") (pin "1") (pinfunction "1_1") (pintype "passive"))
      (node (ref "C25") (pin "1") (pinfunction "1_1") (pintype "passive"))
      (node (ref "C26") (pin "1") (pinfunction "1_1") (pintype "passive"))
      (node (ref "C27") (pin "1") (pinfunction "1_1") (pintype "passive"))
      (node (ref "C28") (pin "1") (pinfunction "1_1") (pintype "passive"))
      (node (ref "C29") (pin "1") (pinfunction "1_1") (pintype "passive"))
      (node (ref "C3") (pin "1") (pinfunction "1_1") (pintype "passive"))
      (node (ref "C30") (pin "1") (pinfunction "1_1") (pintype "passive"))
      (node (ref "C31") (pin "1") (pinfunction "1_1") (pintype "passive"))
      (node (ref "C32") (pin "1") (pinfunction "1_1") (pintype "passive"))
      (node (ref "C33") (pin "1") (pinfunction "1_1") (pintype "passive"))
      (node (ref "C34") (pin "+") (pinfunction "1_+") (pintype "passive"))
      (node (ref "C39") (pin "1") (pinfunction "1_1") (pintype "passive"))
      (node (ref "C4") (pin "1") (pinfunction "1_1") (pintype "passive"))
      (node (ref "C40") (pin "1") (pinfunction "1_1") (pintype "passive"))
      (node (ref "C41") (pin "1") (pinfunction "1_1") (pintype "passive"))
      (node (ref "C42") (pin "1") (pinfunction "1_1") (pintype "passive"))
      (node (ref "C43") (pin "1") (pinfunction "1_1") (pintype "passive"))
      (node (ref "C44") (pin "1") (pinfunction "1_1") (pintype "passive"))
      (node (ref "C45") (pin "1") (pinfunction "1_1") (pintype "passive"))
      (node (ref "C46") (pin "1") (pinfunction "1_1") (pintype "passive"))
      (node (ref "C47") (pin "1") (pinfunction "1_1") (pintype "passive"))
      (node (ref "C49") (pin "1") (pinfunction "1_1") (pintype "passive"))
      (node (ref "C5") (pin "1") (pinfunction "1_1") (pintype "passive"))
      (node (ref "C56") (pin "1") (pinfunction "1_1") (pintype "passive"))
      (node (ref "C6") (pin "1") (pinfunction "1_1") (pintype "passive"))
      (node (ref "C68") (pin "1") (pinfunction "1_1") (pintype "passive"))
      (node (ref "C7") (pin "1") (pinfunction "1_1") (pintype "passive"))
      (node (ref "C74") (pin "1") (pinfunction "1_1") (pintype "passive"))
      (node (ref "C8") (pin "+") (pinfunction "1_+") (pintype "passive"))
      (node (ref "C82") (pin "1") (pinfunction "1_1") (pintype "passive"))
      (node (ref "C9") (pin "1") (pinfunction "1_1") (pintype "passive"))
      (node (ref "C91") (pin "+") (pinfunction "1_+") (pintype "passive"))
      (node (ref "C92") (pin "1") (pinfunction "1_1") (pintype "passive"))
      (node (ref "C96") (pin "1") (pinfunction "1_1") (pintype "passive"))
      (node (ref "CN1") (pin "4") (pinfunction "4_4") (pintype "passive"))
      (node (ref "CN2") (pin "11") (pinfunction "VCC_11") (pintype "passive"))
      (node (ref "CN6") (pin "2") (pinfunction "+5V1_2") (pintype "passive"))
      (node (ref "CN6") (pin "3") (pinfunction "+5V2_3") (pintype "passive"))
      (node (ref "FB10") (pin "2") (pinfunction "2_2") (pintype "passive"))
      (node (ref "FB18") (pin "1") (pinfunction "1_1") (pintype "passive"))
      (node (ref "FB3") (pin "1") (pinfunction "1_1") (pintype "passive"))
      (node (ref "FB6") (pin "2") (pinfunction "2_2") (pintype "passive"))
      (node (ref "R1") (pin "1") (pinfunction "1_1") (pintype "passive"))
      (node (ref "R28") (pin "1") (pinfunction "1_1") (pintype "passive"))
      (node (ref "R29") (pin "1") (pinfunction "1_1") (pintype "passive"))
      (node (ref "R30") (pin "1") (pinfunction "1_1") (pintype "passive"))
      (node (ref "R31") (pin "1") (pinfunction "1_1") (pintype "passive"))
      (node (ref "R33") (pin "1") (pinfunction "1_1") (pintype "passive"))
      (node (ref "R34") (pin "1") (pinfunction "1_1") (pintype "passive"))
      (node (ref "R36") (pin "1") (pinfunction "1_1") (pintype "passive"))
      (node (ref "R39") (pin "1") (pinfunction "1_1") (pintype "passive"))
      (node (ref "R41") (pin "1") (pinfunction "1_1") (pintype "passive"))
      (node (ref "R43") (pin "1") (pinfunction "1_1") (pintype "passive"))
      (node (ref "R44") (pin "1") (pinfunction "1_1") (pintype "passive"))
      (node (ref "R45") (pin "1") (pinfunction "1_1") (pintype "passive"))
      (node (ref "R46") (pin "2") (pinfunction "2_2") (pintype "passive"))
      (node (ref "R50") (pin "1") (pinfunction "1_1") (pintype "passive"))
      (node (ref "RP3") (pin "1") (pinfunction "1_1") (pintype "passive"))
      (node (ref "RP4") (pin "1") (pinfunction "1_1") (pintype "passive"))
      (node (ref "SW1") (pin "4") (pinfunction "S_4") (pintype "passive"))
      (node (ref "U1") (pin "1") (pinfunction "VCC_1") (pintype "power_in"))
      (node (ref "U10") (pin "8") (pinfunction "VCC_8") (pintype "power_in"))
      (node (ref "U11") (pin "8") (pinfunction "VCC_8") (pintype "power_in"))
      (node (ref "U12") (pin "8") (pinfunction "VCC_8") (pintype "power_in"))
      (node (ref "U13") (pin "16") (pinfunction "VCC_16") (pintype "power_in"))
      (node (ref "U14") (pin "16") (pinfunction "VCC_16") (pintype "power_in"))
      (node (ref "U15") (pin "16") (pinfunction "VCC_16") (pintype "power_in"))
      (node (ref "U16") (pin "14") (pinfunction "VCC_14") (pintype "power_in"))
      (node (ref "U17") (pin "28") (pinfunction "VCC_28") (pintype "power_in"))
      (node (ref "U2") (pin "1") (pinfunction "VCC_1") (pintype "power_in"))
      (node (ref "U20") (pin "10") (pinfunction "R_10") (pintype "input"))
      (node (ref "U20") (pin "14") (pinfunction "VCC_14") (pintype "power_in"))
      (node (ref "U20") (pin "4") (pinfunction "R_4") (pintype "input"))
      (node (ref "U21") (pin "8") (pinfunction "VCC_8") (pintype "power_in"))
      (node (ref "U22") (pin "8") (pinfunction "VCC_8") (pintype "power_in"))
      (node (ref "U23") (pin "8") (pinfunction "VCC_8") (pintype "power_in"))
      (node (ref "U24") (pin "8") (pinfunction "VCC_8") (pintype "power_in"))
      (node (ref "U25") (pin "16") (pinfunction "VCC_16") (pintype "power_in"))
      (node (ref "U26") (pin "20") (pinfunction "VCC_20") (pintype "power_in"))
      (node (ref "U27") (pin "13") (pinfunction "I1_13") (pintype "input"))
      (node (ref "U27") (pin "14") (pinfunction "VCC_14") (pintype "power_in"))
      (node (ref "U28") (pin "14") (pinfunction "VCC_14") (pintype "power_in"))
      (node (ref "U29") (pin "14") (pinfunction "VCC_14") (pintype "power_in"))
      (node (ref "U3") (pin "24") (pinfunction "VCC_24") (pintype "power_in"))
      (node (ref "U30") (pin "16") (pinfunction "VCC_16") (pintype "power_in"))
      (node (ref "U31") (pin "16") (pinfunction "VCC_16") (pintype "power_in"))
      (node (ref "U32") (pin "14") (pinfunction "VCC_14") (pintype "power_in"))
      (node (ref "U4") (pin "24") (pinfunction "VCC_24") (pintype "power_in"))
      (node (ref "U5") (pin "21") (pinfunction "CS2_21") (pintype "input"))
      (node (ref "U5") (pin "24") (pinfunction "VCC_24") (pintype "power_in"))
      (node (ref "U6") (pin "18") (pinfunction "VCC_18") (pintype "power_in"))
      (node (ref "U7") (pin "6") (pinfunction "VCC_6") (pintype "power_in"))
      (node (ref "U8") (pin "14") (pinfunction "VCC_14") (pintype "power_in"))
      (node (ref "U9") (pin "8") (pinfunction "VCC_8") (pintype "power_in"))
    )
    (net (code "237") (name "unconnected-(CN1-Pad2)") (class "Default")
      (node (ref "CN1") (pin "2") (pinfunction "2_2") (pintype "passive"))
    )
    (net (code "238") (name "unconnected-(CN7-Pad4)") (class "Default")
      (node (ref "CN7") (pin "4") (pinfunction "4_4") (pintype "passive"))
    )
    (net (code "239") (name "unconnected-(F1-Pad1B)") (class "Default")
      (node (ref "F1") (pin "1B") (pinfunction "1B_1B") (pintype "passive"))
    )
    (net (code "240") (name "unconnected-(F1-Pad2B)") (class "Default")
      (node (ref "F1") (pin "2B") (pinfunction "2B_2B") (pintype "passive"))
    )
    (net (code "241") (name "unconnected-(R18-Pad2)") (class "Default")
      (node (ref "R18") (pin "2") (pinfunction "2_2") (pintype "passive"))
    )
    (net (code "242") (name "unconnected-(SW1A-O-Pad3)") (class "Default")
      (node (ref "SW1") (pin "3") (pinfunction "O_3") (pintype "passive"))
    )
    (net (code "243") (name "unconnected-(SW1B-O-Pad6)") (class "Default")
      (node (ref "SW1") (pin "6") (pinfunction "O_6") (pintype "passive"))
    )
    (net (code "244") (name "unconnected-(U1A-~{PC}-Pad18)") (class "Default")
      (node (ref "U1") (pin "18") (pinfunction "~{PC}_18") (pintype "bidirectional"))
    )
    (net (code "245") (name "unconnected-(U9A-NC-Pad1)") (class "Default")
      (node (ref "U9") (pin "1") (pinfunction "NC_1") (pintype "passive"))
    )
    (net (code "246") (name "unconnected-(U10A-NC-Pad1)") (class "Default")
      (node (ref "U10") (pin "1") (pinfunction "NC_1") (pintype "passive"))
    )
    (net (code "247") (name "unconnected-(U11A-NC-Pad1)") (class "Default")
      (node (ref "U11") (pin "1") (pinfunction "NC_1") (pintype "passive"))
    )
    (net (code "248") (name "unconnected-(U12A-NC-Pad1)") (class "Default")
      (node (ref "U12") (pin "1") (pinfunction "NC_1") (pintype "passive"))
    )
    (net (code "249") (name "unconnected-(U17A-NC-Pad1)") (class "Default")
      (node (ref "U17") (pin "1") (pinfunction "NC_1") (pintype "no_connect"))
    )
    (net (code "250") (name "unconnected-(U20A-CV-Pad3)") (class "Default")
      (node (ref "U20") (pin "3") (pinfunction "CV_3") (pintype "passive"))
    )
    (net (code "251") (name "unconnected-(U20B-CV-Pad11)") (class "Default")
      (node (ref "U20") (pin "11") (pinfunction "CV_11") (pintype "passive"))
    )
    (net (code "252") (name "unconnected-(U21A-NC-Pad1)") (class "Default")
      (node (ref "U21") (pin "1") (pinfunction "NC_1") (pintype "passive"))
    )
    (net (code "253") (name "unconnected-(U22A-NC-Pad1)") (class "Default")
      (node (ref "U22") (pin "1") (pinfunction "NC_1") (pintype "passive"))
    )
    (net (code "254") (name "unconnected-(U23A-NC-Pad1)") (class "Default")
      (node (ref "U23") (pin "1") (pinfunction "NC_1") (pintype "passive"))
    )
    (net (code "255") (name "unconnected-(U24A-NC-Pad1)") (class "Default")
      (node (ref "U24") (pin "1") (pinfunction "NC_1") (pintype "passive"))
    )
    (net (code "256") (name "unconnected-(U29A-~{Q}-Pad6)") (class "Default")
      (node (ref "U29") (pin "6") (pinfunction "~{Q}_6") (pintype "output"))
    )
    (net (code "257") (name "unconnected-(U30A-QA-Pad3)") (class "Default")
      (node (ref "U30") (pin "3") (pinfunction "QA_3") (pintype "output"))
    )
    (net (code "258") (name "unconnected-(U30A-QB-Pad2)") (class "Default")
      (node (ref "U30") (pin "2") (pinfunction "QB_2") (pintype "output"))
    )
    (net (code "259") (name "unconnected-(U30A-QD-Pad7)") (class "Default")
      (node (ref "U30") (pin "7") (pinfunction "QD_7") (pintype "output"))
    )
    (net (code "260") (name "unconnected-(U30A-X-Pad13)") (class "Default")
      (node (ref "U30") (pin "13") (pinfunction "X_13") (pintype "output"))
    )
    (net (code "261") (name "unconnected-(U32A-NC1-Pad6)") (class "Default")
      (node (ref "U32") (pin "6") (pinfunction "NC1_6") (pintype "no_connect"))
    )
    (net (code "262") (name "unconnected-(U32A-NC2-Pad12)") (class "Default")
      (node (ref "U32") (pin "12") (pinfunction "NC2_12") (pintype "no_connect"))
    )
  )
)
